# DM01eco.net
KiCad netlist of a schematic drawn in EAGLE
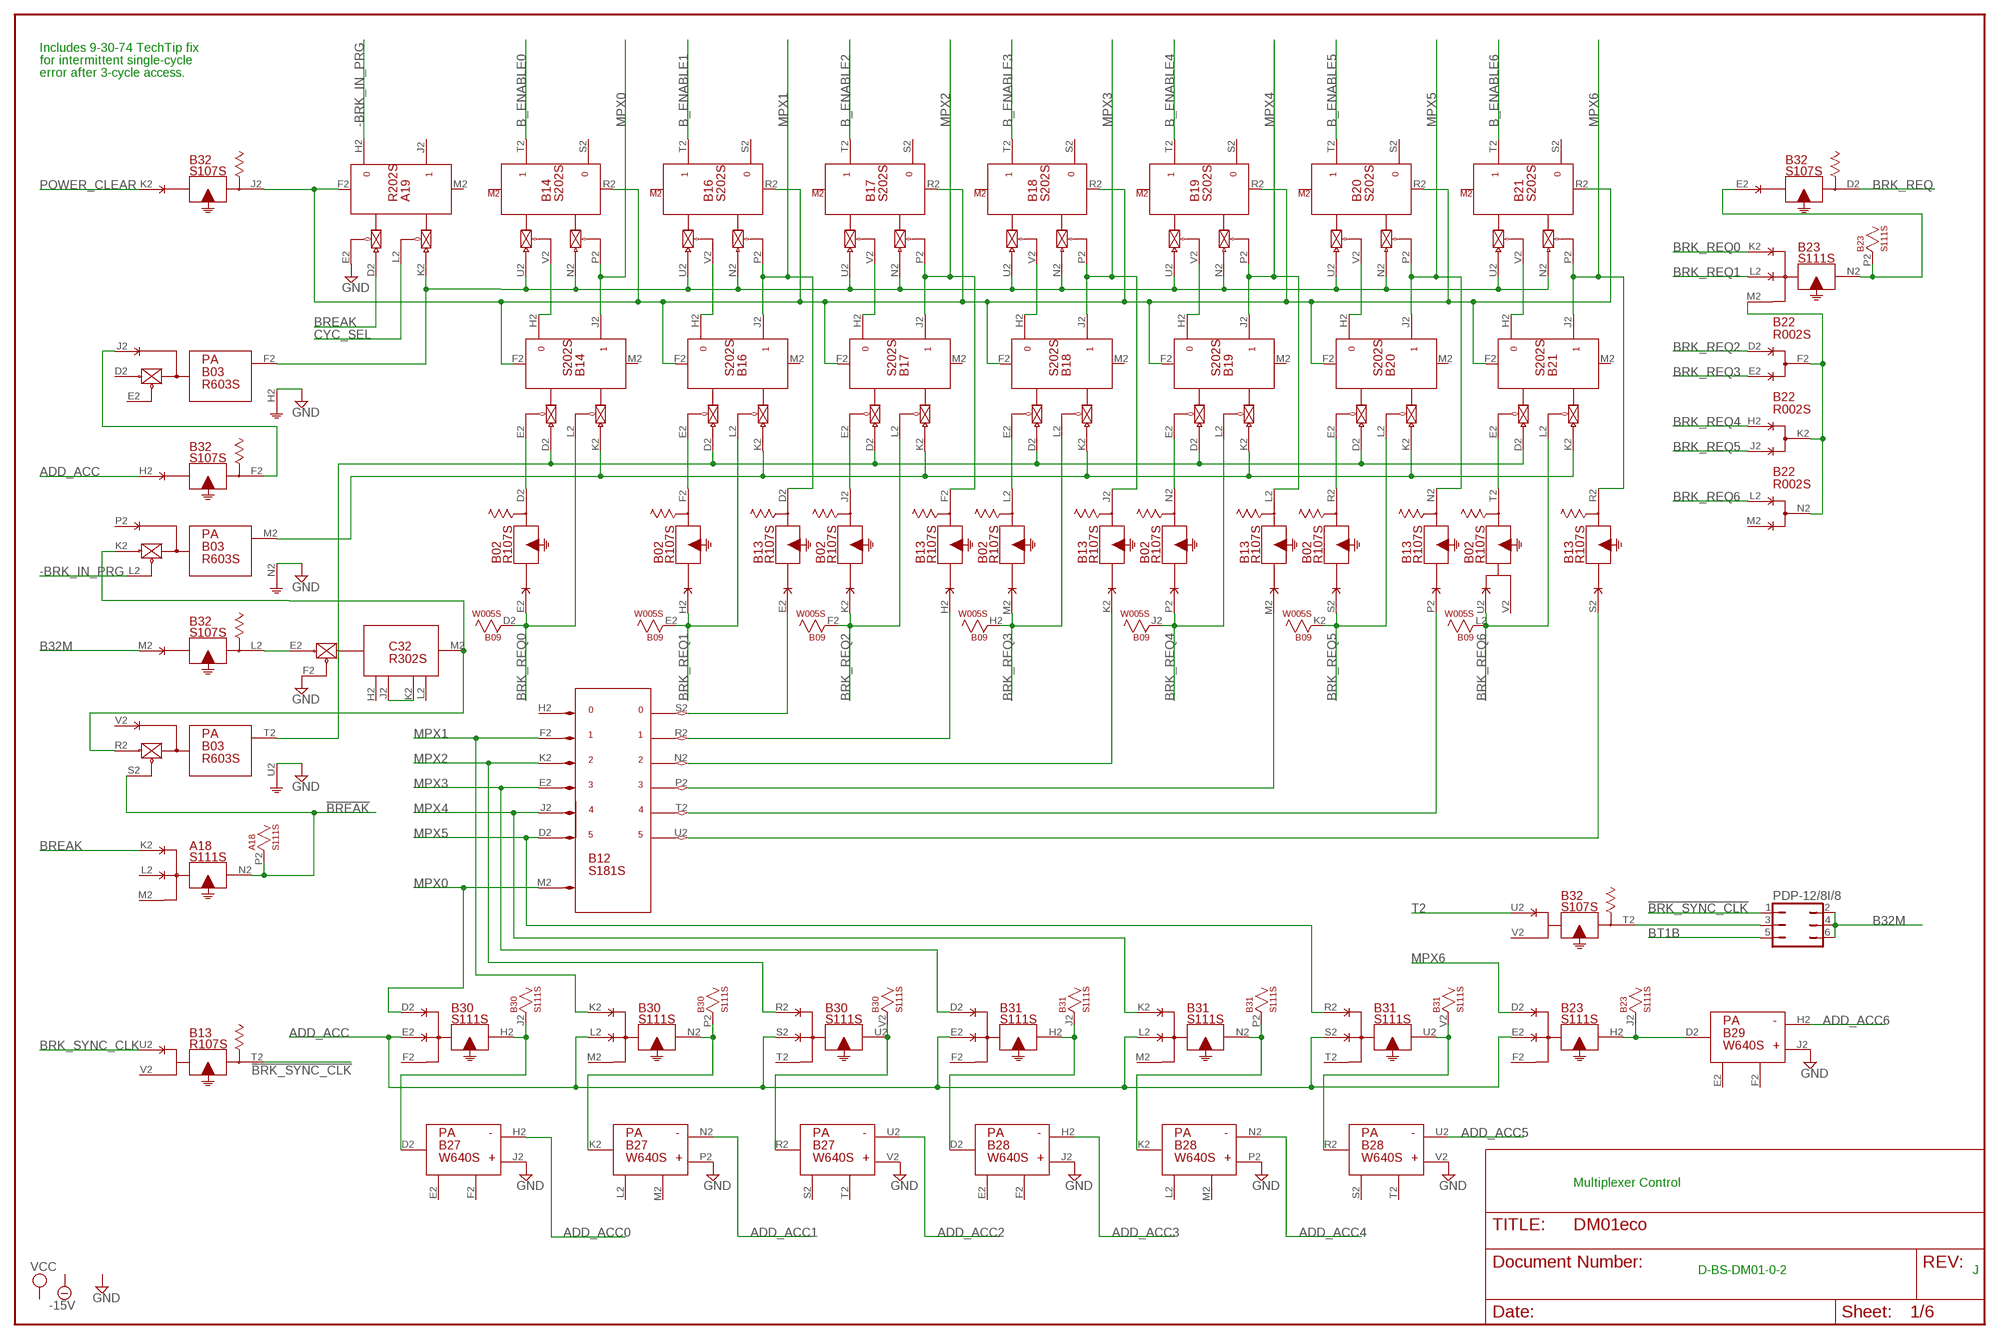
[diagram p0: schematic, sheet 1]
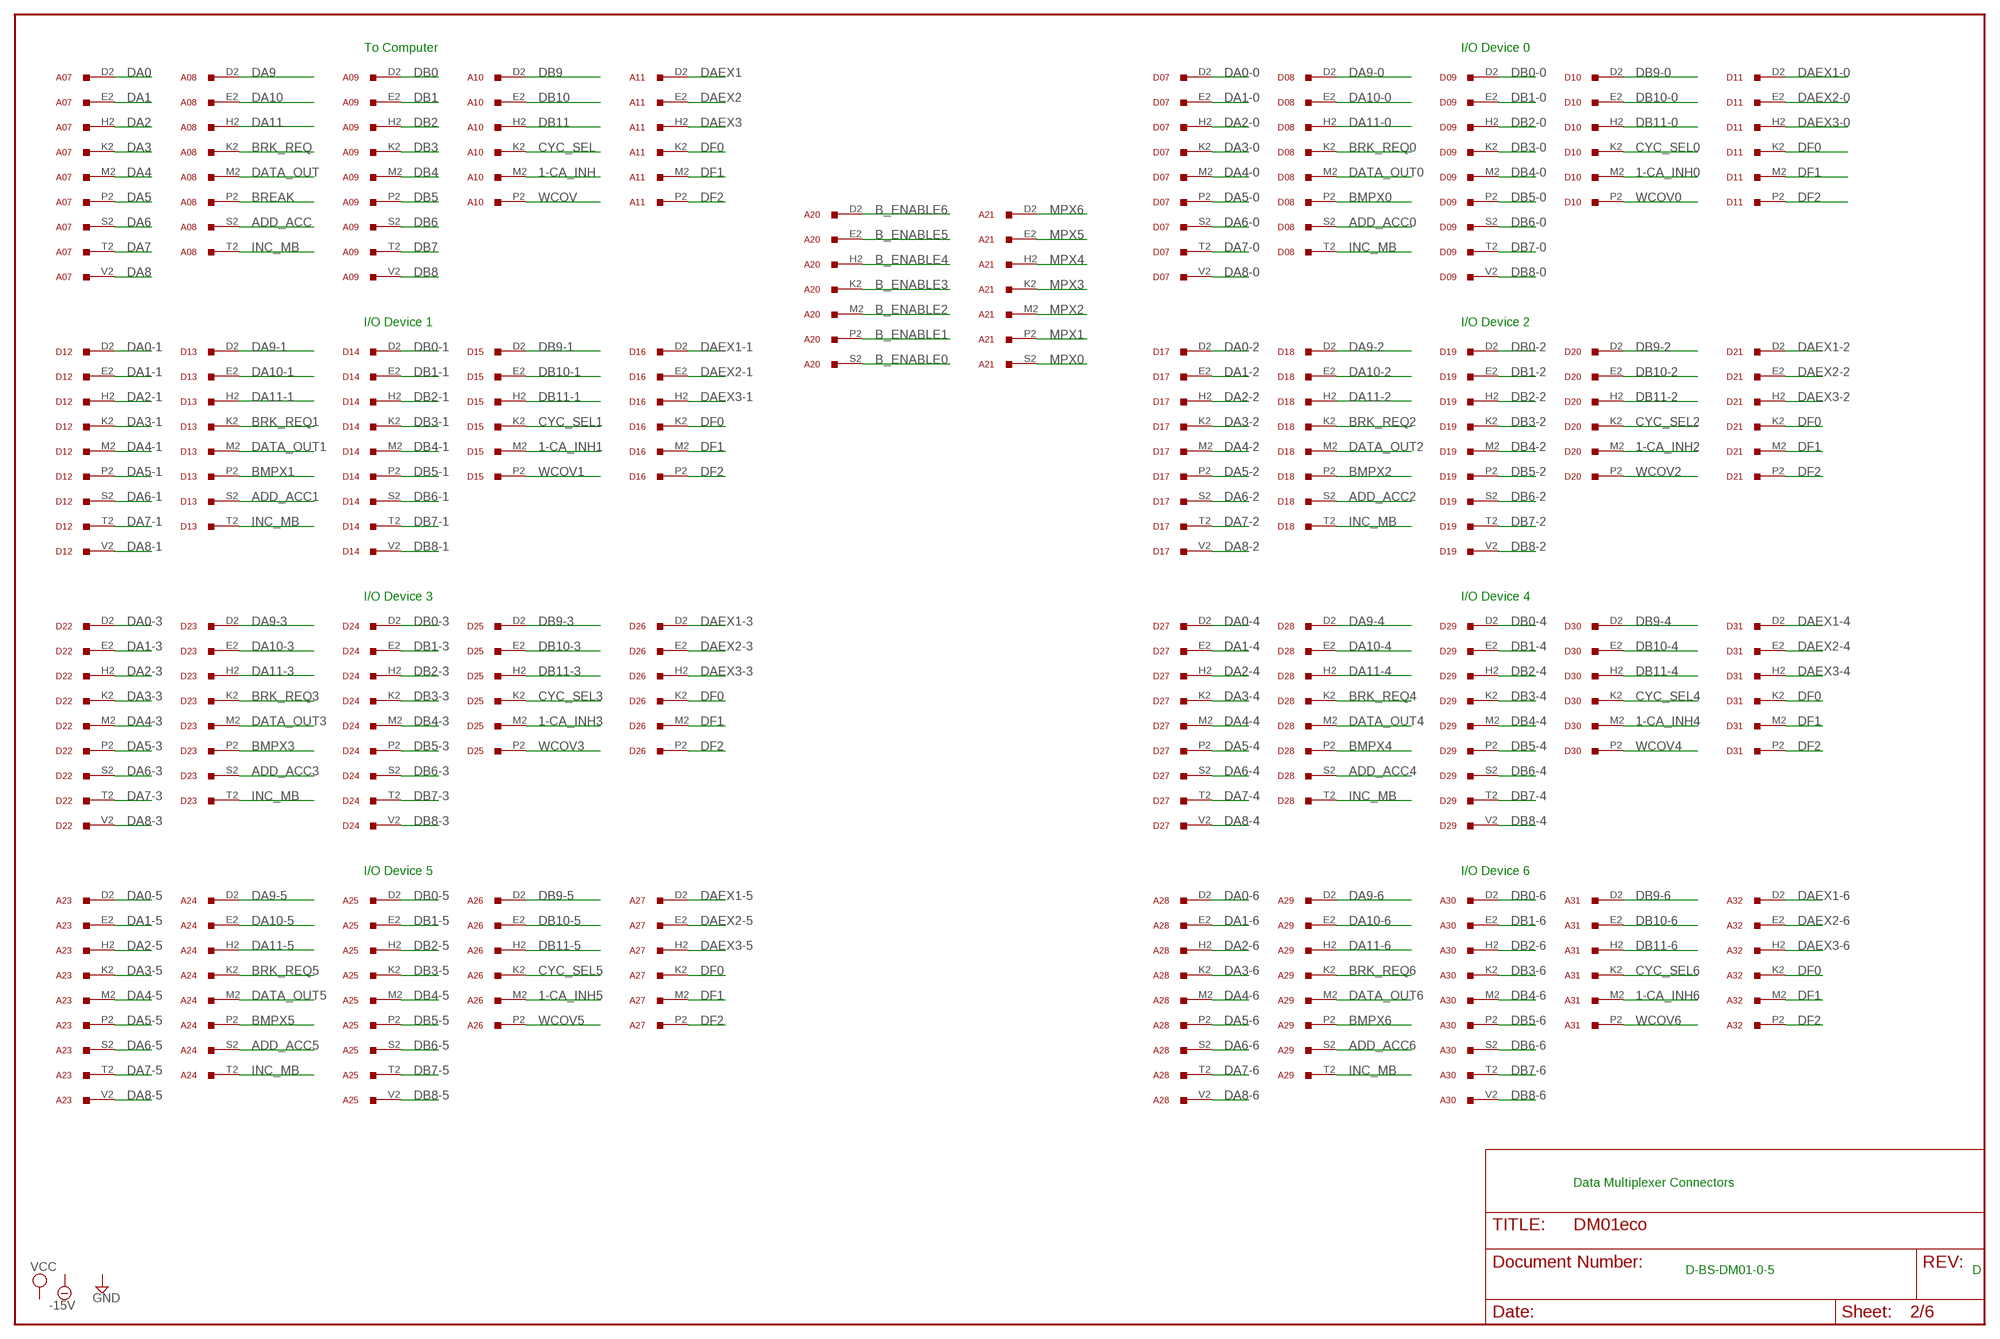
[diagram p1: schematic, sheet 2]
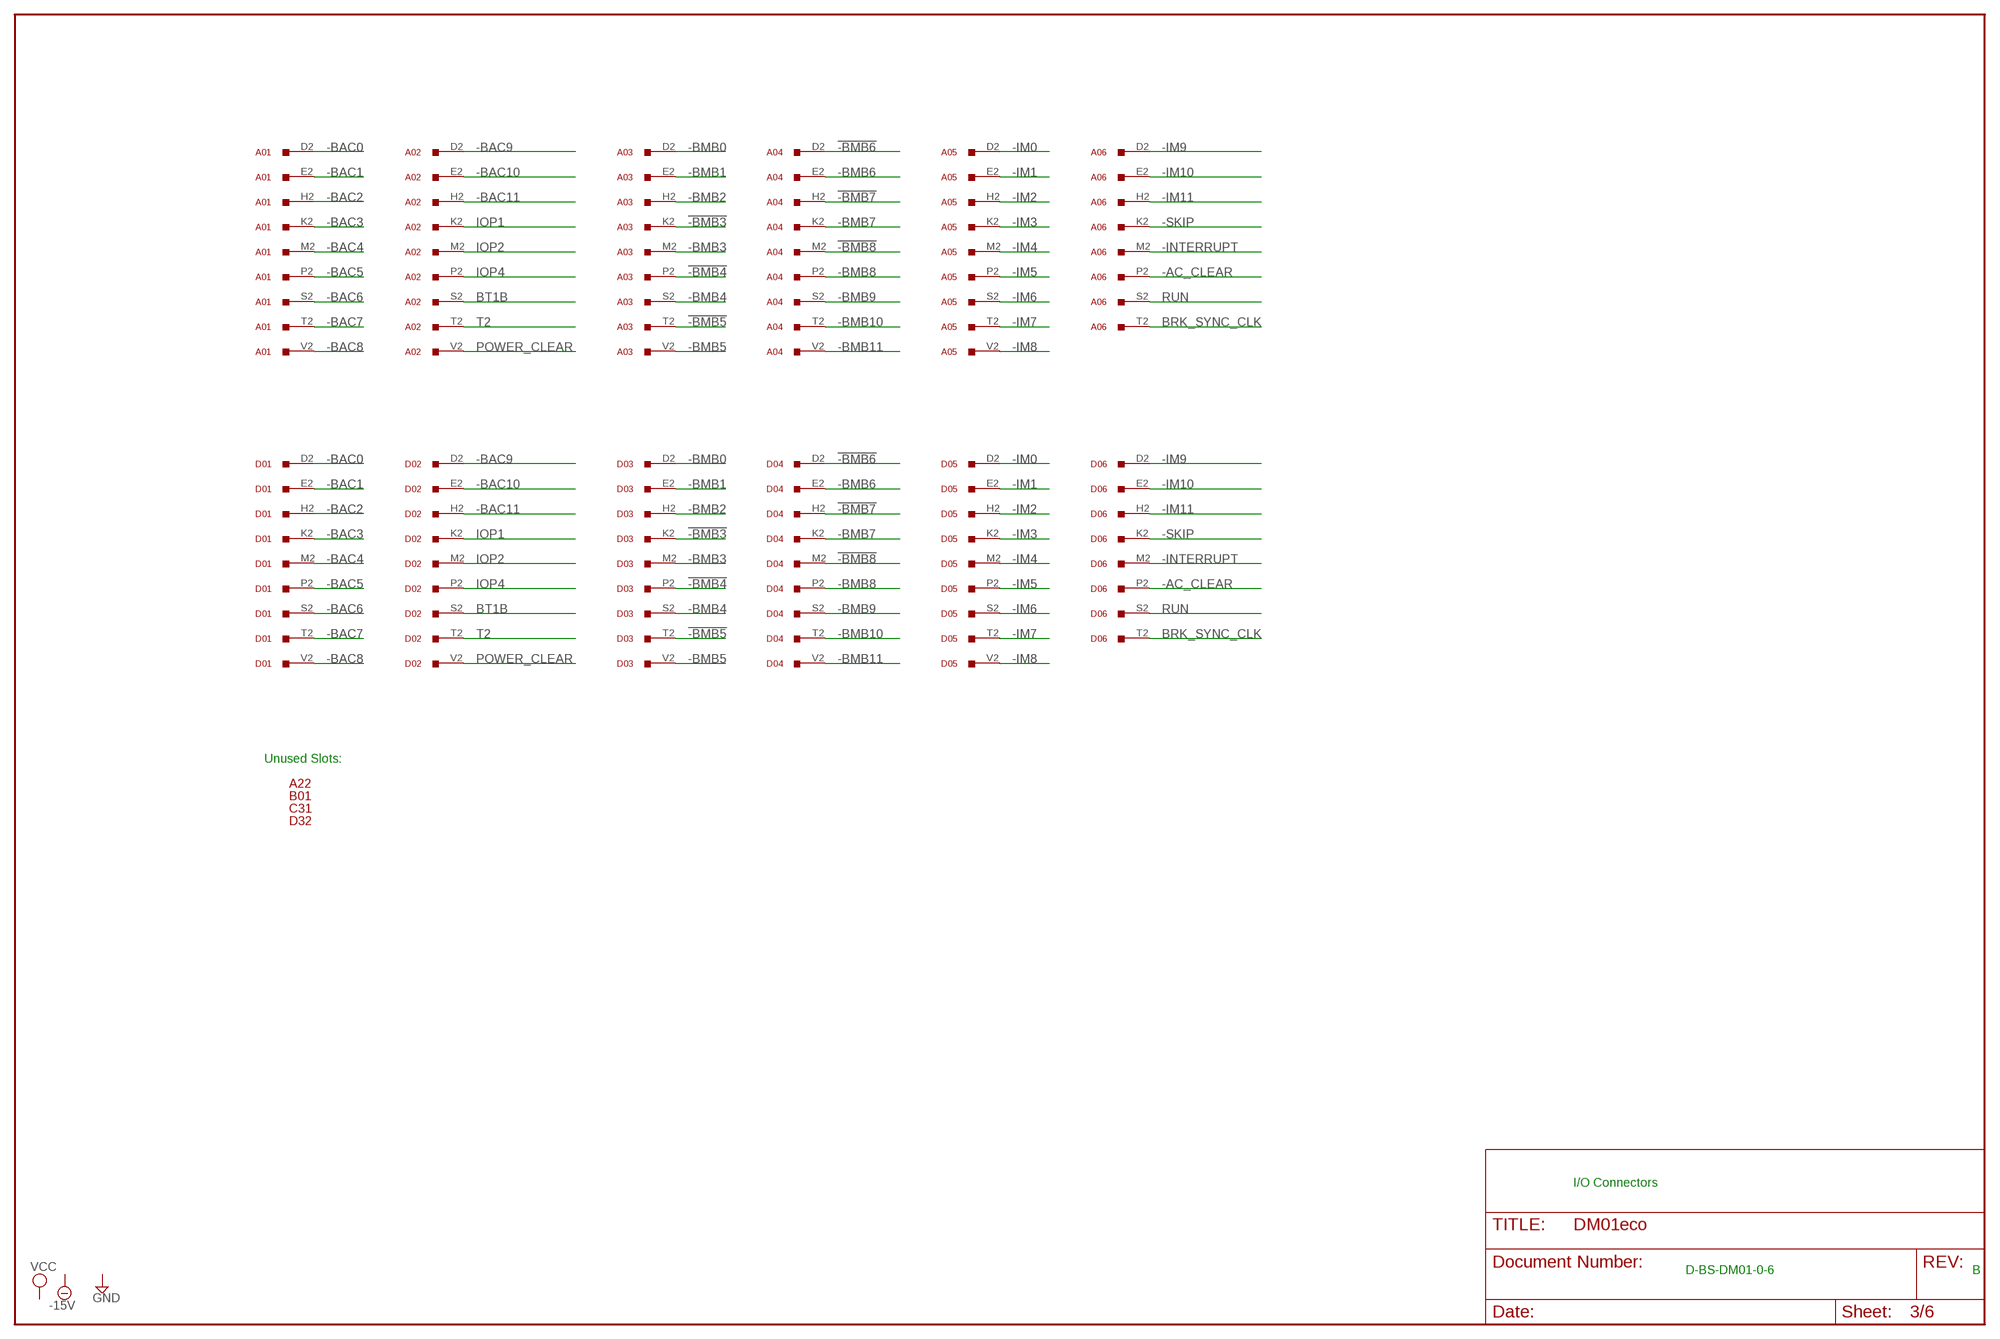
[diagram p2: schematic, sheet 3]
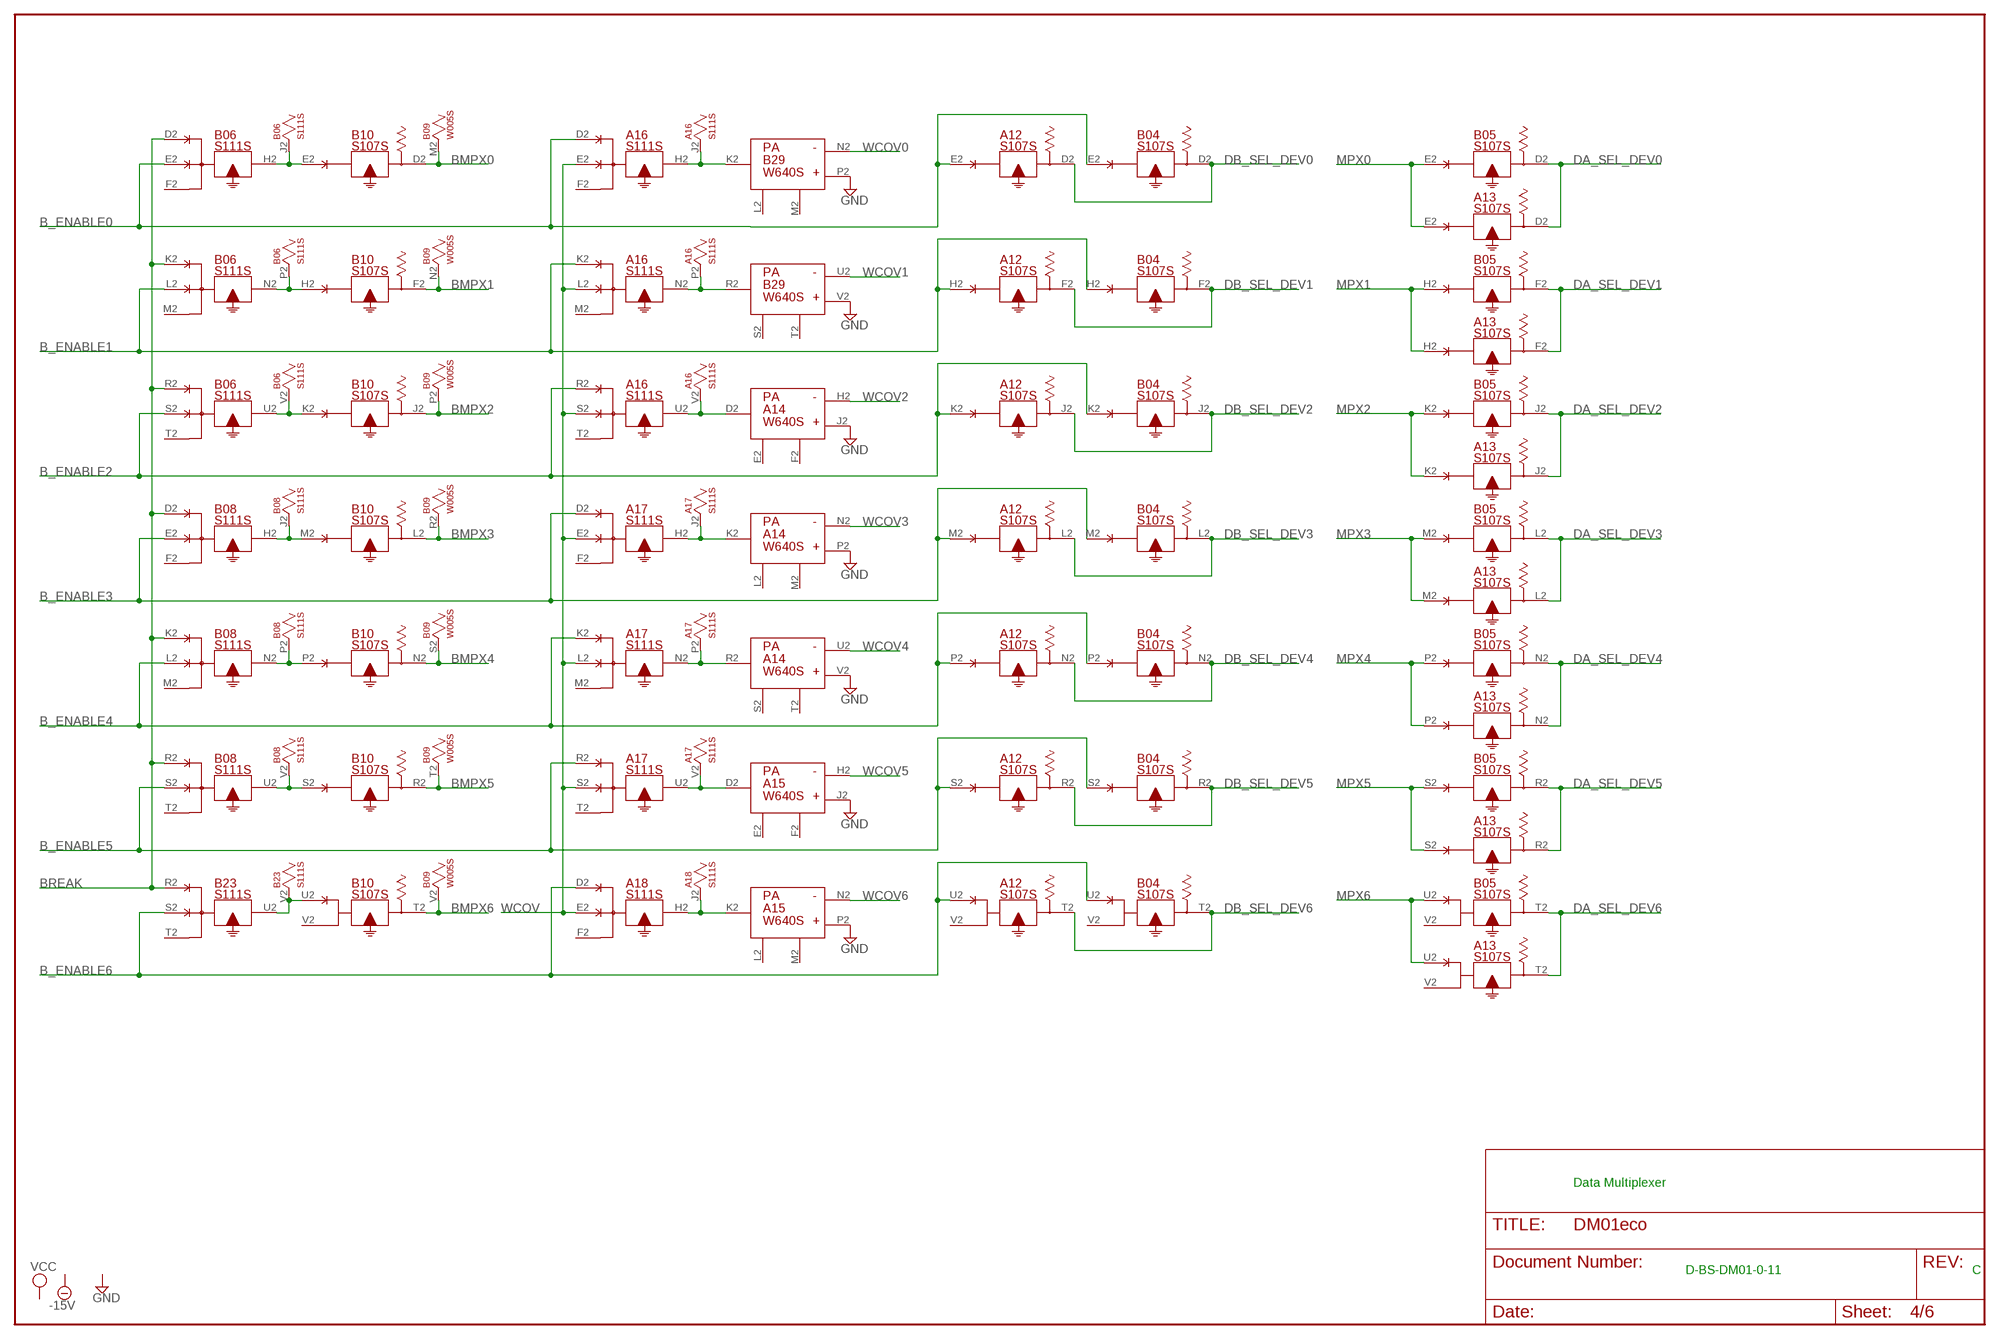
[diagram p3: schematic, sheet 4]
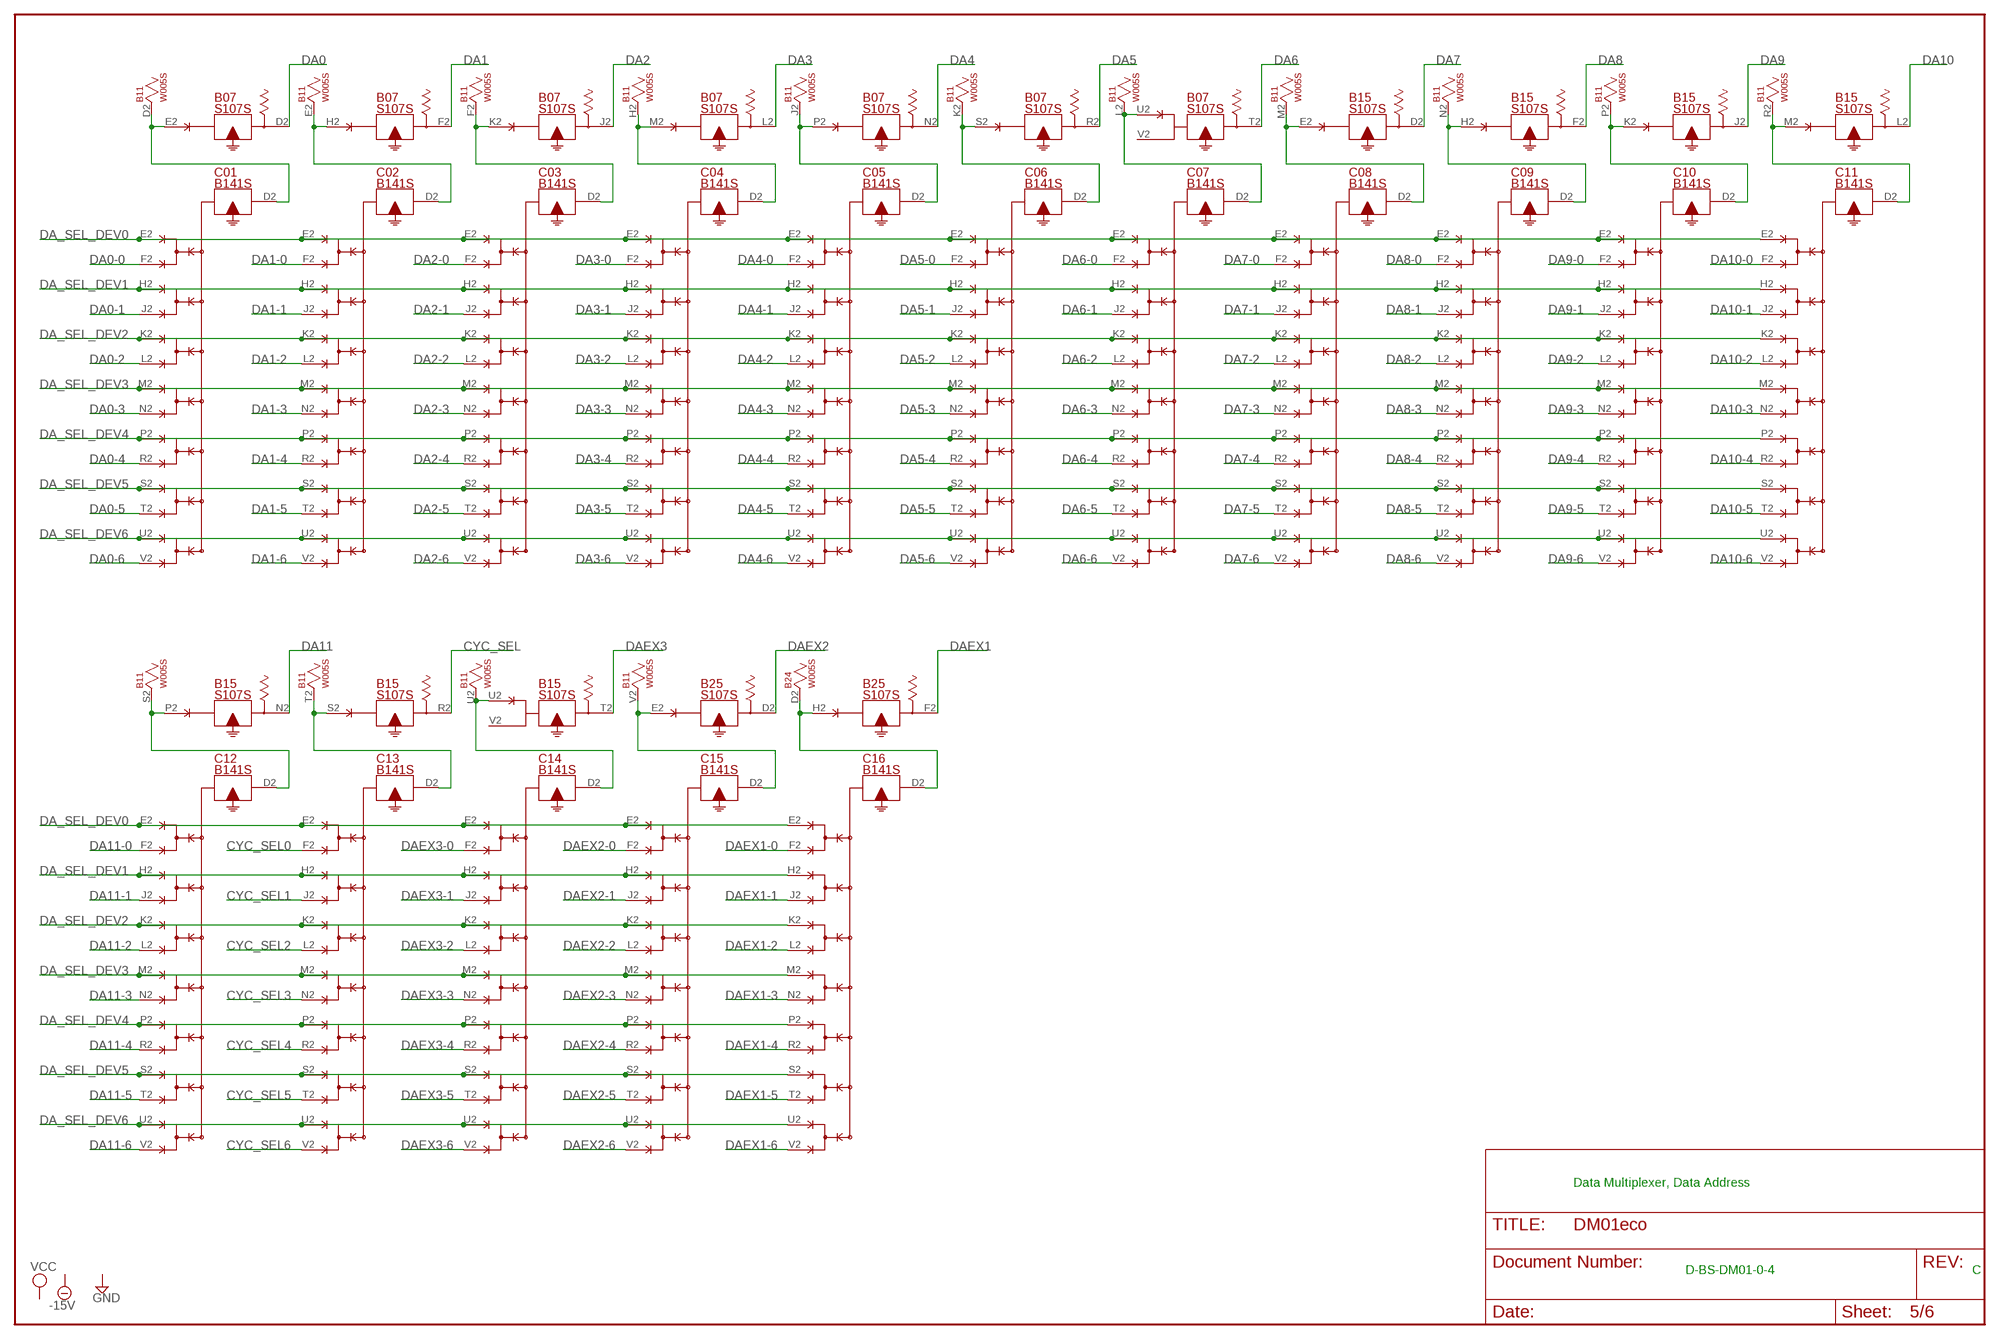
[diagram p4: schematic, sheet 5]
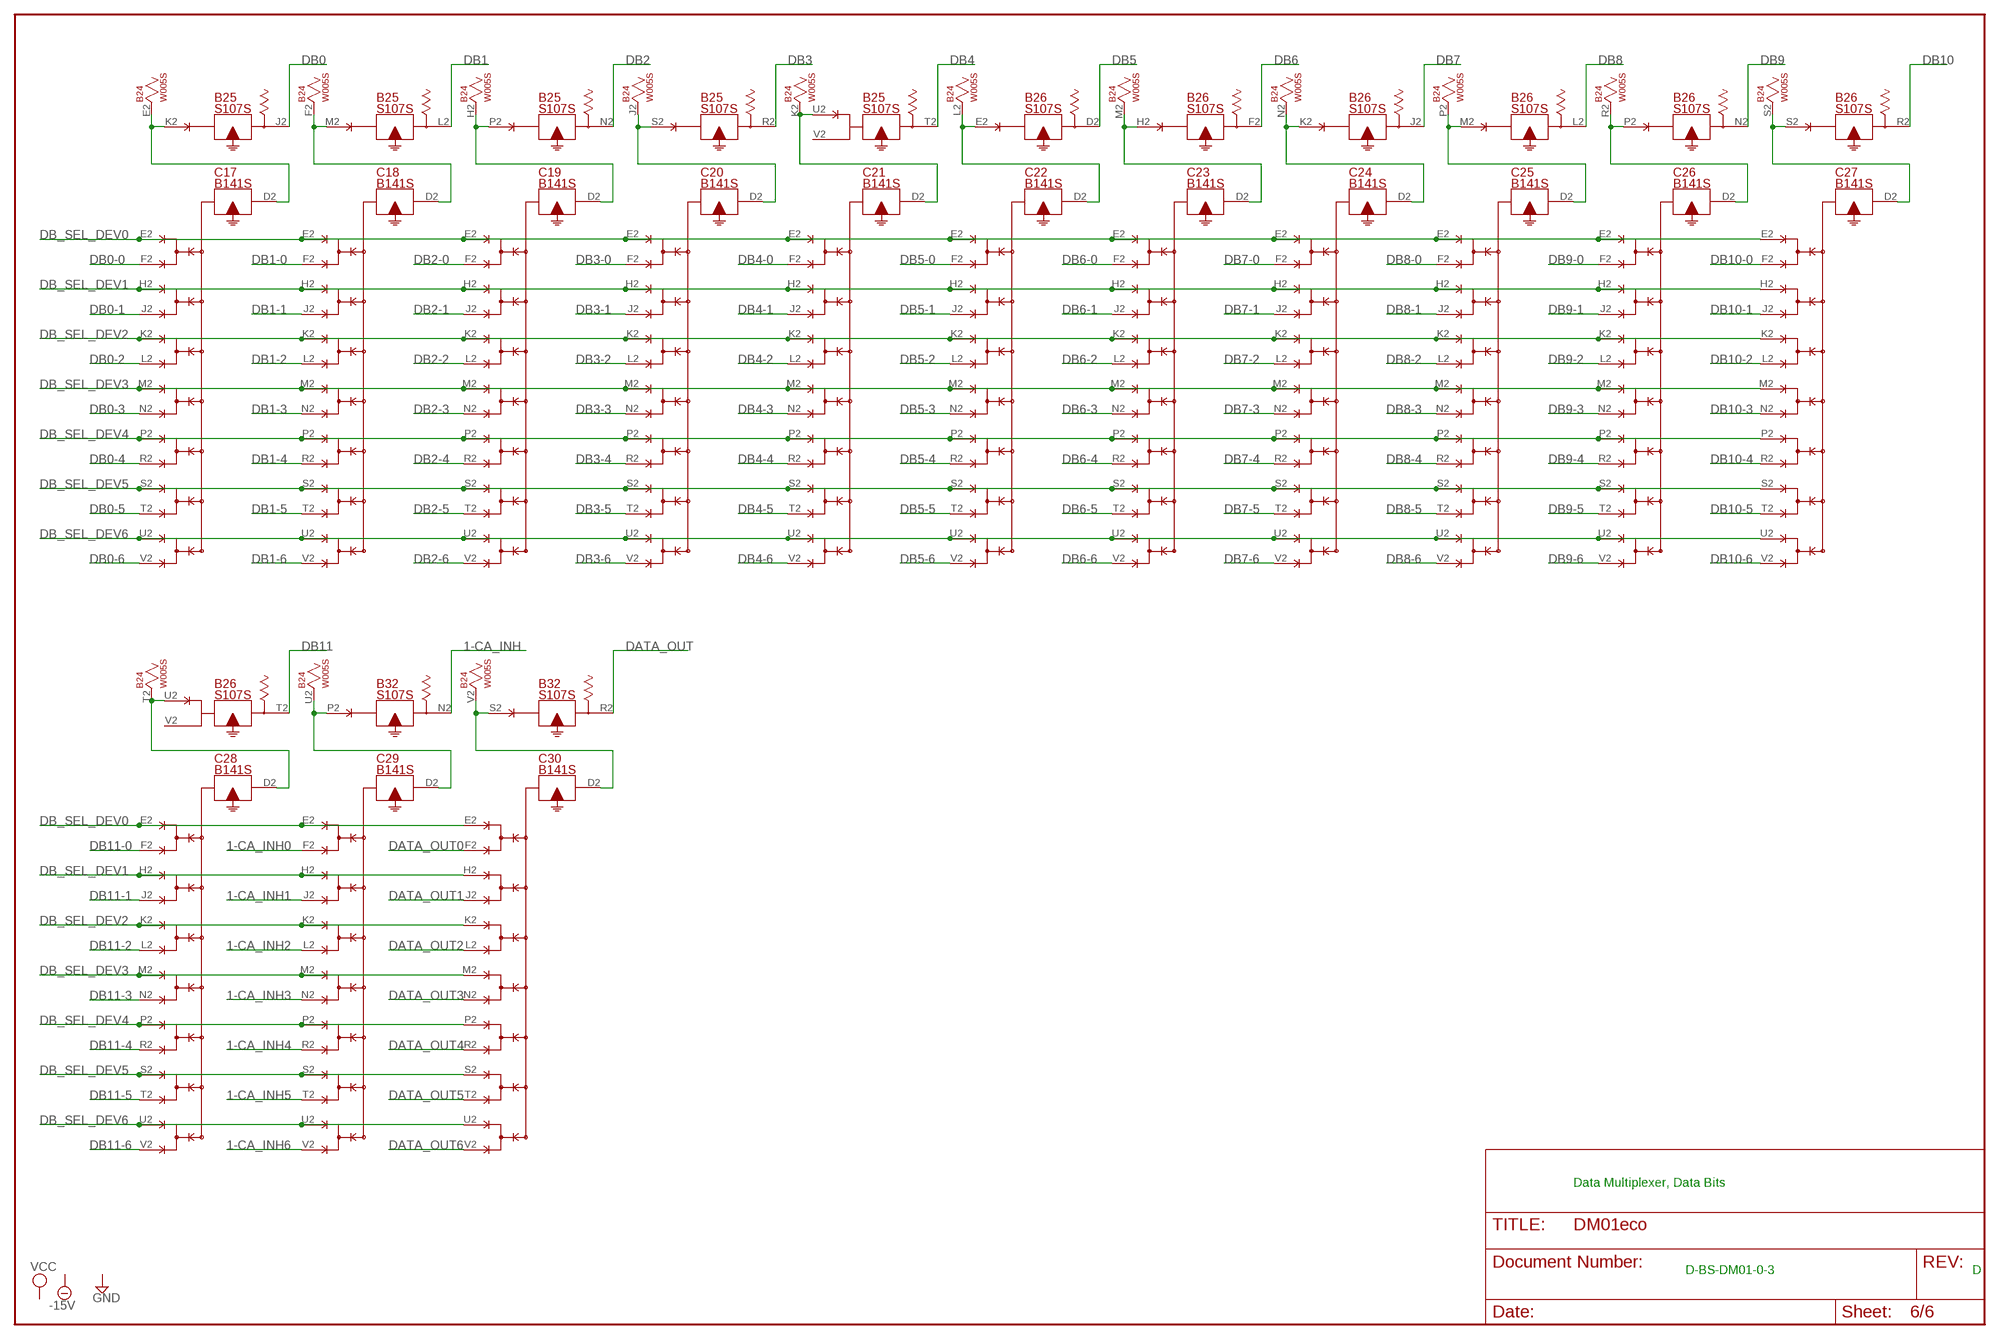
[diagram p5: schematic, sheet 6]

(export (version "E")
  (design (tool "Eeschema 10.0.6"))
  (components
    (comp (ref "A12")
      (value "S107S")
      (footprint "eagle-import:H807S")
      (libsource (lib "eagle-import") (part "R107S"))
    )
    (comp (ref "A13")
      (value "S107S")
      (footprint "eagle-import:H807S")
      (libsource (lib "eagle-import") (part "R107S"))
    )
    (comp (ref "A14")
      (value "W640S")
      (footprint "eagle-import:H807S")
      (libsource (lib "eagle-import") (part "W640S"))
    )
    (comp (ref "A15")
      (value "W640S")
      (footprint "eagle-import:H807S")
      (libsource (lib "eagle-import") (part "W640S"))
    )
    (comp (ref "A16")
      (value "S111S")
      (footprint "eagle-import:H807S")
      (libsource (lib "eagle-import") (part "R111S"))
    )
    (comp (ref "A17")
      (value "S111S")
      (footprint "eagle-import:H807S")
      (libsource (lib "eagle-import") (part "R111S"))
    )
    (comp (ref "A18")
      (value "S111S")
      (footprint "eagle-import:H807S")
      (libsource (lib "eagle-import") (part "R111S"))
    )
    (comp (ref "B04")
      (value "S107S")
      (footprint "eagle-import:H807S")
      (libsource (lib "eagle-import") (part "R107S"))
    )
    (comp (ref "B05")
      (value "S107S")
      (footprint "eagle-import:H807S")
      (libsource (lib "eagle-import") (part "R107S"))
    )
    (comp (ref "B06")
      (value "S111S")
      (footprint "eagle-import:H807S")
      (libsource (lib "eagle-import") (part "R111S"))
    )
    (comp (ref "B08")
      (value "S111S")
      (footprint "eagle-import:H807S")
      (libsource (lib "eagle-import") (part "R111S"))
    )
    (comp (ref "B09")
      (value "W005S")
      (footprint "eagle-import:H807S")
      (libsource (lib "eagle-import") (part "W005S"))
    )
    (comp (ref "B10")
      (value "S107S")
      (footprint "eagle-import:H807S")
      (libsource (lib "eagle-import") (part "R107S"))
    )
    (comp (ref "B23")
      (value "S111S")
      (footprint "eagle-import:H807S")
      (libsource (lib "eagle-import") (part "R111S"))
    )
    (comp (ref "B29")
      (value "W640S")
      (footprint "eagle-import:H807S")
      (libsource (lib "eagle-import") (part "W640S"))
    )
    (comp (ref "B24")
      (value "W005S")
      (footprint "eagle-import:H807S")
      (libsource (lib "eagle-import") (part "W005S"))
    )
    (comp (ref "B25")
      (value "S107S")
      (footprint "eagle-import:H807S")
      (libsource (lib "eagle-import") (part "R107S"))
    )
    (comp (ref "B26")
      (value "S107S")
      (footprint "eagle-import:H807S")
      (libsource (lib "eagle-import") (part "R107S"))
    )
    (comp (ref "B32")
      (value "S107S")
      (footprint "eagle-import:H807S")
      (libsource (lib "eagle-import") (part "R107S"))
    )
    (comp (ref "C17")
      (value "B141S")
      (footprint "eagle-import:H807S")
      (libsource (lib "eagle-import") (part "R141S"))
    )
    (comp (ref "C18")
      (value "B141S")
      (footprint "eagle-import:H807S")
      (libsource (lib "eagle-import") (part "R141S"))
    )
    (comp (ref "C19")
      (value "B141S")
      (footprint "eagle-import:H807S")
      (libsource (lib "eagle-import") (part "R141S"))
    )
    (comp (ref "C20")
      (value "B141S")
      (footprint "eagle-import:H807S")
      (libsource (lib "eagle-import") (part "R141S"))
    )
    (comp (ref "C21")
      (value "B141S")
      (footprint "eagle-import:H807S")
      (libsource (lib "eagle-import") (part "R141S"))
    )
    (comp (ref "C22")
      (value "B141S")
      (footprint "eagle-import:H807S")
      (libsource (lib "eagle-import") (part "R141S"))
    )
    (comp (ref "C23")
      (value "B141S")
      (footprint "eagle-import:H807S")
      (libsource (lib "eagle-import") (part "R141S"))
    )
    (comp (ref "C24")
      (value "B141S")
      (footprint "eagle-import:H807S")
      (libsource (lib "eagle-import") (part "R141S"))
    )
    (comp (ref "C25")
      (value "B141S")
      (footprint "eagle-import:H807S")
      (libsource (lib "eagle-import") (part "R141S"))
    )
    (comp (ref "C26")
      (value "B141S")
      (footprint "eagle-import:H807S")
      (libsource (lib "eagle-import") (part "R141S"))
    )
    (comp (ref "C27")
      (value "B141S")
      (footprint "eagle-import:H807S")
      (libsource (lib "eagle-import") (part "R141S"))
    )
    (comp (ref "C28")
      (value "B141S")
      (footprint "eagle-import:H807S")
      (libsource (lib "eagle-import") (part "R141S"))
    )
    (comp (ref "C29")
      (value "B141S")
      (footprint "eagle-import:H807S")
      (libsource (lib "eagle-import") (part "R141S"))
    )
    (comp (ref "C30")
      (value "B141S")
      (footprint "eagle-import:H807S")
      (libsource (lib "eagle-import") (part "R141S"))
    )
    (comp (ref "B07")
      (value "S107S")
      (footprint "eagle-import:H807S")
      (libsource (lib "eagle-import") (part "R107S"))
    )
    (comp (ref "B11")
      (value "W005S")
      (footprint "eagle-import:H807S")
      (libsource (lib "eagle-import") (part "W005S"))
    )
    (comp (ref "B15")
      (value "S107S")
      (footprint "eagle-import:H807S")
      (libsource (lib "eagle-import") (part "R107S"))
    )
    (comp (ref "C01")
      (value "B141S")
      (footprint "eagle-import:H807S")
      (libsource (lib "eagle-import") (part "R141S"))
    )
    (comp (ref "C02")
      (value "B141S")
      (footprint "eagle-import:H807S")
      (libsource (lib "eagle-import") (part "R141S"))
    )
    (comp (ref "C03")
      (value "B141S")
      (footprint "eagle-import:H807S")
      (libsource (lib "eagle-import") (part "R141S"))
    )
    (comp (ref "C04")
      (value "B141S")
      (footprint "eagle-import:H807S")
      (libsource (lib "eagle-import") (part "R141S"))
    )
    (comp (ref "C05")
      (value "B141S")
      (footprint "eagle-import:H807S")
      (libsource (lib "eagle-import") (part "R141S"))
    )
    (comp (ref "C06")
      (value "B141S")
      (footprint "eagle-import:H807S")
      (libsource (lib "eagle-import") (part "R141S"))
    )
    (comp (ref "C07")
      (value "B141S")
      (footprint "eagle-import:H807S")
      (libsource (lib "eagle-import") (part "R141S"))
    )
    (comp (ref "C08")
      (value "B141S")
      (footprint "eagle-import:H807S")
      (libsource (lib "eagle-import") (part "R141S"))
    )
    (comp (ref "C09")
      (value "B141S")
      (footprint "eagle-import:H807S")
      (libsource (lib "eagle-import") (part "R141S"))
    )
    (comp (ref "C10")
      (value "B141S")
      (footprint "eagle-import:H807S")
      (libsource (lib "eagle-import") (part "R141S"))
    )
    (comp (ref "C11")
      (value "B141S")
      (footprint "eagle-import:H807S")
      (libsource (lib "eagle-import") (part "R141S"))
    )
    (comp (ref "C12")
      (value "B141S")
      (footprint "eagle-import:H807S")
      (libsource (lib "eagle-import") (part "R141S"))
    )
    (comp (ref "C13")
      (value "B141S")
      (footprint "eagle-import:H807S")
      (libsource (lib "eagle-import") (part "R141S"))
    )
    (comp (ref "C14")
      (value "B141S")
      (footprint "eagle-import:H807S")
      (libsource (lib "eagle-import") (part "R141S"))
    )
    (comp (ref "C15")
      (value "B141S")
      (footprint "eagle-import:H807S")
      (libsource (lib "eagle-import") (part "R141S"))
    )
    (comp (ref "C16")
      (value "B141S")
      (footprint "eagle-import:H807S")
      (libsource (lib "eagle-import") (part "R141S"))
    )
    (comp (ref "A07")
      (value "W021S")
      (footprint "eagle-import:H807S")
      (libsource (lib "eagle-import") (part "W021S"))
    )
    (comp (ref "A08")
      (value "W021S")
      (footprint "eagle-import:H807S")
      (libsource (lib "eagle-import") (part "W021S"))
    )
    (comp (ref "A09")
      (value "W021S")
      (footprint "eagle-import:H807S")
      (libsource (lib "eagle-import") (part "W021S"))
    )
    (comp (ref "A10")
      (value "W021S")
      (footprint "eagle-import:H807S")
      (libsource (lib "eagle-import") (part "W021S"))
    )
    (comp (ref "A11")
      (value "W021S")
      (footprint "eagle-import:H807S")
      (libsource (lib "eagle-import") (part "W021S"))
    )
    (comp (ref "A20")
      (value "W021S")
      (footprint "eagle-import:H807S")
      (libsource (lib "eagle-import") (part "W021S"))
    )
    (comp (ref "A21")
      (value "W021S")
      (footprint "eagle-import:H807S")
      (libsource (lib "eagle-import") (part "W021S"))
    )
    (comp (ref "A23")
      (value "W021S")
      (footprint "eagle-import:H807S")
      (libsource (lib "eagle-import") (part "W021S"))
    )
    (comp (ref "A24")
      (value "W021S")
      (footprint "eagle-import:H807S")
      (libsource (lib "eagle-import") (part "W021S"))
    )
    (comp (ref "A25")
      (value "W021S")
      (footprint "eagle-import:H807S")
      (libsource (lib "eagle-import") (part "W021S"))
    )
    (comp (ref "A26")
      (value "W021S")
      (footprint "eagle-import:H807S")
      (libsource (lib "eagle-import") (part "W021S"))
    )
    (comp (ref "A27")
      (value "W021S")
      (footprint "eagle-import:H807S")
      (libsource (lib "eagle-import") (part "W021S"))
    )
    (comp (ref "A28")
      (value "W021S")
      (footprint "eagle-import:H807S")
      (libsource (lib "eagle-import") (part "W021S"))
    )
    (comp (ref "A29")
      (value "W021S")
      (footprint "eagle-import:H807S")
      (libsource (lib "eagle-import") (part "W021S"))
    )
    (comp (ref "A30")
      (value "W021S")
      (footprint "eagle-import:H807S")
      (libsource (lib "eagle-import") (part "W021S"))
    )
    (comp (ref "A31")
      (value "W021S")
      (footprint "eagle-import:H807S")
      (libsource (lib "eagle-import") (part "W021S"))
    )
    (comp (ref "A32")
      (value "W021S")
      (footprint "eagle-import:H807S")
      (libsource (lib "eagle-import") (part "W021S"))
    )
    (comp (ref "D07")
      (value "W021S")
      (footprint "eagle-import:H807S")
      (libsource (lib "eagle-import") (part "W021S"))
    )
    (comp (ref "D08")
      (value "W021S")
      (footprint "eagle-import:H807S")
      (libsource (lib "eagle-import") (part "W021S"))
    )
    (comp (ref "D09")
      (value "W021S")
      (footprint "eagle-import:H807S")
      (libsource (lib "eagle-import") (part "W021S"))
    )
    (comp (ref "D10")
      (value "W021S")
      (footprint "eagle-import:H807S")
      (libsource (lib "eagle-import") (part "W021S"))
    )
    (comp (ref "D11")
      (value "W021S")
      (footprint "eagle-import:H807S")
      (libsource (lib "eagle-import") (part "W021S"))
    )
    (comp (ref "D12")
      (value "W021S")
      (footprint "eagle-import:H807S")
      (libsource (lib "eagle-import") (part "W021S"))
    )
    (comp (ref "D13")
      (value "W021S")
      (footprint "eagle-import:H807S")
      (libsource (lib "eagle-import") (part "W021S"))
    )
    (comp (ref "D14")
      (value "W021S")
      (footprint "eagle-import:H807S")
      (libsource (lib "eagle-import") (part "W021S"))
    )
    (comp (ref "D15")
      (value "W021S")
      (footprint "eagle-import:H807S")
      (libsource (lib "eagle-import") (part "W021S"))
    )
    (comp (ref "D16")
      (value "W021S")
      (footprint "eagle-import:H807S")
      (libsource (lib "eagle-import") (part "W021S"))
    )
    (comp (ref "D17")
      (value "W021S")
      (footprint "eagle-import:H807S")
      (libsource (lib "eagle-import") (part "W021S"))
    )
    (comp (ref "D18")
      (value "W021S")
      (footprint "eagle-import:H807S")
      (libsource (lib "eagle-import") (part "W021S"))
    )
    (comp (ref "D19")
      (value "W021S")
      (footprint "eagle-import:H807S")
      (libsource (lib "eagle-import") (part "W021S"))
    )
    (comp (ref "D20")
      (value "W021S")
      (footprint "eagle-import:H807S")
      (libsource (lib "eagle-import") (part "W021S"))
    )
    (comp (ref "D21")
      (value "W021S")
      (footprint "eagle-import:H807S")
      (libsource (lib "eagle-import") (part "W021S"))
    )
    (comp (ref "D22")
      (value "W021S")
      (footprint "eagle-import:H807S")
      (libsource (lib "eagle-import") (part "W021S"))
    )
    (comp (ref "D23")
      (value "W021S")
      (footprint "eagle-import:H807S")
      (libsource (lib "eagle-import") (part "W021S"))
    )
    (comp (ref "D24")
      (value "W021S")
      (footprint "eagle-import:H807S")
      (libsource (lib "eagle-import") (part "W021S"))
    )
    (comp (ref "D25")
      (value "W021S")
      (footprint "eagle-import:H807S")
      (libsource (lib "eagle-import") (part "W021S"))
    )
    (comp (ref "D26")
      (value "W021S")
      (footprint "eagle-import:H807S")
      (libsource (lib "eagle-import") (part "W021S"))
    )
    (comp (ref "D27")
      (value "W021S")
      (footprint "eagle-import:H807S")
      (libsource (lib "eagle-import") (part "W021S"))
    )
    (comp (ref "D28")
      (value "W021S")
      (footprint "eagle-import:H807S")
      (libsource (lib "eagle-import") (part "W021S"))
    )
    (comp (ref "D29")
      (value "W021S")
      (footprint "eagle-import:H807S")
      (libsource (lib "eagle-import") (part "W021S"))
    )
    (comp (ref "D30")
      (value "W021S")
      (footprint "eagle-import:H807S")
      (libsource (lib "eagle-import") (part "W021S"))
    )
    (comp (ref "D31")
      (value "W021S")
      (footprint "eagle-import:H807S")
      (libsource (lib "eagle-import") (part "W021S"))
    )
    (comp (ref "A01")
      (value "W021S")
      (footprint "eagle-import:H807S")
      (libsource (lib "eagle-import") (part "W021S"))
    )
    (comp (ref "A02")
      (value "W021S")
      (footprint "eagle-import:H807S")
      (libsource (lib "eagle-import") (part "W021S"))
    )
    (comp (ref "A03")
      (value "W021S")
      (footprint "eagle-import:H807S")
      (libsource (lib "eagle-import") (part "W021S"))
    )
    (comp (ref "A04")
      (value "W021S")
      (footprint "eagle-import:H807S")
      (libsource (lib "eagle-import") (part "W021S"))
    )
    (comp (ref "A05")
      (value "W021S")
      (footprint "eagle-import:H807S")
      (libsource (lib "eagle-import") (part "W021S"))
    )
    (comp (ref "A06")
      (value "W021S")
      (footprint "eagle-import:H807S")
      (libsource (lib "eagle-import") (part "W021S"))
    )
    (comp (ref "A22")
      (value "EMPTYS")
      (footprint "eagle-import:H807S")
      (libsource (lib "eagle-import") (part "EMPTYS"))
    )
    (comp (ref "B01")
      (value "EMPTYS")
      (footprint "eagle-import:H807S")
      (libsource (lib "eagle-import") (part "EMPTYS"))
    )
    (comp (ref "C31")
      (value "EMPTYS")
      (footprint "eagle-import:H807S")
      (libsource (lib "eagle-import") (part "EMPTYS"))
    )
    (comp (ref "D01")
      (value "W021S")
      (footprint "eagle-import:H807S")
      (libsource (lib "eagle-import") (part "W021S"))
    )
    (comp (ref "D02")
      (value "W021S")
      (footprint "eagle-import:H807S")
      (libsource (lib "eagle-import") (part "W021S"))
    )
    (comp (ref "D03")
      (value "W021S")
      (footprint "eagle-import:H807S")
      (libsource (lib "eagle-import") (part "W021S"))
    )
    (comp (ref "D04")
      (value "W021S")
      (footprint "eagle-import:H807S")
      (libsource (lib "eagle-import") (part "W021S"))
    )
    (comp (ref "D05")
      (value "W021S")
      (footprint "eagle-import:H807S")
      (libsource (lib "eagle-import") (part "W021S"))
    )
    (comp (ref "D06")
      (value "W021S")
      (footprint "eagle-import:H807S")
      (libsource (lib "eagle-import") (part "W021S"))
    )
    (comp (ref "D32")
      (value "EMPTYS")
      (footprint "eagle-import:H807S")
      (libsource (lib "eagle-import") (part "EMPTYS"))
    )
    (comp (ref "A19")
      (value "R202S")
      (footprint "eagle-import:H807S")
      (libsource (lib "eagle-import") (part "R202S"))
    )
    (comp (ref "B02")
      (value "R107S")
      (footprint "eagle-import:H807S")
      (libsource (lib "eagle-import") (part "R107S"))
    )
    (comp (ref "B03")
      (value "R603S")
      (footprint "eagle-import:H807S")
      (libsource (lib "eagle-import") (part "R603S"))
    )
    (comp (ref "B12")
      (value "S181S")
      (footprint "eagle-import:H807S")
      (libsource (lib "eagle-import") (part "R181S"))
    )
    (comp (ref "B13")
      (value "R107S")
      (footprint "eagle-import:H807S")
      (libsource (lib "eagle-import") (part "R107S"))
    )
    (comp (ref "B14")
      (value "S202S")
      (footprint "eagle-import:H807S")
      (libsource (lib "eagle-import") (part "R202S"))
    )
    (comp (ref "B16")
      (value "S202S")
      (footprint "eagle-import:H807S")
      (libsource (lib "eagle-import") (part "R202S"))
    )
    (comp (ref "B17")
      (value "S202S")
      (footprint "eagle-import:H807S")
      (libsource (lib "eagle-import") (part "R202S"))
    )
    (comp (ref "B18")
      (value "S202S")
      (footprint "eagle-import:H807S")
      (libsource (lib "eagle-import") (part "R202S"))
    )
    (comp (ref "B19")
      (value "S202S")
      (footprint "eagle-import:H807S")
      (libsource (lib "eagle-import") (part "R202S"))
    )
    (comp (ref "B20")
      (value "S202S")
      (footprint "eagle-import:H807S")
      (libsource (lib "eagle-import") (part "R202S"))
    )
    (comp (ref "B21")
      (value "S202S")
      (footprint "eagle-import:H807S")
      (libsource (lib "eagle-import") (part "R202S"))
    )
    (comp (ref "B22")
      (value "R002S")
      (footprint "eagle-import:H807S")
      (libsource (lib "eagle-import") (part "R002S"))
    )
    (comp (ref "B27")
      (value "W640S")
      (footprint "eagle-import:H807S")
      (libsource (lib "eagle-import") (part "W640S"))
    )
    (comp (ref "B28")
      (value "W640S")
      (footprint "eagle-import:H807S")
      (libsource (lib "eagle-import") (part "W640S"))
    )
    (comp (ref "B30")
      (value "S111S")
      (footprint "eagle-import:H807S")
      (libsource (lib "eagle-import") (part "R111S"))
    )
    (comp (ref "B31")
      (value "S111S")
      (footprint "eagle-import:H807S")
      (libsource (lib "eagle-import") (part "R111S"))
    )
    (comp (ref "C32")
      (value "R302S")
      (footprint "eagle-import:H807S")
      (libsource (lib "eagle-import") (part "R302S"))
    )
    (comp (ref "PDP-12/8I/8")
      (value "JP3Q")
      (footprint "eagle-import:JP3Q")
      (libsource (lib "eagle-import") (part "JP3Q"))
    )
  )
  (nets
    (net (code "2") (name "-AC_CLEAR") (class "Default")
      (node (ref "A06") (pin "P2") (pinfunction "P$2_P2") (pintype "bidirectional"))
      (node (ref "D06") (pin "P2") (pinfunction "P$2_P2") (pintype "bidirectional"))
    )
    (net (code "3") (name "-BAC0") (class "Default")
      (node (ref "A01") (pin "D2") (pinfunction "P$2_D2") (pintype "bidirectional"))
      (node (ref "D01") (pin "D2") (pinfunction "P$2_D2") (pintype "bidirectional"))
    )
    (net (code "4") (name "-BAC1") (class "Default")
      (node (ref "A01") (pin "E2") (pinfunction "P$2_E2") (pintype "bidirectional"))
      (node (ref "D01") (pin "E2") (pinfunction "P$2_E2") (pintype "bidirectional"))
    )
    (net (code "5") (name "-BAC2") (class "Default")
      (node (ref "A01") (pin "H2") (pinfunction "P$2_H2") (pintype "bidirectional"))
      (node (ref "D01") (pin "H2") (pinfunction "P$2_H2") (pintype "bidirectional"))
    )
    (net (code "6") (name "-BAC3") (class "Default")
      (node (ref "A01") (pin "K2") (pinfunction "P$2_K2") (pintype "bidirectional"))
      (node (ref "D01") (pin "K2") (pinfunction "P$2_K2") (pintype "bidirectional"))
    )
    (net (code "7") (name "-BAC4") (class "Default")
      (node (ref "A01") (pin "M2") (pinfunction "P$2_M2") (pintype "bidirectional"))
      (node (ref "D01") (pin "M2") (pinfunction "P$2_M2") (pintype "bidirectional"))
    )
    (net (code "8") (name "-BAC5") (class "Default")
      (node (ref "A01") (pin "P2") (pinfunction "P$2_P2") (pintype "bidirectional"))
      (node (ref "D01") (pin "P2") (pinfunction "P$2_P2") (pintype "bidirectional"))
    )
    (net (code "9") (name "-BAC6") (class "Default")
      (node (ref "A01") (pin "S2") (pinfunction "P$2_S2") (pintype "bidirectional"))
      (node (ref "D01") (pin "S2") (pinfunction "P$2_S2") (pintype "bidirectional"))
    )
    (net (code "10") (name "-BAC7") (class "Default")
      (node (ref "A01") (pin "T2") (pinfunction "P$2_T2") (pintype "bidirectional"))
      (node (ref "D01") (pin "T2") (pinfunction "P$2_T2") (pintype "bidirectional"))
    )
    (net (code "11") (name "-BAC8") (class "Default")
      (node (ref "A01") (pin "V2") (pinfunction "P$2_V2") (pintype "bidirectional"))
      (node (ref "D01") (pin "V2") (pinfunction "P$2_V2") (pintype "bidirectional"))
    )
    (net (code "12") (name "-BAC9") (class "Default")
      (node (ref "A02") (pin "D2") (pinfunction "P$2_D2") (pintype "bidirectional"))
      (node (ref "D02") (pin "D2") (pinfunction "P$2_D2") (pintype "bidirectional"))
    )
    (net (code "13") (name "-BAC10") (class "Default")
      (node (ref "A02") (pin "E2") (pinfunction "P$2_E2") (pintype "bidirectional"))
      (node (ref "D02") (pin "E2") (pinfunction "P$2_E2") (pintype "bidirectional"))
    )
    (net (code "14") (name "-BAC11") (class "Default")
      (node (ref "A02") (pin "H2") (pinfunction "P$2_H2") (pintype "bidirectional"))
      (node (ref "D02") (pin "H2") (pinfunction "P$2_H2") (pintype "bidirectional"))
    )
    (net (code "15") (name "-BMB0") (class "Default")
      (node (ref "A03") (pin "D2") (pinfunction "P$2_D2") (pintype "bidirectional"))
      (node (ref "D03") (pin "D2") (pinfunction "P$2_D2") (pintype "bidirectional"))
    )
    (net (code "16") (name "-BMB1") (class "Default")
      (node (ref "A03") (pin "E2") (pinfunction "P$2_E2") (pintype "bidirectional"))
      (node (ref "D03") (pin "E2") (pinfunction "P$2_E2") (pintype "bidirectional"))
    )
    (net (code "17") (name "-BMB2") (class "Default")
      (node (ref "A03") (pin "H2") (pinfunction "P$2_H2") (pintype "bidirectional"))
      (node (ref "D03") (pin "H2") (pinfunction "P$2_H2") (pintype "bidirectional"))
    )
    (net (code "18") (name "-BMB3") (class "Default")
      (node (ref "A03") (pin "M2") (pinfunction "P$2_M2") (pintype "bidirectional"))
      (node (ref "D03") (pin "M2") (pinfunction "P$2_M2") (pintype "bidirectional"))
    )
    (net (code "19") (name "-BMB4") (class "Default")
      (node (ref "A03") (pin "S2") (pinfunction "P$2_S2") (pintype "bidirectional"))
      (node (ref "D03") (pin "S2") (pinfunction "P$2_S2") (pintype "bidirectional"))
    )
    (net (code "20") (name "-BMB5") (class "Default")
      (node (ref "A03") (pin "V2") (pinfunction "P$2_V2") (pintype "bidirectional"))
      (node (ref "D03") (pin "V2") (pinfunction "P$2_V2") (pintype "bidirectional"))
    )
    (net (code "21") (name "-BMB6") (class "Default")
      (node (ref "A04") (pin "E2") (pinfunction "P$2_E2") (pintype "bidirectional"))
      (node (ref "D04") (pin "E2") (pinfunction "P$2_E2") (pintype "bidirectional"))
    )
    (net (code "22") (name "-BMB7") (class "Default")
      (node (ref "A04") (pin "K2") (pinfunction "P$2_K2") (pintype "bidirectional"))
      (node (ref "D04") (pin "K2") (pinfunction "P$2_K2") (pintype "bidirectional"))
    )
    (net (code "23") (name "-BMB8") (class "Default")
      (node (ref "A04") (pin "P2") (pinfunction "P$2_P2") (pintype "bidirectional"))
      (node (ref "D04") (pin "P2") (pinfunction "P$2_P2") (pintype "bidirectional"))
    )
    (net (code "24") (name "-BMB9") (class "Default")
      (node (ref "A04") (pin "S2") (pinfunction "P$2_S2") (pintype "bidirectional"))
      (node (ref "D04") (pin "S2") (pinfunction "P$2_S2") (pintype "bidirectional"))
    )
    (net (code "25") (name "-BMB10") (class "Default")
      (node (ref "A04") (pin "T2") (pinfunction "P$2_T2") (pintype "bidirectional"))
      (node (ref "D04") (pin "T2") (pinfunction "P$2_T2") (pintype "bidirectional"))
    )
    (net (code "26") (name "-BMB11") (class "Default")
      (node (ref "A04") (pin "V2") (pinfunction "P$2_V2") (pintype "bidirectional"))
      (node (ref "D04") (pin "V2") (pinfunction "P$2_V2") (pintype "bidirectional"))
    )
    (net (code "27") (name "-BRK_IN_PRG") (class "Default")
      (node (ref "A19") (pin "H2") (pinfunction "0_H2") (pintype "open_collector"))
      (node (ref "B03") (pin "L2") (pinfunction "EN0_L2") (pintype "passive"))
    )
    (net (code "28") (name "-IM0") (class "Default")
      (node (ref "A05") (pin "D2") (pinfunction "P$2_D2") (pintype "bidirectional"))
      (node (ref "D05") (pin "D2") (pinfunction "P$2_D2") (pintype "bidirectional"))
    )
    (net (code "29") (name "-IM1") (class "Default")
      (node (ref "A05") (pin "E2") (pinfunction "P$2_E2") (pintype "bidirectional"))
      (node (ref "D05") (pin "E2") (pinfunction "P$2_E2") (pintype "bidirectional"))
    )
    (net (code "30") (name "-IM2") (class "Default")
      (node (ref "A05") (pin "H2") (pinfunction "P$2_H2") (pintype "bidirectional"))
      (node (ref "D05") (pin "H2") (pinfunction "P$2_H2") (pintype "bidirectional"))
    )
    (net (code "31") (name "-IM3") (class "Default")
      (node (ref "A05") (pin "K2") (pinfunction "P$2_K2") (pintype "bidirectional"))
      (node (ref "D05") (pin "K2") (pinfunction "P$2_K2") (pintype "bidirectional"))
    )
    (net (code "32") (name "-IM4") (class "Default")
      (node (ref "A05") (pin "M2") (pinfunction "P$2_M2") (pintype "bidirectional"))
      (node (ref "D05") (pin "M2") (pinfunction "P$2_M2") (pintype "bidirectional"))
    )
    (net (code "33") (name "-IM5") (class "Default")
      (node (ref "A05") (pin "P2") (pinfunction "P$2_P2") (pintype "bidirectional"))
      (node (ref "D05") (pin "P2") (pinfunction "P$2_P2") (pintype "bidirectional"))
    )
    (net (code "34") (name "-IM6") (class "Default")
      (node (ref "A05") (pin "S2") (pinfunction "P$2_S2") (pintype "bidirectional"))
      (node (ref "D05") (pin "S2") (pinfunction "P$2_S2") (pintype "bidirectional"))
    )
    (net (code "35") (name "-IM7") (class "Default")
      (node (ref "A05") (pin "T2") (pinfunction "P$2_T2") (pintype "bidirectional"))
      (node (ref "D05") (pin "T2") (pinfunction "P$2_T2") (pintype "bidirectional"))
    )
    (net (code "36") (name "-IM8") (class "Default")
      (node (ref "A05") (pin "V2") (pinfunction "P$2_V2") (pintype "bidirectional"))
      (node (ref "D05") (pin "V2") (pinfunction "P$2_V2") (pintype "bidirectional"))
    )
    (net (code "37") (name "-IM9") (class "Default")
      (node (ref "A06") (pin "D2") (pinfunction "P$2_D2") (pintype "bidirectional"))
      (node (ref "D06") (pin "D2") (pinfunction "P$2_D2") (pintype "bidirectional"))
    )
    (net (code "38") (name "-IM10") (class "Default")
      (node (ref "A06") (pin "E2") (pinfunction "P$2_E2") (pintype "bidirectional"))
      (node (ref "D06") (pin "E2") (pinfunction "P$2_E2") (pintype "bidirectional"))
    )
    (net (code "39") (name "-IM11") (class "Default")
      (node (ref "A06") (pin "H2") (pinfunction "P$2_H2") (pintype "bidirectional"))
      (node (ref "D06") (pin "H2") (pinfunction "P$2_H2") (pintype "bidirectional"))
    )
    (net (code "40") (name "-INTERRUPT") (class "Default")
      (node (ref "A06") (pin "M2") (pinfunction "P$2_M2") (pintype "bidirectional"))
      (node (ref "D06") (pin "M2") (pinfunction "P$2_M2") (pintype "bidirectional"))
    )
    (net (code "41") (name "-SKIP") (class "Default")
      (node (ref "A06") (pin "K2") (pinfunction "P$2_K2") (pintype "bidirectional"))
      (node (ref "D06") (pin "K2") (pinfunction "P$2_K2") (pintype "bidirectional"))
    )
    (net (code "42") (name "1-CA_INH") (class "Default")
      (node (ref "A10") (pin "M2") (pinfunction "P$2_M2") (pintype "bidirectional"))
      (node (ref "B32") (pin "N2") (pinfunction "O$1_N2") (pintype "open_collector"))
    )
    (net (code "43") (name "1-CA_INH0") (class "Default")
      (node (ref "C29") (pin "F2") (pinfunction "F_F2") (pintype "input"))
      (node (ref "D10") (pin "M2") (pinfunction "P$2_M2") (pintype "bidirectional"))
    )
    (net (code "44") (name "1-CA_INH1") (class "Default")
      (node (ref "C29") (pin "J2") (pinfunction "J_J2") (pintype "input"))
      (node (ref "D15") (pin "M2") (pinfunction "P$2_M2") (pintype "bidirectional"))
    )
    (net (code "45") (name "1-CA_INH2") (class "Default")
      (node (ref "C29") (pin "L2") (pinfunction "L_L2") (pintype "input"))
      (node (ref "D20") (pin "M2") (pinfunction "P$2_M2") (pintype "bidirectional"))
    )
    (net (code "46") (name "1-CA_INH3") (class "Default")
      (node (ref "C29") (pin "N2") (pinfunction "N_N2") (pintype "input"))
      (node (ref "D25") (pin "M2") (pinfunction "P$2_M2") (pintype "bidirectional"))
    )
    (net (code "47") (name "1-CA_INH4") (class "Default")
      (node (ref "C29") (pin "R2") (pinfunction "R_R2") (pintype "input"))
      (node (ref "D30") (pin "M2") (pinfunction "P$2_M2") (pintype "bidirectional"))
    )
    (net (code "48") (name "1-CA_INH5") (class "Default")
      (node (ref "A26") (pin "M2") (pinfunction "P$2_M2") (pintype "bidirectional"))
      (node (ref "C29") (pin "T2") (pinfunction "T_T2") (pintype "input"))
    )
    (net (code "49") (name "1-CA_INH6") (class "Default")
      (node (ref "A31") (pin "M2") (pinfunction "P$2_M2") (pintype "bidirectional"))
      (node (ref "C29") (pin "V2") (pinfunction "V_V2") (pintype "input"))
    )
    (net (code "50") (name "ADD_ACC") (class "Default")
      (node (ref "A08") (pin "S2") (pinfunction "P$2_S2") (pintype "bidirectional"))
      (node (ref "B23") (pin "E2") (pinfunction "I$2_E2") (pintype "input"))
      (node (ref "B30") (pin "E2") (pinfunction "I$2_E2") (pintype "input"))
      (node (ref "B30") (pin "L2") (pinfunction "I$2_L2") (pintype "input"))
      (node (ref "B30") (pin "S2") (pinfunction "I$2_S2") (pintype "input"))
      (node (ref "B31") (pin "E2") (pinfunction "I$2_E2") (pintype "input"))
      (node (ref "B31") (pin "L2") (pinfunction "I$2_L2") (pintype "input"))
      (node (ref "B31") (pin "S2") (pinfunction "I$2_S2") (pintype "input"))
      (node (ref "B32") (pin "H2") (pinfunction "I$1_H2") (pintype "input"))
    )
    (net (code "51") (name "ADD_ACC0") (class "Default")
      (node (ref "B27") (pin "H2") (pinfunction "H_H2") (pintype "output"))
      (node (ref "D08") (pin "S2") (pinfunction "P$2_S2") (pintype "bidirectional"))
    )
    (net (code "52") (name "ADD_ACC1") (class "Default")
      (node (ref "B27") (pin "N2") (pinfunction "H_N2") (pintype "output"))
      (node (ref "D13") (pin "S2") (pinfunction "P$2_S2") (pintype "bidirectional"))
    )
    (net (code "53") (name "ADD_ACC2") (class "Default")
      (node (ref "B27") (pin "U2") (pinfunction "H_U2") (pintype "output"))
      (node (ref "D18") (pin "S2") (pinfunction "P$2_S2") (pintype "bidirectional"))
    )
    (net (code "54") (name "ADD_ACC3") (class "Default")
      (node (ref "B28") (pin "H2") (pinfunction "H_H2") (pintype "output"))
      (node (ref "D23") (pin "S2") (pinfunction "P$2_S2") (pintype "bidirectional"))
    )
    (net (code "55") (name "ADD_ACC4") (class "Default")
      (node (ref "B28") (pin "N2") (pinfunction "H_N2") (pintype "output"))
      (node (ref "D28") (pin "S2") (pinfunction "P$2_S2") (pintype "bidirectional"))
    )
    (net (code "56") (name "ADD_ACC5") (class "Default")
      (node (ref "A24") (pin "S2") (pinfunction "P$2_S2") (pintype "bidirectional"))
      (node (ref "B28") (pin "U2") (pinfunction "H_U2") (pintype "output"))
    )
    (net (code "57") (name "ADD_ACC6") (class "Default")
      (node (ref "A29") (pin "S2") (pinfunction "P$2_S2") (pintype "bidirectional"))
      (node (ref "B29") (pin "H2") (pinfunction "H_H2") (pintype "output"))
    )
    (net (code "58") (name "B32M") (class "Default")
      (node (ref "B32") (pin "M2") (pinfunction "I$1_M2") (pintype "input"))
      (node (ref "PDP-12/8I/8") (pin "2") (pinfunction "2_2") (pintype "passive"))
      (node (ref "PDP-12/8I/8") (pin "4") (pinfunction "4_4") (pintype "passive"))
      (node (ref "PDP-12/8I/8") (pin "6") (pinfunction "6_6") (pintype "passive"))
    )
    (net (code "59") (name "BMPX0") (class "Default")
      (node (ref "B09") (pin "M2") (pinfunction "P$1_M2") (pintype "passive"))
      (node (ref "B10") (pin "D2") (pinfunction "O$1_D2") (pintype "open_collector"))
      (node (ref "D08") (pin "P2") (pinfunction "P$2_P2") (pintype "bidirectional"))
    )
    (net (code "60") (name "BMPX1") (class "Default")
      (node (ref "B09") (pin "N2") (pinfunction "P$1_N2") (pintype "passive"))
      (node (ref "B10") (pin "F2") (pinfunction "O$1_F2") (pintype "open_collector"))
      (node (ref "D13") (pin "P2") (pinfunction "P$2_P2") (pintype "bidirectional"))
    )
    (net (code "61") (name "BMPX2") (class "Default")
      (node (ref "B09") (pin "P2") (pinfunction "P$1_P2") (pintype "passive"))
      (node (ref "B10") (pin "J2") (pinfunction "O$1_J2") (pintype "open_collector"))
      (node (ref "D18") (pin "P2") (pinfunction "P$2_P2") (pintype "bidirectional"))
    )
    (net (code "62") (name "BMPX3") (class "Default")
      (node (ref "B09") (pin "R2") (pinfunction "P$1_R2") (pintype "passive"))
      (node (ref "B10") (pin "L2") (pinfunction "O$1_L2") (pintype "open_collector"))
      (node (ref "D23") (pin "P2") (pinfunction "P$2_P2") (pintype "bidirectional"))
    )
    (net (code "63") (name "BMPX4") (class "Default")
      (node (ref "B09") (pin "S2") (pinfunction "P$1_S2") (pintype "passive"))
      (node (ref "B10") (pin "N2") (pinfunction "O$1_N2") (pintype "open_collector"))
      (node (ref "D28") (pin "P2") (pinfunction "P$2_P2") (pintype "bidirectional"))
    )
    (net (code "64") (name "BMPX5") (class "Default")
      (node (ref "A24") (pin "P2") (pinfunction "P$2_P2") (pintype "bidirectional"))
      (node (ref "B09") (pin "T2") (pinfunction "P$1_T2") (pintype "passive"))
      (node (ref "B10") (pin "R2") (pinfunction "O$1_R2") (pintype "open_collector"))
    )
    (net (code "65") (name "BMPX6") (class "Default")
      (node (ref "A29") (pin "P2") (pinfunction "P$2_P2") (pintype "bidirectional"))
      (node (ref "B09") (pin "V2") (pinfunction "P$1_V2") (pintype "passive"))
      (node (ref "B10") (pin "T2") (pinfunction "O$1_T2") (pintype "open_collector"))
    )
    (net (code "66") (name "BREAK") (class "Default")
      (node (ref "A08") (pin "P2") (pinfunction "P$2_P2") (pintype "bidirectional"))
      (node (ref "A18") (pin "K2") (pinfunction "I$1_K2") (pintype "input"))
      (node (ref "A19") (pin "D2") (pinfunction "PU0_D2") (pintype "input"))
      (node (ref "B06") (pin "D2") (pinfunction "I$1_D2") (pintype "input"))
      (node (ref "B06") (pin "K2") (pinfunction "I$1_K2") (pintype "input"))
      (node (ref "B06") (pin "R2") (pinfunction "I$1_R2") (pintype "input"))
      (node (ref "B08") (pin "D2") (pinfunction "I$1_D2") (pintype "input"))
      (node (ref "B08") (pin "K2") (pinfunction "I$1_K2") (pintype "input"))
      (node (ref "B08") (pin "R2") (pinfunction "I$1_R2") (pintype "input"))
      (node (ref "B23") (pin "R2") (pinfunction "I$1_R2") (pintype "input"))
    )
    (net (code "67") (name "BRK_REQ") (class "Default")
      (node (ref "A08") (pin "K2") (pinfunction "P$2_K2") (pintype "bidirectional"))
      (node (ref "B32") (pin "D2") (pinfunction "O$1_D2") (pintype "open_collector"))
    )
    (net (code "68") (name "BRK_REQ0") (class "Default")
      (node (ref "B02") (pin "E2") (pinfunction "I$1_E2") (pintype "input"))
      (node (ref "B09") (pin "D2") (pinfunction "P$1_D2") (pintype "passive"))
      (node (ref "B14") (pin "L2") (pinfunction "EN1_L2") (pintype "input"))
      (node (ref "B23") (pin "K2") (pinfunction "I$1_K2") (pintype "input"))
      (node (ref "D08") (pin "K2") (pinfunction "P$2_K2") (pintype "bidirectional"))
    )
    (net (code "69") (name "BRK_REQ1") (class "Default")
      (node (ref "B02") (pin "H2") (pinfunction "I$1_H2") (pintype "input"))
      (node (ref "B09") (pin "E2") (pinfunction "P$1_E2") (pintype "passive"))
      (node (ref "B16") (pin "L2") (pinfunction "EN1_L2") (pintype "input"))
      (node (ref "B23") (pin "L2") (pinfunction "I$2_L2") (pintype "input"))
      (node (ref "D13") (pin "K2") (pinfunction "P$2_K2") (pintype "bidirectional"))
    )
    (net (code "70") (name "BRK_REQ2") (class "Default")
      (node (ref "B02") (pin "K2") (pinfunction "I$1_K2") (pintype "input"))
      (node (ref "B09") (pin "F2") (pinfunction "P$1_F2") (pintype "passive"))
      (node (ref "B17") (pin "L2") (pinfunction "EN1_L2") (pintype "input"))
      (node (ref "B22") (pin "D2") (pinfunction "D_D2") (pintype "input"))
      (node (ref "D18") (pin "K2") (pinfunction "P$2_K2") (pintype "bidirectional"))
    )
    (net (code "71") (name "BRK_REQ3") (class "Default")
      (node (ref "B02") (pin "M2") (pinfunction "I$1_M2") (pintype "input"))
      (node (ref "B09") (pin "H2") (pinfunction "P$1_H2") (pintype "passive"))
      (node (ref "B18") (pin "L2") (pinfunction "EN1_L2") (pintype "input"))
      (node (ref "B22") (pin "E2") (pinfunction "E_E2") (pintype "input"))
      (node (ref "D23") (pin "K2") (pinfunction "P$2_K2") (pintype "bidirectional"))
    )
    (net (code "72") (name "BRK_REQ4") (class "Default")
      (node (ref "B02") (pin "P2") (pinfunction "I$1_P2") (pintype "input"))
      (node (ref "B09") (pin "J2") (pinfunction "P$1_J2") (pintype "passive"))
      (node (ref "B19") (pin "L2") (pinfunction "EN1_L2") (pintype "input"))
      (node (ref "B22") (pin "H2") (pinfunction "D_H2") (pintype "input"))
      (node (ref "D28") (pin "K2") (pinfunction "P$2_K2") (pintype "bidirectional"))
    )
    (net (code "73") (name "BRK_REQ5") (class "Default")
      (node (ref "A24") (pin "K2") (pinfunction "P$2_K2") (pintype "bidirectional"))
      (node (ref "B02") (pin "S2") (pinfunction "I$1_S2") (pintype "input"))
      (node (ref "B09") (pin "K2") (pinfunction "P$1_K2") (pintype "passive"))
      (node (ref "B20") (pin "L2") (pinfunction "EN1_L2") (pintype "input"))
      (node (ref "B22") (pin "J2") (pinfunction "E_J2") (pintype "input"))
    )
    (net (code "74") (name "BRK_REQ6") (class "Default")
      (node (ref "A29") (pin "K2") (pinfunction "P$2_K2") (pintype "bidirectional"))
      (node (ref "B02") (pin "U2") (pinfunction "I$1_U2") (pintype "input"))
      (node (ref "B09") (pin "L2") (pinfunction "P$1_L2") (pintype "passive"))
      (node (ref "B21") (pin "L2") (pinfunction "EN1_L2") (pintype "input"))
      (node (ref "B22") (pin "L2") (pinfunction "D_L2") (pintype "input"))
    )
    (net (code "75") (name "BRK_SYNC_CLK") (class "Default")
      (node (ref "A06") (pin "T2") (pinfunction "P$2_T2") (pintype "bidirectional"))
      (node (ref "B13") (pin "U2") (pinfunction "I$1_U2") (pintype "input"))
      (node (ref "D06") (pin "T2") (pinfunction "P$2_T2") (pintype "bidirectional"))
    )
    (net (code "76") (name "BT1B") (class "Default")
      (node (ref "A02") (pin "S2") (pinfunction "P$2_S2") (pintype "bidirectional"))
      (node (ref "D02") (pin "S2") (pinfunction "P$2_S2") (pintype "bidirectional"))
      (node (ref "PDP-12/8I/8") (pin "5") (pinfunction "5_5") (pintype "passive"))
    )
    (net (code "77") (name "B_ENABLE0") (class "Default")
      (node (ref "A12") (pin "E2") (pinfunction "I$1_E2") (pintype "input"))
      (node (ref "A16") (pin "D2") (pinfunction "I$1_D2") (pintype "input"))
      (node (ref "A20") (pin "S2") (pinfunction "P$2_S2") (pintype "bidirectional"))
      (node (ref "B04") (pin "E2") (pinfunction "I$1_E2") (pintype "input"))
      (node (ref "B06") (pin "E2") (pinfunction "I$2_E2") (pintype "input"))
      (node (ref "B14") (pin "T2") (pinfunction "1_T2") (pintype "open_collector"))
    )
    (net (code "78") (name "B_ENABLE1") (class "Default")
      (node (ref "A12") (pin "H2") (pinfunction "I$1_H2") (pintype "input"))
      (node (ref "A16") (pin "K2") (pinfunction "I$1_K2") (pintype "input"))
      (node (ref "A20") (pin "P2") (pinfunction "P$2_P2") (pintype "bidirectional"))
      (node (ref "B04") (pin "H2") (pinfunction "I$1_H2") (pintype "input"))
      (node (ref "B06") (pin "L2") (pinfunction "I$2_L2") (pintype "input"))
      (node (ref "B16") (pin "T2") (pinfunction "1_T2") (pintype "open_collector"))
    )
    (net (code "79") (name "B_ENABLE2") (class "Default")
      (node (ref "A12") (pin "K2") (pinfunction "I$1_K2") (pintype "input"))
      (node (ref "A16") (pin "R2") (pinfunction "I$1_R2") (pintype "input"))
      (node (ref "A20") (pin "M2") (pinfunction "P$2_M2") (pintype "bidirectional"))
      (node (ref "B04") (pin "K2") (pinfunction "I$1_K2") (pintype "input"))
      (node (ref "B06") (pin "S2") (pinfunction "I$2_S2") (pintype "input"))
      (node (ref "B17") (pin "T2") (pinfunction "1_T2") (pintype "open_collector"))
    )
    (net (code "80") (name "B_ENABLE3") (class "Default")
      (node (ref "A12") (pin "M2") (pinfunction "I$1_M2") (pintype "input"))
      (node (ref "A17") (pin "D2") (pinfunction "I$1_D2") (pintype "input"))
      (node (ref "A20") (pin "K2") (pinfunction "P$2_K2") (pintype "bidirectional"))
      (node (ref "B04") (pin "M2") (pinfunction "I$1_M2") (pintype "input"))
      (node (ref "B08") (pin "E2") (pinfunction "I$2_E2") (pintype "input"))
      (node (ref "B18") (pin "T2") (pinfunction "1_T2") (pintype "open_collector"))
    )
    (net (code "81") (name "B_ENABLE4") (class "Default")
      (node (ref "A12") (pin "P2") (pinfunction "I$1_P2") (pintype "input"))
      (node (ref "A17") (pin "K2") (pinfunction "I$1_K2") (pintype "input"))
      (node (ref "A20") (pin "H2") (pinfunction "P$2_H2") (pintype "bidirectional"))
      (node (ref "B04") (pin "P2") (pinfunction "I$1_P2") (pintype "input"))
      (node (ref "B08") (pin "L2") (pinfunction "I$2_L2") (pintype "input"))
      (node (ref "B19") (pin "T2") (pinfunction "1_T2") (pintype "open_collector"))
    )
    (net (code "82") (name "B_ENABLE5") (class "Default")
      (node (ref "A12") (pin "S2") (pinfunction "I$1_S2") (pintype "input"))
      (node (ref "A17") (pin "R2") (pinfunction "I$1_R2") (pintype "input"))
      (node (ref "A20") (pin "E2") (pinfunction "P$2_E2") (pintype "bidirectional"))
      (node (ref "B04") (pin "S2") (pinfunction "I$1_S2") (pintype "input"))
      (node (ref "B08") (pin "S2") (pinfunction "I$2_S2") (pintype "input"))
      (node (ref "B20") (pin "T2") (pinfunction "1_T2") (pintype "open_collector"))
    )
    (net (code "83") (name "B_ENABLE6") (class "Default")
      (node (ref "A12") (pin "U2") (pinfunction "I$1_U2") (pintype "input"))
      (node (ref "A18") (pin "D2") (pinfunction "I$1_D2") (pintype "input"))
      (node (ref "A20") (pin "D2") (pinfunction "P$2_D2") (pintype "bidirectional"))
      (node (ref "B04") (pin "U2") (pinfunction "I$1_U2") (pintype "input"))
      (node (ref "B21") (pin "T2") (pinfunction "1_T2") (pintype "open_collector"))
      (node (ref "B23") (pin "S2") (pinfunction "I$2_S2") (pintype "input"))
    )
    (net (code "84") (name "CYC_SEL") (class "Default")
      (node (ref "A10") (pin "K2") (pinfunction "P$2_K2") (pintype "bidirectional"))
      (node (ref "A19") (pin "L2") (pinfunction "EN1_L2") (pintype "input"))
      (node (ref "B15") (pin "R2") (pinfunction "O$1_R2") (pintype "open_collector"))
    )
    (net (code "85") (name "CYC_SEL0") (class "Default")
      (node (ref "C13") (pin "F2") (pinfunction "F_F2") (pintype "input"))
      (node (ref "D10") (pin "K2") (pinfunction "P$2_K2") (pintype "bidirectional"))
    )
    (net (code "86") (name "CYC_SEL1") (class "Default")
      (node (ref "C13") (pin "J2") (pinfunction "J_J2") (pintype "input"))
      (node (ref "D15") (pin "K2") (pinfunction "P$2_K2") (pintype "bidirectional"))
    )
    (net (code "87") (name "CYC_SEL2") (class "Default")
      (node (ref "C13") (pin "L2") (pinfunction "L_L2") (pintype "input"))
      (node (ref "D20") (pin "K2") (pinfunction "P$2_K2") (pintype "bidirectional"))
    )
    (net (code "88") (name "CYC_SEL3") (class "Default")
      (node (ref "C13") (pin "N2") (pinfunction "N_N2") (pintype "input"))
      (node (ref "D25") (pin "K2") (pinfunction "P$2_K2") (pintype "bidirectional"))
    )
    (net (code "89") (name "CYC_SEL4") (class "Default")
      (node (ref "C13") (pin "R2") (pinfunction "R_R2") (pintype "input"))
      (node (ref "D30") (pin "K2") (pinfunction "P$2_K2") (pintype "bidirectional"))
    )
    (net (code "90") (name "CYC_SEL5") (class "Default")
      (node (ref "A26") (pin "K2") (pinfunction "P$2_K2") (pintype "bidirectional"))
      (node (ref "C13") (pin "T2") (pinfunction "T_T2") (pintype "input"))
    )
    (net (code "91") (name "CYC_SEL6") (class "Default")
      (node (ref "A31") (pin "K2") (pinfunction "P$2_K2") (pintype "bidirectional"))
      (node (ref "C13") (pin "V2") (pinfunction "V_V2") (pintype "input"))
    )
    (net (code "92") (name "DA0") (class "Default")
      (node (ref "A07") (pin "D2") (pinfunction "P$2_D2") (pintype "bidirectional"))
      (node (ref "B07") (pin "D2") (pinfunction "O$1_D2") (pintype "open_collector"))
    )
    (net (code "93") (name "DA0-0") (class "Default")
      (node (ref "C01") (pin "F2") (pinfunction "F_F2") (pintype "input"))
      (node (ref "D07") (pin "D2") (pinfunction "P$2_D2") (pintype "bidirectional"))
    )
    (net (code "94") (name "DA0-1") (class "Default")
      (node (ref "C01") (pin "J2") (pinfunction "J_J2") (pintype "input"))
      (node (ref "D12") (pin "D2") (pinfunction "P$2_D2") (pintype "bidirectional"))
    )
    (net (code "95") (name "DA0-2") (class "Default")
      (node (ref "C01") (pin "L2") (pinfunction "L_L2") (pintype "input"))
      (node (ref "D17") (pin "D2") (pinfunction "P$2_D2") (pintype "bidirectional"))
    )
    (net (code "96") (name "DA0-3") (class "Default")
      (node (ref "C01") (pin "N2") (pinfunction "N_N2") (pintype "input"))
      (node (ref "D22") (pin "D2") (pinfunction "P$2_D2") (pintype "bidirectional"))
    )
    (net (code "97") (name "DA0-4") (class "Default")
      (node (ref "C01") (pin "R2") (pinfunction "R_R2") (pintype "input"))
      (node (ref "D27") (pin "D2") (pinfunction "P$2_D2") (pintype "bidirectional"))
    )
    (net (code "98") (name "DA0-5") (class "Default")
      (node (ref "A23") (pin "D2") (pinfunction "P$2_D2") (pintype "bidirectional"))
      (node (ref "C01") (pin "T2") (pinfunction "T_T2") (pintype "input"))
    )
    (net (code "99") (name "DA0-6") (class "Default")
      (node (ref "A28") (pin "D2") (pinfunction "P$2_D2") (pintype "bidirectional"))
      (node (ref "C01") (pin "V2") (pinfunction "V_V2") (pintype "input"))
    )
    (net (code "100") (name "DA1") (class "Default")
      (node (ref "A07") (pin "E2") (pinfunction "P$2_E2") (pintype "bidirectional"))
      (node (ref "B07") (pin "F2") (pinfunction "O$1_F2") (pintype "open_collector"))
    )
    (net (code "101") (name "DA1-0") (class "Default")
      (node (ref "C02") (pin "F2") (pinfunction "F_F2") (pintype "input"))
      (node (ref "D07") (pin "E2") (pinfunction "P$2_E2") (pintype "bidirectional"))
    )
    (net (code "102") (name "DA1-1") (class "Default")
      (node (ref "C02") (pin "J2") (pinfunction "J_J2") (pintype "input"))
      (node (ref "D12") (pin "E2") (pinfunction "P$2_E2") (pintype "bidirectional"))
    )
    (net (code "103") (name "DA1-2") (class "Default")
      (node (ref "C02") (pin "L2") (pinfunction "L_L2") (pintype "input"))
      (node (ref "D17") (pin "E2") (pinfunction "P$2_E2") (pintype "bidirectional"))
    )
    (net (code "104") (name "DA1-3") (class "Default")
      (node (ref "C02") (pin "N2") (pinfunction "N_N2") (pintype "input"))
      (node (ref "D22") (pin "E2") (pinfunction "P$2_E2") (pintype "bidirectional"))
    )
    (net (code "105") (name "DA1-4") (class "Default")
      (node (ref "C02") (pin "R2") (pinfunction "R_R2") (pintype "input"))
      (node (ref "D27") (pin "E2") (pinfunction "P$2_E2") (pintype "bidirectional"))
    )
    (net (code "106") (name "DA1-5") (class "Default")
      (node (ref "A23") (pin "E2") (pinfunction "P$2_E2") (pintype "bidirectional"))
      (node (ref "C02") (pin "T2") (pinfunction "T_T2") (pintype "input"))
    )
    (net (code "107") (name "DA1-6") (class "Default")
      (node (ref "A28") (pin "E2") (pinfunction "P$2_E2") (pintype "bidirectional"))
      (node (ref "C02") (pin "V2") (pinfunction "V_V2") (pintype "input"))
    )
    (net (code "108") (name "DA2") (class "Default")
      (node (ref "A07") (pin "H2") (pinfunction "P$2_H2") (pintype "bidirectional"))
      (node (ref "B07") (pin "J2") (pinfunction "O$1_J2") (pintype "open_collector"))
    )
    (net (code "109") (name "DA2-0") (class "Default")
      (node (ref "C03") (pin "F2") (pinfunction "F_F2") (pintype "input"))
      (node (ref "D07") (pin "H2") (pinfunction "P$2_H2") (pintype "bidirectional"))
    )
    (net (code "110") (name "DA2-1") (class "Default")
      (node (ref "C03") (pin "J2") (pinfunction "J_J2") (pintype "input"))
      (node (ref "D12") (pin "H2") (pinfunction "P$2_H2") (pintype "bidirectional"))
    )
    (net (code "111") (name "DA2-2") (class "Default")
      (node (ref "C03") (pin "L2") (pinfunction "L_L2") (pintype "input"))
      (node (ref "D17") (pin "H2") (pinfunction "P$2_H2") (pintype "bidirectional"))
    )
    (net (code "112") (name "DA2-3") (class "Default")
      (node (ref "C03") (pin "N2") (pinfunction "N_N2") (pintype "input"))
      (node (ref "D22") (pin "H2") (pinfunction "P$2_H2") (pintype "bidirectional"))
    )
    (net (code "113") (name "DA2-4") (class "Default")
      (node (ref "C03") (pin "R2") (pinfunction "R_R2") (pintype "input"))
      (node (ref "D27") (pin "H2") (pinfunction "P$2_H2") (pintype "bidirectional"))
    )
    (net (code "114") (name "DA2-5") (class "Default")
      (node (ref "A23") (pin "H2") (pinfunction "P$2_H2") (pintype "bidirectional"))
      (node (ref "C03") (pin "T2") (pinfunction "T_T2") (pintype "input"))
    )
    (net (code "115") (name "DA2-6") (class "Default")
      (node (ref "A28") (pin "H2") (pinfunction "P$2_H2") (pintype "bidirectional"))
      (node (ref "C03") (pin "V2") (pinfunction "V_V2") (pintype "input"))
    )
    (net (code "116") (name "DA3") (class "Default")
      (node (ref "A07") (pin "K2") (pinfunction "P$2_K2") (pintype "bidirectional"))
      (node (ref "B07") (pin "L2") (pinfunction "O$1_L2") (pintype "open_collector"))
    )
    (net (code "117") (name "DA3-0") (class "Default")
      (node (ref "C04") (pin "F2") (pinfunction "F_F2") (pintype "input"))
      (node (ref "D07") (pin "K2") (pinfunction "P$2_K2") (pintype "bidirectional"))
    )
    (net (code "118") (name "DA3-1") (class "Default")
      (node (ref "C04") (pin "J2") (pinfunction "J_J2") (pintype "input"))
      (node (ref "D12") (pin "K2") (pinfunction "P$2_K2") (pintype "bidirectional"))
    )
    (net (code "119") (name "DA3-2") (class "Default")
      (node (ref "C04") (pin "L2") (pinfunction "L_L2") (pintype "input"))
      (node (ref "D17") (pin "K2") (pinfunction "P$2_K2") (pintype "bidirectional"))
    )
    (net (code "120") (name "DA3-3") (class "Default")
      (node (ref "C04") (pin "N2") (pinfunction "N_N2") (pintype "input"))
      (node (ref "D22") (pin "K2") (pinfunction "P$2_K2") (pintype "bidirectional"))
    )
    (net (code "121") (name "DA3-4") (class "Default")
      (node (ref "C04") (pin "R2") (pinfunction "R_R2") (pintype "input"))
      (node (ref "D27") (pin "K2") (pinfunction "P$2_K2") (pintype "bidirectional"))
    )
    (net (code "122") (name "DA3-5") (class "Default")
      (node (ref "A23") (pin "K2") (pinfunction "P$2_K2") (pintype "bidirectional"))
      (node (ref "C04") (pin "T2") (pinfunction "T_T2") (pintype "input"))
    )
    (net (code "123") (name "DA3-6") (class "Default")
      (node (ref "A28") (pin "K2") (pinfunction "P$2_K2") (pintype "bidirectional"))
      (node (ref "C04") (pin "V2") (pinfunction "V_V2") (pintype "input"))
    )
    (net (code "124") (name "DA4") (class "Default")
      (node (ref "A07") (pin "M2") (pinfunction "P$2_M2") (pintype "bidirectional"))
      (node (ref "B07") (pin "N2") (pinfunction "O$1_N2") (pintype "open_collector"))
    )
    (net (code "125") (name "DA4-0") (class "Default")
      (node (ref "C05") (pin "F2") (pinfunction "F_F2") (pintype "input"))
      (node (ref "D07") (pin "M2") (pinfunction "P$2_M2") (pintype "bidirectional"))
    )
    (net (code "126") (name "DA4-1") (class "Default")
      (node (ref "C05") (pin "J2") (pinfunction "J_J2") (pintype "input"))
      (node (ref "D12") (pin "M2") (pinfunction "P$2_M2") (pintype "bidirectional"))
    )
    (net (code "127") (name "DA4-2") (class "Default")
      (node (ref "C05") (pin "L2") (pinfunction "L_L2") (pintype "input"))
      (node (ref "D17") (pin "M2") (pinfunction "P$2_M2") (pintype "bidirectional"))
    )
    (net (code "128") (name "DA4-3") (class "Default")
      (node (ref "C05") (pin "N2") (pinfunction "N_N2") (pintype "input"))
      (node (ref "D22") (pin "M2") (pinfunction "P$2_M2") (pintype "bidirectional"))
    )
    (net (code "129") (name "DA4-4") (class "Default")
      (node (ref "C05") (pin "R2") (pinfunction "R_R2") (pintype "input"))
      (node (ref "D27") (pin "M2") (pinfunction "P$2_M2") (pintype "bidirectional"))
    )
    (net (code "130") (name "DA4-5") (class "Default")
      (node (ref "A23") (pin "M2") (pinfunction "P$2_M2") (pintype "bidirectional"))
      (node (ref "C05") (pin "T2") (pinfunction "T_T2") (pintype "input"))
    )
    (net (code "131") (name "DA4-6") (class "Default")
      (node (ref "A28") (pin "M2") (pinfunction "P$2_M2") (pintype "bidirectional"))
      (node (ref "C05") (pin "V2") (pinfunction "V_V2") (pintype "input"))
    )
    (net (code "132") (name "DA5") (class "Default")
      (node (ref "A07") (pin "P2") (pinfunction "P$2_P2") (pintype "bidirectional"))
      (node (ref "B07") (pin "R2") (pinfunction "O$1_R2") (pintype "open_collector"))
    )
    (net (code "133") (name "DA5-0") (class "Default")
      (node (ref "C06") (pin "F2") (pinfunction "F_F2") (pintype "input"))
      (node (ref "D07") (pin "P2") (pinfunction "P$2_P2") (pintype "bidirectional"))
    )
    (net (code "134") (name "DA5-1") (class "Default")
      (node (ref "C06") (pin "J2") (pinfunction "J_J2") (pintype "input"))
      (node (ref "D12") (pin "P2") (pinfunction "P$2_P2") (pintype "bidirectional"))
    )
    (net (code "135") (name "DA5-2") (class "Default")
      (node (ref "C06") (pin "L2") (pinfunction "L_L2") (pintype "input"))
      (node (ref "D17") (pin "P2") (pinfunction "P$2_P2") (pintype "bidirectional"))
    )
    (net (code "136") (name "DA5-3") (class "Default")
      (node (ref "C06") (pin "N2") (pinfunction "N_N2") (pintype "input"))
      (node (ref "D22") (pin "P2") (pinfunction "P$2_P2") (pintype "bidirectional"))
    )
    (net (code "137") (name "DA5-4") (class "Default")
      (node (ref "C06") (pin "R2") (pinfunction "R_R2") (pintype "input"))
      (node (ref "D27") (pin "P2") (pinfunction "P$2_P2") (pintype "bidirectional"))
    )
    (net (code "138") (name "DA5-5") (class "Default")
      (node (ref "A23") (pin "P2") (pinfunction "P$2_P2") (pintype "bidirectional"))
      (node (ref "C06") (pin "T2") (pinfunction "T_T2") (pintype "input"))
    )
    (net (code "139") (name "DA5-6") (class "Default")
      (node (ref "A28") (pin "P2") (pinfunction "P$2_P2") (pintype "bidirectional"))
      (node (ref "C06") (pin "V2") (pinfunction "V_V2") (pintype "input"))
    )
    (net (code "140") (name "DA6") (class "Default")
      (node (ref "A07") (pin "S2") (pinfunction "P$2_S2") (pintype "bidirectional"))
      (node (ref "B07") (pin "T2") (pinfunction "O$1_T2") (pintype "open_collector"))
    )
    (net (code "141") (name "DA6-0") (class "Default")
      (node (ref "C07") (pin "F2") (pinfunction "F_F2") (pintype "input"))
      (node (ref "D07") (pin "S2") (pinfunction "P$2_S2") (pintype "bidirectional"))
    )
    (net (code "142") (name "DA6-1") (class "Default")
      (node (ref "C07") (pin "J2") (pinfunction "J_J2") (pintype "input"))
      (node (ref "D12") (pin "S2") (pinfunction "P$2_S2") (pintype "bidirectional"))
    )
    (net (code "143") (name "DA6-2") (class "Default")
      (node (ref "C07") (pin "L2") (pinfunction "L_L2") (pintype "input"))
      (node (ref "D17") (pin "S2") (pinfunction "P$2_S2") (pintype "bidirectional"))
    )
    (net (code "144") (name "DA6-3") (class "Default")
      (node (ref "C07") (pin "N2") (pinfunction "N_N2") (pintype "input"))
      (node (ref "D22") (pin "S2") (pinfunction "P$2_S2") (pintype "bidirectional"))
    )
    (net (code "145") (name "DA6-4") (class "Default")
      (node (ref "C07") (pin "R2") (pinfunction "R_R2") (pintype "input"))
      (node (ref "D27") (pin "S2") (pinfunction "P$2_S2") (pintype "bidirectional"))
    )
    (net (code "146") (name "DA6-5") (class "Default")
      (node (ref "A23") (pin "S2") (pinfunction "P$2_S2") (pintype "bidirectional"))
      (node (ref "C07") (pin "T2") (pinfunction "T_T2") (pintype "input"))
    )
    (net (code "147") (name "DA6-6") (class "Default")
      (node (ref "A28") (pin "S2") (pinfunction "P$2_S2") (pintype "bidirectional"))
      (node (ref "C07") (pin "V2") (pinfunction "V_V2") (pintype "input"))
    )
    (net (code "148") (name "DA7") (class "Default")
      (node (ref "A07") (pin "T2") (pinfunction "P$2_T2") (pintype "bidirectional"))
      (node (ref "B15") (pin "D2") (pinfunction "O$1_D2") (pintype "open_collector"))
    )
    (net (code "149") (name "DA7-0") (class "Default")
      (node (ref "C08") (pin "F2") (pinfunction "F_F2") (pintype "input"))
      (node (ref "D07") (pin "T2") (pinfunction "P$2_T2") (pintype "bidirectional"))
    )
    (net (code "150") (name "DA7-1") (class "Default")
      (node (ref "C08") (pin "J2") (pinfunction "J_J2") (pintype "input"))
      (node (ref "D12") (pin "T2") (pinfunction "P$2_T2") (pintype "bidirectional"))
    )
    (net (code "151") (name "DA7-2") (class "Default")
      (node (ref "C08") (pin "L2") (pinfunction "L_L2") (pintype "input"))
      (node (ref "D17") (pin "T2") (pinfunction "P$2_T2") (pintype "bidirectional"))
    )
    (net (code "152") (name "DA7-3") (class "Default")
      (node (ref "C08") (pin "N2") (pinfunction "N_N2") (pintype "input"))
      (node (ref "D22") (pin "T2") (pinfunction "P$2_T2") (pintype "bidirectional"))
    )
    (net (code "153") (name "DA7-4") (class "Default")
      (node (ref "C08") (pin "R2") (pinfunction "R_R2") (pintype "input"))
      (node (ref "D27") (pin "T2") (pinfunction "P$2_T2") (pintype "bidirectional"))
    )
    (net (code "154") (name "DA7-5") (class "Default")
      (node (ref "A23") (pin "T2") (pinfunction "P$2_T2") (pintype "bidirectional"))
      (node (ref "C08") (pin "T2") (pinfunction "T_T2") (pintype "input"))
    )
    (net (code "155") (name "DA7-6") (class "Default")
      (node (ref "A28") (pin "T2") (pinfunction "P$2_T2") (pintype "bidirectional"))
      (node (ref "C08") (pin "V2") (pinfunction "V_V2") (pintype "input"))
    )
    (net (code "156") (name "DA8") (class "Default")
      (node (ref "A07") (pin "V2") (pinfunction "P$2_V2") (pintype "bidirectional"))
      (node (ref "B15") (pin "F2") (pinfunction "O$1_F2") (pintype "open_collector"))
    )
    (net (code "157") (name "DA8-0") (class "Default")
      (node (ref "C09") (pin "F2") (pinfunction "F_F2") (pintype "input"))
      (node (ref "D07") (pin "V2") (pinfunction "P$2_V2") (pintype "bidirectional"))
    )
    (net (code "158") (name "DA8-1") (class "Default")
      (node (ref "C09") (pin "J2") (pinfunction "J_J2") (pintype "input"))
      (node (ref "D12") (pin "V2") (pinfunction "P$2_V2") (pintype "bidirectional"))
    )
    (net (code "159") (name "DA8-2") (class "Default")
      (node (ref "C09") (pin "L2") (pinfunction "L_L2") (pintype "input"))
      (node (ref "D17") (pin "V2") (pinfunction "P$2_V2") (pintype "bidirectional"))
    )
    (net (code "160") (name "DA8-3") (class "Default")
      (node (ref "C09") (pin "N2") (pinfunction "N_N2") (pintype "input"))
      (node (ref "D22") (pin "V2") (pinfunction "P$2_V2") (pintype "bidirectional"))
    )
    (net (code "161") (name "DA8-4") (class "Default")
      (node (ref "C09") (pin "R2") (pinfunction "R_R2") (pintype "input"))
      (node (ref "D27") (pin "V2") (pinfunction "P$2_V2") (pintype "bidirectional"))
    )
    (net (code "162") (name "DA8-5") (class "Default")
      (node (ref "A23") (pin "V2") (pinfunction "P$2_V2") (pintype "bidirectional"))
      (node (ref "C09") (pin "T2") (pinfunction "T_T2") (pintype "input"))
    )
    (net (code "163") (name "DA8-6") (class "Default")
      (node (ref "A28") (pin "V2") (pinfunction "P$2_V2") (pintype "bidirectional"))
      (node (ref "C09") (pin "V2") (pinfunction "V_V2") (pintype "input"))
    )
    (net (code "164") (name "DA9") (class "Default")
      (node (ref "A08") (pin "D2") (pinfunction "P$2_D2") (pintype "bidirectional"))
      (node (ref "B15") (pin "J2") (pinfunction "O$1_J2") (pintype "open_collector"))
    )
    (net (code "165") (name "DA9-0") (class "Default")
      (node (ref "C10") (pin "F2") (pinfunction "F_F2") (pintype "input"))
      (node (ref "D08") (pin "D2") (pinfunction "P$2_D2") (pintype "bidirectional"))
    )
    (net (code "166") (name "DA9-1") (class "Default")
      (node (ref "C10") (pin "J2") (pinfunction "J_J2") (pintype "input"))
      (node (ref "D13") (pin "D2") (pinfunction "P$2_D2") (pintype "bidirectional"))
    )
    (net (code "167") (name "DA9-2") (class "Default")
      (node (ref "C10") (pin "L2") (pinfunction "L_L2") (pintype "input"))
      (node (ref "D18") (pin "D2") (pinfunction "P$2_D2") (pintype "bidirectional"))
    )
    (net (code "168") (name "DA9-3") (class "Default")
      (node (ref "C10") (pin "N2") (pinfunction "N_N2") (pintype "input"))
      (node (ref "D23") (pin "D2") (pinfunction "P$2_D2") (pintype "bidirectional"))
    )
    (net (code "169") (name "DA9-4") (class "Default")
      (node (ref "C10") (pin "R2") (pinfunction "R_R2") (pintype "input"))
      (node (ref "D28") (pin "D2") (pinfunction "P$2_D2") (pintype "bidirectional"))
    )
    (net (code "170") (name "DA9-5") (class "Default")
      (node (ref "A24") (pin "D2") (pinfunction "P$2_D2") (pintype "bidirectional"))
      (node (ref "C10") (pin "T2") (pinfunction "T_T2") (pintype "input"))
    )
    (net (code "171") (name "DA9-6") (class "Default")
      (node (ref "A29") (pin "D2") (pinfunction "P$2_D2") (pintype "bidirectional"))
      (node (ref "C10") (pin "V2") (pinfunction "V_V2") (pintype "input"))
    )
    (net (code "172") (name "DA10") (class "Default")
      (node (ref "A08") (pin "E2") (pinfunction "P$2_E2") (pintype "bidirectional"))
      (node (ref "B15") (pin "L2") (pinfunction "O$1_L2") (pintype "open_collector"))
    )
    (net (code "173") (name "DA10-0") (class "Default")
      (node (ref "C11") (pin "F2") (pinfunction "F_F2") (pintype "input"))
      (node (ref "D08") (pin "E2") (pinfunction "P$2_E2") (pintype "bidirectional"))
    )
    (net (code "174") (name "DA10-1") (class "Default")
      (node (ref "C11") (pin "J2") (pinfunction "J_J2") (pintype "input"))
      (node (ref "D13") (pin "E2") (pinfunction "P$2_E2") (pintype "bidirectional"))
    )
    (net (code "175") (name "DA10-2") (class "Default")
      (node (ref "C11") (pin "L2") (pinfunction "L_L2") (pintype "input"))
      (node (ref "D18") (pin "E2") (pinfunction "P$2_E2") (pintype "bidirectional"))
    )
    (net (code "176") (name "DA10-3") (class "Default")
      (node (ref "C11") (pin "N2") (pinfunction "N_N2") (pintype "input"))
      (node (ref "D23") (pin "E2") (pinfunction "P$2_E2") (pintype "bidirectional"))
    )
    (net (code "177") (name "DA10-4") (class "Default")
      (node (ref "C11") (pin "R2") (pinfunction "R_R2") (pintype "input"))
      (node (ref "D28") (pin "E2") (pinfunction "P$2_E2") (pintype "bidirectional"))
    )
    (net (code "178") (name "DA10-5") (class "Default")
      (node (ref "A24") (pin "E2") (pinfunction "P$2_E2") (pintype "bidirectional"))
      (node (ref "C11") (pin "T2") (pinfunction "T_T2") (pintype "input"))
    )
    (net (code "179") (name "DA10-6") (class "Default")
      (node (ref "A29") (pin "E2") (pinfunction "P$2_E2") (pintype "bidirectional"))
      (node (ref "C11") (pin "V2") (pinfunction "V_V2") (pintype "input"))
    )
    (net (code "180") (name "DA11") (class "Default")
      (node (ref "A08") (pin "H2") (pinfunction "P$2_H2") (pintype "bidirectional"))
      (node (ref "B15") (pin "N2") (pinfunction "O$1_N2") (pintype "open_collector"))
    )
    (net (code "181") (name "DA11-0") (class "Default")
      (node (ref "C12") (pin "F2") (pinfunction "F_F2") (pintype "input"))
      (node (ref "D08") (pin "H2") (pinfunction "P$2_H2") (pintype "bidirectional"))
    )
    (net (code "182") (name "DA11-1") (class "Default")
      (node (ref "C12") (pin "J2") (pinfunction "J_J2") (pintype "input"))
      (node (ref "D13") (pin "H2") (pinfunction "P$2_H2") (pintype "bidirectional"))
    )
    (net (code "183") (name "DA11-2") (class "Default")
      (node (ref "C12") (pin "L2") (pinfunction "L_L2") (pintype "input"))
      (node (ref "D18") (pin "H2") (pinfunction "P$2_H2") (pintype "bidirectional"))
    )
    (net (code "184") (name "DA11-3") (class "Default")
      (node (ref "C12") (pin "N2") (pinfunction "N_N2") (pintype "input"))
      (node (ref "D23") (pin "H2") (pinfunction "P$2_H2") (pintype "bidirectional"))
    )
    (net (code "185") (name "DA11-4") (class "Default")
      (node (ref "C12") (pin "R2") (pinfunction "R_R2") (pintype "input"))
      (node (ref "D28") (pin "H2") (pinfunction "P$2_H2") (pintype "bidirectional"))
    )
    (net (code "186") (name "DA11-5") (class "Default")
      (node (ref "A24") (pin "H2") (pinfunction "P$2_H2") (pintype "bidirectional"))
      (node (ref "C12") (pin "T2") (pinfunction "T_T2") (pintype "input"))
    )
    (net (code "187") (name "DA11-6") (class "Default")
      (node (ref "A29") (pin "H2") (pinfunction "P$2_H2") (pintype "bidirectional"))
      (node (ref "C12") (pin "V2") (pinfunction "V_V2") (pintype "input"))
    )
    (net (code "188") (name "DAEX1") (class "Default")
      (node (ref "A11") (pin "D2") (pinfunction "P$2_D2") (pintype "bidirectional"))
      (node (ref "B25") (pin "F2") (pinfunction "O$1_F2") (pintype "open_collector"))
    )
    (net (code "189") (name "DAEX1-0") (class "Default")
      (node (ref "C16") (pin "F2") (pinfunction "F_F2") (pintype "input"))
      (node (ref "D11") (pin "D2") (pinfunction "P$2_D2") (pintype "bidirectional"))
    )
    (net (code "190") (name "DAEX1-1") (class "Default")
      (node (ref "C16") (pin "J2") (pinfunction "J_J2") (pintype "input"))
      (node (ref "D16") (pin "D2") (pinfunction "P$2_D2") (pintype "bidirectional"))
    )
    (net (code "191") (name "DAEX1-2") (class "Default")
      (node (ref "C16") (pin "L2") (pinfunction "L_L2") (pintype "input"))
      (node (ref "D21") (pin "D2") (pinfunction "P$2_D2") (pintype "bidirectional"))
    )
    (net (code "192") (name "DAEX1-3") (class "Default")
      (node (ref "C16") (pin "N2") (pinfunction "N_N2") (pintype "input"))
      (node (ref "D26") (pin "D2") (pinfunction "P$2_D2") (pintype "bidirectional"))
    )
    (net (code "193") (name "DAEX1-4") (class "Default")
      (node (ref "C16") (pin "R2") (pinfunction "R_R2") (pintype "input"))
      (node (ref "D31") (pin "D2") (pinfunction "P$2_D2") (pintype "bidirectional"))
    )
    (net (code "194") (name "DAEX1-5") (class "Default")
      (node (ref "A27") (pin "D2") (pinfunction "P$2_D2") (pintype "bidirectional"))
      (node (ref "C16") (pin "T2") (pinfunction "T_T2") (pintype "input"))
    )
    (net (code "195") (name "DAEX1-6") (class "Default")
      (node (ref "A32") (pin "D2") (pinfunction "P$2_D2") (pintype "bidirectional"))
      (node (ref "C16") (pin "V2") (pinfunction "V_V2") (pintype "input"))
    )
    (net (code "196") (name "DAEX2") (class "Default")
      (node (ref "A11") (pin "E2") (pinfunction "P$2_E2") (pintype "bidirectional"))
      (node (ref "B25") (pin "D2") (pinfunction "O$1_D2") (pintype "open_collector"))
    )
    (net (code "197") (name "DAEX2-0") (class "Default")
      (node (ref "C15") (pin "F2") (pinfunction "F_F2") (pintype "input"))
      (node (ref "D11") (pin "E2") (pinfunction "P$2_E2") (pintype "bidirectional"))
    )
    (net (code "198") (name "DAEX2-1") (class "Default")
      (node (ref "C15") (pin "J2") (pinfunction "J_J2") (pintype "input"))
      (node (ref "D16") (pin "E2") (pinfunction "P$2_E2") (pintype "bidirectional"))
    )
    (net (code "199") (name "DAEX2-2") (class "Default")
      (node (ref "C15") (pin "L2") (pinfunction "L_L2") (pintype "input"))
      (node (ref "D21") (pin "E2") (pinfunction "P$2_E2") (pintype "bidirectional"))
    )
    (net (code "200") (name "DAEX2-3") (class "Default")
      (node (ref "C15") (pin "N2") (pinfunction "N_N2") (pintype "input"))
      (node (ref "D26") (pin "E2") (pinfunction "P$2_E2") (pintype "bidirectional"))
    )
    (net (code "201") (name "DAEX2-4") (class "Default")
      (node (ref "C15") (pin "R2") (pinfunction "R_R2") (pintype "input"))
      (node (ref "D31") (pin "E2") (pinfunction "P$2_E2") (pintype "bidirectional"))
    )
    (net (code "202") (name "DAEX2-5") (class "Default")
      (node (ref "A27") (pin "E2") (pinfunction "P$2_E2") (pintype "bidirectional"))
      (node (ref "C15") (pin "T2") (pinfunction "T_T2") (pintype "input"))
    )
    (net (code "203") (name "DAEX2-6") (class "Default")
      (node (ref "A32") (pin "E2") (pinfunction "P$2_E2") (pintype "bidirectional"))
      (node (ref "C15") (pin "V2") (pinfunction "V_V2") (pintype "input"))
    )
    (net (code "204") (name "DAEX3") (class "Default")
      (node (ref "A11") (pin "H2") (pinfunction "P$2_H2") (pintype "bidirectional"))
      (node (ref "B15") (pin "T2") (pinfunction "O$1_T2") (pintype "open_collector"))
    )
    (net (code "205") (name "DAEX3-0") (class "Default")
      (node (ref "C14") (pin "F2") (pinfunction "F_F2") (pintype "input"))
      (node (ref "D11") (pin "H2") (pinfunction "P$2_H2") (pintype "bidirectional"))
    )
    (net (code "206") (name "DAEX3-1") (class "Default")
      (node (ref "C14") (pin "J2") (pinfunction "J_J2") (pintype "input"))
      (node (ref "D16") (pin "H2") (pinfunction "P$2_H2") (pintype "bidirectional"))
    )
    (net (code "207") (name "DAEX3-2") (class "Default")
      (node (ref "C14") (pin "L2") (pinfunction "L_L2") (pintype "input"))
      (node (ref "D21") (pin "H2") (pinfunction "P$2_H2") (pintype "bidirectional"))
    )
    (net (code "208") (name "DAEX3-3") (class "Default")
      (node (ref "C14") (pin "N2") (pinfunction "N_N2") (pintype "input"))
      (node (ref "D26") (pin "H2") (pinfunction "P$2_H2") (pintype "bidirectional"))
    )
    (net (code "209") (name "DAEX3-4") (class "Default")
      (node (ref "C14") (pin "R2") (pinfunction "R_R2") (pintype "input"))
      (node (ref "D31") (pin "H2") (pinfunction "P$2_H2") (pintype "bidirectional"))
    )
    (net (code "210") (name "DAEX3-5") (class "Default")
      (node (ref "A27") (pin "H2") (pinfunction "P$2_H2") (pintype "bidirectional"))
      (node (ref "C14") (pin "T2") (pinfunction "T_T2") (pintype "input"))
    )
    (net (code "211") (name "DAEX3-6") (class "Default")
      (node (ref "A32") (pin "H2") (pinfunction "P$2_H2") (pintype "bidirectional"))
      (node (ref "C14") (pin "V2") (pinfunction "V_V2") (pintype "input"))
    )
    (net (code "212") (name "DATA_OUT") (class "Default")
      (node (ref "A08") (pin "M2") (pinfunction "P$2_M2") (pintype "bidirectional"))
      (node (ref "B32") (pin "R2") (pinfunction "O$1_R2") (pintype "open_collector"))
    )
    (net (code "213") (name "DATA_OUT0") (class "Default")
      (node (ref "C30") (pin "F2") (pinfunction "F_F2") (pintype "input"))
      (node (ref "D08") (pin "M2") (pinfunction "P$2_M2") (pintype "bidirectional"))
    )
    (net (code "214") (name "DATA_OUT1") (class "Default")
      (node (ref "C30") (pin "J2") (pinfunction "J_J2") (pintype "input"))
      (node (ref "D13") (pin "M2") (pinfunction "P$2_M2") (pintype "bidirectional"))
    )
    (net (code "215") (name "DATA_OUT2") (class "Default")
      (node (ref "C30") (pin "L2") (pinfunction "L_L2") (pintype "input"))
      (node (ref "D18") (pin "M2") (pinfunction "P$2_M2") (pintype "bidirectional"))
    )
    (net (code "216") (name "DATA_OUT3") (class "Default")
      (node (ref "C30") (pin "N2") (pinfunction "N_N2") (pintype "input"))
      (node (ref "D23") (pin "M2") (pinfunction "P$2_M2") (pintype "bidirectional"))
    )
    (net (code "217") (name "DATA_OUT4") (class "Default")
      (node (ref "C30") (pin "R2") (pinfunction "R_R2") (pintype "input"))
      (node (ref "D28") (pin "M2") (pinfunction "P$2_M2") (pintype "bidirectional"))
    )
    (net (code "218") (name "DATA_OUT5") (class "Default")
      (node (ref "A24") (pin "M2") (pinfunction "P$2_M2") (pintype "bidirectional"))
      (node (ref "C30") (pin "T2") (pinfunction "T_T2") (pintype "input"))
    )
    (net (code "219") (name "DATA_OUT6") (class "Default")
      (node (ref "A29") (pin "M2") (pinfunction "P$2_M2") (pintype "bidirectional"))
      (node (ref "C30") (pin "V2") (pinfunction "V_V2") (pintype "input"))
    )
    (net (code "220") (name "DA_SEL_DEV0") (class "Default")
      (node (ref "A13") (pin "D2") (pinfunction "O$1_D2") (pintype "open_collector"))
      (node (ref "B05") (pin "D2") (pinfunction "O$1_D2") (pintype "open_collector"))
      (node (ref "C01") (pin "E2") (pinfunction "E_E2") (pintype "input"))
      (node (ref "C02") (pin "E2") (pinfunction "E_E2") (pintype "input"))
      (node (ref "C03") (pin "E2") (pinfunction "E_E2") (pintype "input"))
      (node (ref "C04") (pin "E2") (pinfunction "E_E2") (pintype "input"))
      (node (ref "C05") (pin "E2") (pinfunction "E_E2") (pintype "input"))
      (node (ref "C06") (pin "E2") (pinfunction "E_E2") (pintype "input"))
      (node (ref "C07") (pin "E2") (pinfunction "E_E2") (pintype "input"))
      (node (ref "C08") (pin "E2") (pinfunction "E_E2") (pintype "input"))
      (node (ref "C09") (pin "E2") (pinfunction "E_E2") (pintype "input"))
      (node (ref "C10") (pin "E2") (pinfunction "E_E2") (pintype "input"))
      (node (ref "C11") (pin "E2") (pinfunction "E_E2") (pintype "input"))
      (node (ref "C12") (pin "E2") (pinfunction "E_E2") (pintype "input"))
      (node (ref "C13") (pin "E2") (pinfunction "E_E2") (pintype "input"))
      (node (ref "C14") (pin "E2") (pinfunction "E_E2") (pintype "input"))
      (node (ref "C15") (pin "E2") (pinfunction "E_E2") (pintype "input"))
      (node (ref "C16") (pin "E2") (pinfunction "E_E2") (pintype "input"))
    )
    (net (code "221") (name "DA_SEL_DEV1") (class "Default")
      (node (ref "A13") (pin "F2") (pinfunction "O$1_F2") (pintype "open_collector"))
      (node (ref "B05") (pin "F2") (pinfunction "O$1_F2") (pintype "open_collector"))
      (node (ref "C01") (pin "H2") (pinfunction "H_H2") (pintype "input"))
      (node (ref "C02") (pin "H2") (pinfunction "H_H2") (pintype "input"))
      (node (ref "C03") (pin "H2") (pinfunction "H_H2") (pintype "input"))
      (node (ref "C04") (pin "H2") (pinfunction "H_H2") (pintype "input"))
      (node (ref "C05") (pin "H2") (pinfunction "H_H2") (pintype "input"))
      (node (ref "C06") (pin "H2") (pinfunction "H_H2") (pintype "input"))
      (node (ref "C07") (pin "H2") (pinfunction "H_H2") (pintype "input"))
      (node (ref "C08") (pin "H2") (pinfunction "H_H2") (pintype "input"))
      (node (ref "C09") (pin "H2") (pinfunction "H_H2") (pintype "input"))
      (node (ref "C10") (pin "H2") (pinfunction "H_H2") (pintype "input"))
      (node (ref "C11") (pin "H2") (pinfunction "H_H2") (pintype "input"))
      (node (ref "C12") (pin "H2") (pinfunction "H_H2") (pintype "input"))
      (node (ref "C13") (pin "H2") (pinfunction "H_H2") (pintype "input"))
      (node (ref "C14") (pin "H2") (pinfunction "H_H2") (pintype "input"))
      (node (ref "C15") (pin "H2") (pinfunction "H_H2") (pintype "input"))
      (node (ref "C16") (pin "H2") (pinfunction "H_H2") (pintype "input"))
    )
    (net (code "222") (name "DA_SEL_DEV2") (class "Default")
      (node (ref "A13") (pin "J2") (pinfunction "O$1_J2") (pintype "open_collector"))
      (node (ref "B05") (pin "J2") (pinfunction "O$1_J2") (pintype "open_collector"))
      (node (ref "C01") (pin "K2") (pinfunction "K_K2") (pintype "input"))
      (node (ref "C02") (pin "K2") (pinfunction "K_K2") (pintype "input"))
      (node (ref "C03") (pin "K2") (pinfunction "K_K2") (pintype "input"))
      (node (ref "C04") (pin "K2") (pinfunction "K_K2") (pintype "input"))
      (node (ref "C05") (pin "K2") (pinfunction "K_K2") (pintype "input"))
      (node (ref "C06") (pin "K2") (pinfunction "K_K2") (pintype "input"))
      (node (ref "C07") (pin "K2") (pinfunction "K_K2") (pintype "input"))
      (node (ref "C08") (pin "K2") (pinfunction "K_K2") (pintype "input"))
      (node (ref "C09") (pin "K2") (pinfunction "K_K2") (pintype "input"))
      (node (ref "C10") (pin "K2") (pinfunction "K_K2") (pintype "input"))
      (node (ref "C11") (pin "K2") (pinfunction "K_K2") (pintype "input"))
      (node (ref "C12") (pin "K2") (pinfunction "K_K2") (pintype "input"))
      (node (ref "C13") (pin "K2") (pinfunction "K_K2") (pintype "input"))
      (node (ref "C14") (pin "K2") (pinfunction "K_K2") (pintype "input"))
      (node (ref "C15") (pin "K2") (pinfunction "K_K2") (pintype "input"))
      (node (ref "C16") (pin "K2") (pinfunction "K_K2") (pintype "input"))
    )
    (net (code "223") (name "DA_SEL_DEV3") (class "Default")
      (node (ref "A13") (pin "L2") (pinfunction "O$1_L2") (pintype "open_collector"))
      (node (ref "B05") (pin "L2") (pinfunction "O$1_L2") (pintype "open_collector"))
      (node (ref "C01") (pin "M2") (pinfunction "M_M2") (pintype "input"))
      (node (ref "C02") (pin "M2") (pinfunction "M_M2") (pintype "input"))
      (node (ref "C03") (pin "M2") (pinfunction "M_M2") (pintype "input"))
      (node (ref "C04") (pin "M2") (pinfunction "M_M2") (pintype "input"))
      (node (ref "C05") (pin "M2") (pinfunction "M_M2") (pintype "input"))
      (node (ref "C06") (pin "M2") (pinfunction "M_M2") (pintype "input"))
      (node (ref "C07") (pin "M2") (pinfunction "M_M2") (pintype "input"))
      (node (ref "C08") (pin "M2") (pinfunction "M_M2") (pintype "input"))
      (node (ref "C09") (pin "M2") (pinfunction "M_M2") (pintype "input"))
      (node (ref "C10") (pin "M2") (pinfunction "M_M2") (pintype "input"))
      (node (ref "C11") (pin "M2") (pinfunction "M_M2") (pintype "input"))
      (node (ref "C12") (pin "M2") (pinfunction "M_M2") (pintype "input"))
      (node (ref "C13") (pin "M2") (pinfunction "M_M2") (pintype "input"))
      (node (ref "C14") (pin "M2") (pinfunction "M_M2") (pintype "input"))
      (node (ref "C15") (pin "M2") (pinfunction "M_M2") (pintype "input"))
      (node (ref "C16") (pin "M2") (pinfunction "M_M2") (pintype "input"))
    )
    (net (code "224") (name "DA_SEL_DEV4") (class "Default")
      (node (ref "A13") (pin "N2") (pinfunction "O$1_N2") (pintype "open_collector"))
      (node (ref "B05") (pin "N2") (pinfunction "O$1_N2") (pintype "open_collector"))
      (node (ref "C01") (pin "P2") (pinfunction "P_P2") (pintype "input"))
      (node (ref "C02") (pin "P2") (pinfunction "P_P2") (pintype "input"))
      (node (ref "C03") (pin "P2") (pinfunction "P_P2") (pintype "input"))
      (node (ref "C04") (pin "P2") (pinfunction "P_P2") (pintype "input"))
      (node (ref "C05") (pin "P2") (pinfunction "P_P2") (pintype "input"))
      (node (ref "C06") (pin "P2") (pinfunction "P_P2") (pintype "input"))
      (node (ref "C07") (pin "P2") (pinfunction "P_P2") (pintype "input"))
      (node (ref "C08") (pin "P2") (pinfunction "P_P2") (pintype "input"))
      (node (ref "C09") (pin "P2") (pinfunction "P_P2") (pintype "input"))
      (node (ref "C10") (pin "P2") (pinfunction "P_P2") (pintype "input"))
      (node (ref "C11") (pin "P2") (pinfunction "P_P2") (pintype "input"))
      (node (ref "C12") (pin "P2") (pinfunction "P_P2") (pintype "input"))
      (node (ref "C13") (pin "P2") (pinfunction "P_P2") (pintype "input"))
      (node (ref "C14") (pin "P2") (pinfunction "P_P2") (pintype "input"))
      (node (ref "C15") (pin "P2") (pinfunction "P_P2") (pintype "input"))
      (node (ref "C16") (pin "P2") (pinfunction "P_P2") (pintype "input"))
    )
    (net (code "225") (name "DA_SEL_DEV5") (class "Default")
      (node (ref "A13") (pin "R2") (pinfunction "O$1_R2") (pintype "open_collector"))
      (node (ref "B05") (pin "R2") (pinfunction "O$1_R2") (pintype "open_collector"))
      (node (ref "C01") (pin "S2") (pinfunction "S_S2") (pintype "input"))
      (node (ref "C02") (pin "S2") (pinfunction "S_S2") (pintype "input"))
      (node (ref "C03") (pin "S2") (pinfunction "S_S2") (pintype "input"))
      (node (ref "C04") (pin "S2") (pinfunction "S_S2") (pintype "input"))
      (node (ref "C05") (pin "S2") (pinfunction "S_S2") (pintype "input"))
      (node (ref "C06") (pin "S2") (pinfunction "S_S2") (pintype "input"))
      (node (ref "C07") (pin "S2") (pinfunction "S_S2") (pintype "input"))
      (node (ref "C08") (pin "S2") (pinfunction "S_S2") (pintype "input"))
      (node (ref "C09") (pin "S2") (pinfunction "S_S2") (pintype "input"))
      (node (ref "C10") (pin "S2") (pinfunction "S_S2") (pintype "input"))
      (node (ref "C11") (pin "S2") (pinfunction "S_S2") (pintype "input"))
      (node (ref "C12") (pin "S2") (pinfunction "S_S2") (pintype "input"))
      (node (ref "C13") (pin "S2") (pinfunction "S_S2") (pintype "input"))
      (node (ref "C14") (pin "S2") (pinfunction "S_S2") (pintype "input"))
      (node (ref "C15") (pin "S2") (pinfunction "S_S2") (pintype "input"))
      (node (ref "C16") (pin "S2") (pinfunction "S_S2") (pintype "input"))
    )
    (net (code "226") (name "DA_SEL_DEV6") (class "Default")
      (node (ref "A13") (pin "T2") (pinfunction "O$1_T2") (pintype "open_collector"))
      (node (ref "B05") (pin "T2") (pinfunction "O$1_T2") (pintype "open_collector"))
      (node (ref "C01") (pin "U2") (pinfunction "U_U2") (pintype "input"))
      (node (ref "C02") (pin "U2") (pinfunction "U_U2") (pintype "input"))
      (node (ref "C03") (pin "U2") (pinfunction "U_U2") (pintype "input"))
      (node (ref "C04") (pin "U2") (pinfunction "U_U2") (pintype "input"))
      (node (ref "C05") (pin "U2") (pinfunction "U_U2") (pintype "input"))
      (node (ref "C06") (pin "U2") (pinfunction "U_U2") (pintype "input"))
      (node (ref "C07") (pin "U2") (pinfunction "U_U2") (pintype "input"))
      (node (ref "C08") (pin "U2") (pinfunction "U_U2") (pintype "input"))
      (node (ref "C09") (pin "U2") (pinfunction "U_U2") (pintype "input"))
      (node (ref "C10") (pin "U2") (pinfunction "U_U2") (pintype "input"))
      (node (ref "C11") (pin "U2") (pinfunction "U_U2") (pintype "input"))
      (node (ref "C12") (pin "U2") (pinfunction "U_U2") (pintype "input"))
      (node (ref "C13") (pin "U2") (pinfunction "U_U2") (pintype "input"))
      (node (ref "C14") (pin "U2") (pinfunction "U_U2") (pintype "input"))
      (node (ref "C15") (pin "U2") (pinfunction "U_U2") (pintype "input"))
      (node (ref "C16") (pin "U2") (pinfunction "U_U2") (pintype "input"))
    )
    (net (code "227") (name "DB0") (class "Default")
      (node (ref "A09") (pin "D2") (pinfunction "P$2_D2") (pintype "bidirectional"))
      (node (ref "B25") (pin "J2") (pinfunction "O$1_J2") (pintype "open_collector"))
    )
    (net (code "228") (name "DB0-0") (class "Default")
      (node (ref "C17") (pin "F2") (pinfunction "F_F2") (pintype "input"))
      (node (ref "D09") (pin "D2") (pinfunction "P$2_D2") (pintype "bidirectional"))
    )
    (net (code "229") (name "DB0-1") (class "Default")
      (node (ref "C17") (pin "J2") (pinfunction "J_J2") (pintype "input"))
      (node (ref "D14") (pin "D2") (pinfunction "P$2_D2") (pintype "bidirectional"))
    )
    (net (code "230") (name "DB0-2") (class "Default")
      (node (ref "C17") (pin "L2") (pinfunction "L_L2") (pintype "input"))
      (node (ref "D19") (pin "D2") (pinfunction "P$2_D2") (pintype "bidirectional"))
    )
    (net (code "231") (name "DB0-3") (class "Default")
      (node (ref "C17") (pin "N2") (pinfunction "N_N2") (pintype "input"))
      (node (ref "D24") (pin "D2") (pinfunction "P$2_D2") (pintype "bidirectional"))
    )
    (net (code "232") (name "DB0-4") (class "Default")
      (node (ref "C17") (pin "R2") (pinfunction "R_R2") (pintype "input"))
      (node (ref "D29") (pin "D2") (pinfunction "P$2_D2") (pintype "bidirectional"))
    )
    (net (code "233") (name "DB0-5") (class "Default")
      (node (ref "A25") (pin "D2") (pinfunction "P$2_D2") (pintype "bidirectional"))
      (node (ref "C17") (pin "T2") (pinfunction "T_T2") (pintype "input"))
    )
    (net (code "234") (name "DB0-6") (class "Default")
      (node (ref "A30") (pin "D2") (pinfunction "P$2_D2") (pintype "bidirectional"))
      (node (ref "C17") (pin "V2") (pinfunction "V_V2") (pintype "input"))
    )
    (net (code "235") (name "DB1") (class "Default")
      (node (ref "A09") (pin "E2") (pinfunction "P$2_E2") (pintype "bidirectional"))
      (node (ref "B25") (pin "L2") (pinfunction "O$1_L2") (pintype "open_collector"))
    )
    (net (code "236") (name "DB1-0") (class "Default")
      (node (ref "C18") (pin "F2") (pinfunction "F_F2") (pintype "input"))
      (node (ref "D09") (pin "E2") (pinfunction "P$2_E2") (pintype "bidirectional"))
    )
    (net (code "237") (name "DB1-1") (class "Default")
      (node (ref "C18") (pin "J2") (pinfunction "J_J2") (pintype "input"))
      (node (ref "D14") (pin "E2") (pinfunction "P$2_E2") (pintype "bidirectional"))
    )
    (net (code "238") (name "DB1-2") (class "Default")
      (node (ref "C18") (pin "L2") (pinfunction "L_L2") (pintype "input"))
      (node (ref "D19") (pin "E2") (pinfunction "P$2_E2") (pintype "bidirectional"))
    )
    (net (code "239") (name "DB1-3") (class "Default")
      (node (ref "C18") (pin "N2") (pinfunction "N_N2") (pintype "input"))
      (node (ref "D24") (pin "E2") (pinfunction "P$2_E2") (pintype "bidirectional"))
    )
    (net (code "240") (name "DB1-4") (class "Default")
      (node (ref "C18") (pin "R2") (pinfunction "R_R2") (pintype "input"))
      (node (ref "D29") (pin "E2") (pinfunction "P$2_E2") (pintype "bidirectional"))
    )
    (net (code "241") (name "DB1-5") (class "Default")
      (node (ref "A25") (pin "E2") (pinfunction "P$2_E2") (pintype "bidirectional"))
      (node (ref "C18") (pin "T2") (pinfunction "T_T2") (pintype "input"))
    )
    (net (code "242") (name "DB1-6") (class "Default")
      (node (ref "A30") (pin "E2") (pinfunction "P$2_E2") (pintype "bidirectional"))
      (node (ref "C18") (pin "V2") (pinfunction "V_V2") (pintype "input"))
    )
    (net (code "243") (name "DB2") (class "Default")
      (node (ref "A09") (pin "H2") (pinfunction "P$2_H2") (pintype "bidirectional"))
      (node (ref "B25") (pin "N2") (pinfunction "O$1_N2") (pintype "open_collector"))
    )
    (net (code "244") (name "DB2-0") (class "Default")
      (node (ref "C19") (pin "F2") (pinfunction "F_F2") (pintype "input"))
      (node (ref "D09") (pin "H2") (pinfunction "P$2_H2") (pintype "bidirectional"))
    )
    (net (code "245") (name "DB2-1") (class "Default")
      (node (ref "C19") (pin "J2") (pinfunction "J_J2") (pintype "input"))
      (node (ref "D14") (pin "H2") (pinfunction "P$2_H2") (pintype "bidirectional"))
    )
    (net (code "246") (name "DB2-2") (class "Default")
      (node (ref "C19") (pin "L2") (pinfunction "L_L2") (pintype "input"))
      (node (ref "D19") (pin "H2") (pinfunction "P$2_H2") (pintype "bidirectional"))
    )
    (net (code "247") (name "DB2-3") (class "Default")
      (node (ref "C19") (pin "N2") (pinfunction "N_N2") (pintype "input"))
      (node (ref "D24") (pin "H2") (pinfunction "P$2_H2") (pintype "bidirectional"))
    )
    (net (code "248") (name "DB2-4") (class "Default")
      (node (ref "C19") (pin "R2") (pinfunction "R_R2") (pintype "input"))
      (node (ref "D29") (pin "H2") (pinfunction "P$2_H2") (pintype "bidirectional"))
    )
    (net (code "249") (name "DB2-5") (class "Default")
      (node (ref "A25") (pin "H2") (pinfunction "P$2_H2") (pintype "bidirectional"))
      (node (ref "C19") (pin "T2") (pinfunction "T_T2") (pintype "input"))
    )
    (net (code "250") (name "DB2-6") (class "Default")
      (node (ref "A30") (pin "H2") (pinfunction "P$2_H2") (pintype "bidirectional"))
      (node (ref "C19") (pin "V2") (pinfunction "V_V2") (pintype "input"))
    )
    (net (code "251") (name "DB3") (class "Default")
      (node (ref "A09") (pin "K2") (pinfunction "P$2_K2") (pintype "bidirectional"))
      (node (ref "B25") (pin "R2") (pinfunction "O$1_R2") (pintype "open_collector"))
    )
    (net (code "252") (name "DB3-0") (class "Default")
      (node (ref "C20") (pin "F2") (pinfunction "F_F2") (pintype "input"))
      (node (ref "D09") (pin "K2") (pinfunction "P$2_K2") (pintype "bidirectional"))
    )
    (net (code "253") (name "DB3-1") (class "Default")
      (node (ref "C20") (pin "J2") (pinfunction "J_J2") (pintype "input"))
      (node (ref "D14") (pin "K2") (pinfunction "P$2_K2") (pintype "bidirectional"))
    )
    (net (code "254") (name "DB3-2") (class "Default")
      (node (ref "C20") (pin "L2") (pinfunction "L_L2") (pintype "input"))
      (node (ref "D19") (pin "K2") (pinfunction "P$2_K2") (pintype "bidirectional"))
    )
    (net (code "255") (name "DB3-3") (class "Default")
      (node (ref "C20") (pin "N2") (pinfunction "N_N2") (pintype "input"))
      (node (ref "D24") (pin "K2") (pinfunction "P$2_K2") (pintype "bidirectional"))
    )
    (net (code "256") (name "DB3-4") (class "Default")
      (node (ref "C20") (pin "R2") (pinfunction "R_R2") (pintype "input"))
      (node (ref "D29") (pin "K2") (pinfunction "P$2_K2") (pintype "bidirectional"))
    )
    (net (code "257") (name "DB3-5") (class "Default")
      (node (ref "A25") (pin "K2") (pinfunction "P$2_K2") (pintype "bidirectional"))
      (node (ref "C20") (pin "T2") (pinfunction "T_T2") (pintype "input"))
    )
    (net (code "258") (name "DB3-6") (class "Default")
      (node (ref "A30") (pin "K2") (pinfunction "P$2_K2") (pintype "bidirectional"))
      (node (ref "C20") (pin "V2") (pinfunction "V_V2") (pintype "input"))
    )
    (net (code "259") (name "DB4") (class "Default")
      (node (ref "A09") (pin "M2") (pinfunction "P$2_M2") (pintype "bidirectional"))
      (node (ref "B25") (pin "T2") (pinfunction "O$1_T2") (pintype "open_collector"))
    )
    (net (code "260") (name "DB4-0") (class "Default")
      (node (ref "C21") (pin "F2") (pinfunction "F_F2") (pintype "input"))
      (node (ref "D09") (pin "M2") (pinfunction "P$2_M2") (pintype "bidirectional"))
    )
    (net (code "261") (name "DB4-1") (class "Default")
      (node (ref "C21") (pin "J2") (pinfunction "J_J2") (pintype "input"))
      (node (ref "D14") (pin "M2") (pinfunction "P$2_M2") (pintype "bidirectional"))
    )
    (net (code "262") (name "DB4-2") (class "Default")
      (node (ref "C21") (pin "L2") (pinfunction "L_L2") (pintype "input"))
      (node (ref "D19") (pin "M2") (pinfunction "P$2_M2") (pintype "bidirectional"))
    )
    (net (code "263") (name "DB4-3") (class "Default")
      (node (ref "C21") (pin "N2") (pinfunction "N_N2") (pintype "input"))
      (node (ref "D24") (pin "M2") (pinfunction "P$2_M2") (pintype "bidirectional"))
    )
    (net (code "264") (name "DB4-4") (class "Default")
      (node (ref "C21") (pin "R2") (pinfunction "R_R2") (pintype "input"))
      (node (ref "D29") (pin "M2") (pinfunction "P$2_M2") (pintype "bidirectional"))
    )
    (net (code "265") (name "DB4-5") (class "Default")
      (node (ref "A25") (pin "M2") (pinfunction "P$2_M2") (pintype "bidirectional"))
      (node (ref "C21") (pin "T2") (pinfunction "T_T2") (pintype "input"))
    )
    (net (code "266") (name "DB4-6") (class "Default")
      (node (ref "A30") (pin "M2") (pinfunction "P$2_M2") (pintype "bidirectional"))
      (node (ref "C21") (pin "V2") (pinfunction "V_V2") (pintype "input"))
    )
    (net (code "267") (name "DB5") (class "Default")
      (node (ref "A09") (pin "P2") (pinfunction "P$2_P2") (pintype "bidirectional"))
      (node (ref "B26") (pin "D2") (pinfunction "O$1_D2") (pintype "open_collector"))
    )
    (net (code "268") (name "DB5-0") (class "Default")
      (node (ref "C22") (pin "F2") (pinfunction "F_F2") (pintype "input"))
      (node (ref "D09") (pin "P2") (pinfunction "P$2_P2") (pintype "bidirectional"))
    )
    (net (code "269") (name "DB5-1") (class "Default")
      (node (ref "C22") (pin "J2") (pinfunction "J_J2") (pintype "input"))
      (node (ref "D14") (pin "P2") (pinfunction "P$2_P2") (pintype "bidirectional"))
    )
    (net (code "270") (name "DB5-2") (class "Default")
      (node (ref "C22") (pin "L2") (pinfunction "L_L2") (pintype "input"))
      (node (ref "D19") (pin "P2") (pinfunction "P$2_P2") (pintype "bidirectional"))
    )
    (net (code "271") (name "DB5-3") (class "Default")
      (node (ref "C22") (pin "N2") (pinfunction "N_N2") (pintype "input"))
      (node (ref "D24") (pin "P2") (pinfunction "P$2_P2") (pintype "bidirectional"))
    )
    (net (code "272") (name "DB5-4") (class "Default")
      (node (ref "C22") (pin "R2") (pinfunction "R_R2") (pintype "input"))
      (node (ref "D29") (pin "P2") (pinfunction "P$2_P2") (pintype "bidirectional"))
    )
    (net (code "273") (name "DB5-5") (class "Default")
      (node (ref "A25") (pin "P2") (pinfunction "P$2_P2") (pintype "bidirectional"))
      (node (ref "C22") (pin "T2") (pinfunction "T_T2") (pintype "input"))
    )
    (net (code "274") (name "DB5-6") (class "Default")
      (node (ref "A30") (pin "P2") (pinfunction "P$2_P2") (pintype "bidirectional"))
      (node (ref "C22") (pin "V2") (pinfunction "V_V2") (pintype "input"))
    )
    (net (code "275") (name "DB6") (class "Default")
      (node (ref "A09") (pin "S2") (pinfunction "P$2_S2") (pintype "bidirectional"))
      (node (ref "B26") (pin "F2") (pinfunction "O$1_F2") (pintype "open_collector"))
    )
    (net (code "276") (name "DB6-0") (class "Default")
      (node (ref "C23") (pin "F2") (pinfunction "F_F2") (pintype "input"))
      (node (ref "D09") (pin "S2") (pinfunction "P$2_S2") (pintype "bidirectional"))
    )
    (net (code "277") (name "DB6-1") (class "Default")
      (node (ref "C23") (pin "J2") (pinfunction "J_J2") (pintype "input"))
      (node (ref "D14") (pin "S2") (pinfunction "P$2_S2") (pintype "bidirectional"))
    )
    (net (code "278") (name "DB6-2") (class "Default")
      (node (ref "C23") (pin "L2") (pinfunction "L_L2") (pintype "input"))
      (node (ref "D19") (pin "S2") (pinfunction "P$2_S2") (pintype "bidirectional"))
    )
    (net (code "279") (name "DB6-3") (class "Default")
      (node (ref "C23") (pin "N2") (pinfunction "N_N2") (pintype "input"))
      (node (ref "D24") (pin "S2") (pinfunction "P$2_S2") (pintype "bidirectional"))
    )
    (net (code "280") (name "DB6-4") (class "Default")
      (node (ref "C23") (pin "R2") (pinfunction "R_R2") (pintype "input"))
      (node (ref "D29") (pin "S2") (pinfunction "P$2_S2") (pintype "bidirectional"))
    )
    (net (code "281") (name "DB6-5") (class "Default")
      (node (ref "A25") (pin "S2") (pinfunction "P$2_S2") (pintype "bidirectional"))
      (node (ref "C23") (pin "T2") (pinfunction "T_T2") (pintype "input"))
    )
    (net (code "282") (name "DB6-6") (class "Default")
      (node (ref "A30") (pin "S2") (pinfunction "P$2_S2") (pintype "bidirectional"))
      (node (ref "C23") (pin "V2") (pinfunction "V_V2") (pintype "input"))
    )
    (net (code "283") (name "DB7") (class "Default")
      (node (ref "A09") (pin "T2") (pinfunction "P$2_T2") (pintype "bidirectional"))
      (node (ref "B26") (pin "J2") (pinfunction "O$1_J2") (pintype "open_collector"))
    )
    (net (code "284") (name "DB7-0") (class "Default")
      (node (ref "C24") (pin "F2") (pinfunction "F_F2") (pintype "input"))
      (node (ref "D09") (pin "T2") (pinfunction "P$2_T2") (pintype "bidirectional"))
    )
    (net (code "285") (name "DB7-1") (class "Default")
      (node (ref "C24") (pin "J2") (pinfunction "J_J2") (pintype "input"))
      (node (ref "D14") (pin "T2") (pinfunction "P$2_T2") (pintype "bidirectional"))
    )
    (net (code "286") (name "DB7-2") (class "Default")
      (node (ref "C24") (pin "L2") (pinfunction "L_L2") (pintype "input"))
      (node (ref "D19") (pin "T2") (pinfunction "P$2_T2") (pintype "bidirectional"))
    )
    (net (code "287") (name "DB7-3") (class "Default")
      (node (ref "C24") (pin "N2") (pinfunction "N_N2") (pintype "input"))
      (node (ref "D24") (pin "T2") (pinfunction "P$2_T2") (pintype "bidirectional"))
    )
    (net (code "288") (name "DB7-4") (class "Default")
      (node (ref "C24") (pin "R2") (pinfunction "R_R2") (pintype "input"))
      (node (ref "D29") (pin "T2") (pinfunction "P$2_T2") (pintype "bidirectional"))
    )
    (net (code "289") (name "DB7-5") (class "Default")
      (node (ref "A25") (pin "T2") (pinfunction "P$2_T2") (pintype "bidirectional"))
      (node (ref "C24") (pin "T2") (pinfunction "T_T2") (pintype "input"))
    )
    (net (code "290") (name "DB7-6") (class "Default")
      (node (ref "A30") (pin "T2") (pinfunction "P$2_T2") (pintype "bidirectional"))
      (node (ref "C24") (pin "V2") (pinfunction "V_V2") (pintype "input"))
    )
    (net (code "291") (name "DB8") (class "Default")
      (node (ref "A09") (pin "V2") (pinfunction "P$2_V2") (pintype "bidirectional"))
      (node (ref "B26") (pin "L2") (pinfunction "O$1_L2") (pintype "open_collector"))
    )
    (net (code "292") (name "DB8-0") (class "Default")
      (node (ref "C25") (pin "F2") (pinfunction "F_F2") (pintype "input"))
      (node (ref "D09") (pin "V2") (pinfunction "P$2_V2") (pintype "bidirectional"))
    )
    (net (code "293") (name "DB8-1") (class "Default")
      (node (ref "C25") (pin "J2") (pinfunction "J_J2") (pintype "input"))
      (node (ref "D14") (pin "V2") (pinfunction "P$2_V2") (pintype "bidirectional"))
    )
    (net (code "294") (name "DB8-2") (class "Default")
      (node (ref "C25") (pin "L2") (pinfunction "L_L2") (pintype "input"))
      (node (ref "D19") (pin "V2") (pinfunction "P$2_V2") (pintype "bidirectional"))
    )
    (net (code "295") (name "DB8-3") (class "Default")
      (node (ref "C25") (pin "N2") (pinfunction "N_N2") (pintype "input"))
      (node (ref "D24") (pin "V2") (pinfunction "P$2_V2") (pintype "bidirectional"))
    )
    (net (code "296") (name "DB8-4") (class "Default")
      (node (ref "C25") (pin "R2") (pinfunction "R_R2") (pintype "input"))
      (node (ref "D29") (pin "V2") (pinfunction "P$2_V2") (pintype "bidirectional"))
    )
    (net (code "297") (name "DB8-5") (class "Default")
      (node (ref "A25") (pin "V2") (pinfunction "P$2_V2") (pintype "bidirectional"))
      (node (ref "C25") (pin "T2") (pinfunction "T_T2") (pintype "input"))
    )
    (net (code "298") (name "DB8-6") (class "Default")
      (node (ref "A30") (pin "V2") (pinfunction "P$2_V2") (pintype "bidirectional"))
      (node (ref "C25") (pin "V2") (pinfunction "V_V2") (pintype "input"))
    )
    (net (code "299") (name "DB9") (class "Default")
      (node (ref "A10") (pin "D2") (pinfunction "P$2_D2") (pintype "bidirectional"))
      (node (ref "B26") (pin "N2") (pinfunction "O$1_N2") (pintype "open_collector"))
    )
    (net (code "300") (name "DB9-0") (class "Default")
      (node (ref "C26") (pin "F2") (pinfunction "F_F2") (pintype "input"))
      (node (ref "D10") (pin "D2") (pinfunction "P$2_D2") (pintype "bidirectional"))
    )
    (net (code "301") (name "DB9-1") (class "Default")
      (node (ref "C26") (pin "J2") (pinfunction "J_J2") (pintype "input"))
      (node (ref "D15") (pin "D2") (pinfunction "P$2_D2") (pintype "bidirectional"))
    )
    (net (code "302") (name "DB9-2") (class "Default")
      (node (ref "C26") (pin "L2") (pinfunction "L_L2") (pintype "input"))
      (node (ref "D20") (pin "D2") (pinfunction "P$2_D2") (pintype "bidirectional"))
    )
    (net (code "303") (name "DB9-3") (class "Default")
      (node (ref "C26") (pin "N2") (pinfunction "N_N2") (pintype "input"))
      (node (ref "D25") (pin "D2") (pinfunction "P$2_D2") (pintype "bidirectional"))
    )
    (net (code "304") (name "DB9-4") (class "Default")
      (node (ref "C26") (pin "R2") (pinfunction "R_R2") (pintype "input"))
      (node (ref "D30") (pin "D2") (pinfunction "P$2_D2") (pintype "bidirectional"))
    )
    (net (code "305") (name "DB9-5") (class "Default")
      (node (ref "A26") (pin "D2") (pinfunction "P$2_D2") (pintype "bidirectional"))
      (node (ref "C26") (pin "T2") (pinfunction "T_T2") (pintype "input"))
    )
    (net (code "306") (name "DB9-6") (class "Default")
      (node (ref "A31") (pin "D2") (pinfunction "P$2_D2") (pintype "bidirectional"))
      (node (ref "C26") (pin "V2") (pinfunction "V_V2") (pintype "input"))
    )
    (net (code "307") (name "DB10") (class "Default")
      (node (ref "A10") (pin "E2") (pinfunction "P$2_E2") (pintype "bidirectional"))
      (node (ref "B26") (pin "R2") (pinfunction "O$1_R2") (pintype "open_collector"))
    )
    (net (code "308") (name "DB10-0") (class "Default")
      (node (ref "C27") (pin "F2") (pinfunction "F_F2") (pintype "input"))
      (node (ref "D10") (pin "E2") (pinfunction "P$2_E2") (pintype "bidirectional"))
    )
    (net (code "309") (name "DB10-1") (class "Default")
      (node (ref "C27") (pin "J2") (pinfunction "J_J2") (pintype "input"))
      (node (ref "D15") (pin "E2") (pinfunction "P$2_E2") (pintype "bidirectional"))
    )
    (net (code "310") (name "DB10-2") (class "Default")
      (node (ref "C27") (pin "L2") (pinfunction "L_L2") (pintype "input"))
      (node (ref "D20") (pin "E2") (pinfunction "P$2_E2") (pintype "bidirectional"))
    )
    (net (code "311") (name "DB10-3") (class "Default")
      (node (ref "C27") (pin "N2") (pinfunction "N_N2") (pintype "input"))
      (node (ref "D25") (pin "E2") (pinfunction "P$2_E2") (pintype "bidirectional"))
    )
    (net (code "312") (name "DB10-4") (class "Default")
      (node (ref "C27") (pin "R2") (pinfunction "R_R2") (pintype "input"))
      (node (ref "D30") (pin "E2") (pinfunction "P$2_E2") (pintype "bidirectional"))
    )
    (net (code "313") (name "DB10-5") (class "Default")
      (node (ref "A26") (pin "E2") (pinfunction "P$2_E2") (pintype "bidirectional"))
      (node (ref "C27") (pin "T2") (pinfunction "T_T2") (pintype "input"))
    )
    (net (code "314") (name "DB10-6") (class "Default")
      (node (ref "A31") (pin "E2") (pinfunction "P$2_E2") (pintype "bidirectional"))
      (node (ref "C27") (pin "V2") (pinfunction "V_V2") (pintype "input"))
    )
    (net (code "315") (name "DB11") (class "Default")
      (node (ref "A10") (pin "H2") (pinfunction "P$2_H2") (pintype "bidirectional"))
      (node (ref "B26") (pin "T2") (pinfunction "O$1_T2") (pintype "open_collector"))
    )
    (net (code "316") (name "DB11-0") (class "Default")
      (node (ref "C28") (pin "F2") (pinfunction "F_F2") (pintype "input"))
      (node (ref "D10") (pin "H2") (pinfunction "P$2_H2") (pintype "bidirectional"))
    )
    (net (code "317") (name "DB11-1") (class "Default")
      (node (ref "C28") (pin "J2") (pinfunction "J_J2") (pintype "input"))
      (node (ref "D15") (pin "H2") (pinfunction "P$2_H2") (pintype "bidirectional"))
    )
    (net (code "318") (name "DB11-2") (class "Default")
      (node (ref "C28") (pin "L2") (pinfunction "L_L2") (pintype "input"))
      (node (ref "D20") (pin "H2") (pinfunction "P$2_H2") (pintype "bidirectional"))
    )
    (net (code "319") (name "DB11-3") (class "Default")
      (node (ref "C28") (pin "N2") (pinfunction "N_N2") (pintype "input"))
      (node (ref "D25") (pin "H2") (pinfunction "P$2_H2") (pintype "bidirectional"))
    )
    (net (code "320") (name "DB11-4") (class "Default")
      (node (ref "C28") (pin "R2") (pinfunction "R_R2") (pintype "input"))
      (node (ref "D30") (pin "H2") (pinfunction "P$2_H2") (pintype "bidirectional"))
    )
    (net (code "321") (name "DB11-5") (class "Default")
      (node (ref "A26") (pin "H2") (pinfunction "P$2_H2") (pintype "bidirectional"))
      (node (ref "C28") (pin "T2") (pinfunction "T_T2") (pintype "input"))
    )
    (net (code "322") (name "DB11-6") (class "Default")
      (node (ref "A31") (pin "H2") (pinfunction "P$2_H2") (pintype "bidirectional"))
      (node (ref "C28") (pin "V2") (pinfunction "V_V2") (pintype "input"))
    )
    (net (code "323") (name "DB_SEL_DEV0") (class "Default")
      (node (ref "A12") (pin "D2") (pinfunction "O$1_D2") (pintype "open_collector"))
      (node (ref "B04") (pin "D2") (pinfunction "O$1_D2") (pintype "open_collector"))
      (node (ref "C17") (pin "E2") (pinfunction "E_E2") (pintype "input"))
      (node (ref "C18") (pin "E2") (pinfunction "E_E2") (pintype "input"))
      (node (ref "C19") (pin "E2") (pinfunction "E_E2") (pintype "input"))
      (node (ref "C20") (pin "E2") (pinfunction "E_E2") (pintype "input"))
      (node (ref "C21") (pin "E2") (pinfunction "E_E2") (pintype "input"))
      (node (ref "C22") (pin "E2") (pinfunction "E_E2") (pintype "input"))
      (node (ref "C23") (pin "E2") (pinfunction "E_E2") (pintype "input"))
      (node (ref "C24") (pin "E2") (pinfunction "E_E2") (pintype "input"))
      (node (ref "C25") (pin "E2") (pinfunction "E_E2") (pintype "input"))
      (node (ref "C26") (pin "E2") (pinfunction "E_E2") (pintype "input"))
      (node (ref "C27") (pin "E2") (pinfunction "E_E2") (pintype "input"))
      (node (ref "C28") (pin "E2") (pinfunction "E_E2") (pintype "input"))
      (node (ref "C29") (pin "E2") (pinfunction "E_E2") (pintype "input"))
      (node (ref "C30") (pin "E2") (pinfunction "E_E2") (pintype "input"))
    )
    (net (code "324") (name "DB_SEL_DEV1") (class "Default")
      (node (ref "A12") (pin "F2") (pinfunction "O$1_F2") (pintype "open_collector"))
      (node (ref "B04") (pin "F2") (pinfunction "O$1_F2") (pintype "open_collector"))
      (node (ref "C17") (pin "H2") (pinfunction "H_H2") (pintype "input"))
      (node (ref "C18") (pin "H2") (pinfunction "H_H2") (pintype "input"))
      (node (ref "C19") (pin "H2") (pinfunction "H_H2") (pintype "input"))
      (node (ref "C20") (pin "H2") (pinfunction "H_H2") (pintype "input"))
      (node (ref "C21") (pin "H2") (pinfunction "H_H2") (pintype "input"))
      (node (ref "C22") (pin "H2") (pinfunction "H_H2") (pintype "input"))
      (node (ref "C23") (pin "H2") (pinfunction "H_H2") (pintype "input"))
      (node (ref "C24") (pin "H2") (pinfunction "H_H2") (pintype "input"))
      (node (ref "C25") (pin "H2") (pinfunction "H_H2") (pintype "input"))
      (node (ref "C26") (pin "H2") (pinfunction "H_H2") (pintype "input"))
      (node (ref "C27") (pin "H2") (pinfunction "H_H2") (pintype "input"))
      (node (ref "C28") (pin "H2") (pinfunction "H_H2") (pintype "input"))
      (node (ref "C29") (pin "H2") (pinfunction "H_H2") (pintype "input"))
      (node (ref "C30") (pin "H2") (pinfunction "H_H2") (pintype "input"))
    )
    (net (code "325") (name "DB_SEL_DEV2") (class "Default")
      (node (ref "A12") (pin "J2") (pinfunction "O$1_J2") (pintype "open_collector"))
      (node (ref "B04") (pin "J2") (pinfunction "O$1_J2") (pintype "open_collector"))
      (node (ref "C17") (pin "K2") (pinfunction "K_K2") (pintype "input"))
      (node (ref "C18") (pin "K2") (pinfunction "K_K2") (pintype "input"))
      (node (ref "C19") (pin "K2") (pinfunction "K_K2") (pintype "input"))
      (node (ref "C20") (pin "K2") (pinfunction "K_K2") (pintype "input"))
      (node (ref "C21") (pin "K2") (pinfunction "K_K2") (pintype "input"))
      (node (ref "C22") (pin "K2") (pinfunction "K_K2") (pintype "input"))
      (node (ref "C23") (pin "K2") (pinfunction "K_K2") (pintype "input"))
      (node (ref "C24") (pin "K2") (pinfunction "K_K2") (pintype "input"))
      (node (ref "C25") (pin "K2") (pinfunction "K_K2") (pintype "input"))
      (node (ref "C26") (pin "K2") (pinfunction "K_K2") (pintype "input"))
      (node (ref "C27") (pin "K2") (pinfunction "K_K2") (pintype "input"))
      (node (ref "C28") (pin "K2") (pinfunction "K_K2") (pintype "input"))
      (node (ref "C29") (pin "K2") (pinfunction "K_K2") (pintype "input"))
      (node (ref "C30") (pin "K2") (pinfunction "K_K2") (pintype "input"))
    )
    (net (code "326") (name "DB_SEL_DEV3") (class "Default")
      (node (ref "A12") (pin "L2") (pinfunction "O$1_L2") (pintype "open_collector"))
      (node (ref "B04") (pin "L2") (pinfunction "O$1_L2") (pintype "open_collector"))
      (node (ref "C17") (pin "M2") (pinfunction "M_M2") (pintype "input"))
      (node (ref "C18") (pin "M2") (pinfunction "M_M2") (pintype "input"))
      (node (ref "C19") (pin "M2") (pinfunction "M_M2") (pintype "input"))
      (node (ref "C20") (pin "M2") (pinfunction "M_M2") (pintype "input"))
      (node (ref "C21") (pin "M2") (pinfunction "M_M2") (pintype "input"))
      (node (ref "C22") (pin "M2") (pinfunction "M_M2") (pintype "input"))
      (node (ref "C23") (pin "M2") (pinfunction "M_M2") (pintype "input"))
      (node (ref "C24") (pin "M2") (pinfunction "M_M2") (pintype "input"))
      (node (ref "C25") (pin "M2") (pinfunction "M_M2") (pintype "input"))
      (node (ref "C26") (pin "M2") (pinfunction "M_M2") (pintype "input"))
      (node (ref "C27") (pin "M2") (pinfunction "M_M2") (pintype "input"))
      (node (ref "C28") (pin "M2") (pinfunction "M_M2") (pintype "input"))
      (node (ref "C29") (pin "M2") (pinfunction "M_M2") (pintype "input"))
      (node (ref "C30") (pin "M2") (pinfunction "M_M2") (pintype "input"))
    )
    (net (code "327") (name "DB_SEL_DEV4") (class "Default")
      (node (ref "A12") (pin "N2") (pinfunction "O$1_N2") (pintype "open_collector"))
      (node (ref "B04") (pin "N2") (pinfunction "O$1_N2") (pintype "open_collector"))
      (node (ref "C17") (pin "P2") (pinfunction "P_P2") (pintype "input"))
      (node (ref "C18") (pin "P2") (pinfunction "P_P2") (pintype "input"))
      (node (ref "C19") (pin "P2") (pinfunction "P_P2") (pintype "input"))
      (node (ref "C20") (pin "P2") (pinfunction "P_P2") (pintype "input"))
      (node (ref "C21") (pin "P2") (pinfunction "P_P2") (pintype "input"))
      (node (ref "C22") (pin "P2") (pinfunction "P_P2") (pintype "input"))
      (node (ref "C23") (pin "P2") (pinfunction "P_P2") (pintype "input"))
      (node (ref "C24") (pin "P2") (pinfunction "P_P2") (pintype "input"))
      (node (ref "C25") (pin "P2") (pinfunction "P_P2") (pintype "input"))
      (node (ref "C26") (pin "P2") (pinfunction "P_P2") (pintype "input"))
      (node (ref "C27") (pin "P2") (pinfunction "P_P2") (pintype "input"))
      (node (ref "C28") (pin "P2") (pinfunction "P_P2") (pintype "input"))
      (node (ref "C29") (pin "P2") (pinfunction "P_P2") (pintype "input"))
      (node (ref "C30") (pin "P2") (pinfunction "P_P2") (pintype "input"))
    )
    (net (code "328") (name "DB_SEL_DEV5") (class "Default")
      (node (ref "A12") (pin "R2") (pinfunction "O$1_R2") (pintype "open_collector"))
      (node (ref "B04") (pin "R2") (pinfunction "O$1_R2") (pintype "open_collector"))
      (node (ref "C17") (pin "S2") (pinfunction "S_S2") (pintype "input"))
      (node (ref "C18") (pin "S2") (pinfunction "S_S2") (pintype "input"))
      (node (ref "C19") (pin "S2") (pinfunction "S_S2") (pintype "input"))
      (node (ref "C20") (pin "S2") (pinfunction "S_S2") (pintype "input"))
      (node (ref "C21") (pin "S2") (pinfunction "S_S2") (pintype "input"))
      (node (ref "C22") (pin "S2") (pinfunction "S_S2") (pintype "input"))
      (node (ref "C23") (pin "S2") (pinfunction "S_S2") (pintype "input"))
      (node (ref "C24") (pin "S2") (pinfunction "S_S2") (pintype "input"))
      (node (ref "C25") (pin "S2") (pinfunction "S_S2") (pintype "input"))
      (node (ref "C26") (pin "S2") (pinfunction "S_S2") (pintype "input"))
      (node (ref "C27") (pin "S2") (pinfunction "S_S2") (pintype "input"))
      (node (ref "C28") (pin "S2") (pinfunction "S_S2") (pintype "input"))
      (node (ref "C29") (pin "S2") (pinfunction "S_S2") (pintype "input"))
      (node (ref "C30") (pin "S2") (pinfunction "S_S2") (pintype "input"))
    )
    (net (code "329") (name "DB_SEL_DEV6") (class "Default")
      (node (ref "A12") (pin "T2") (pinfunction "O$1_T2") (pintype "open_collector"))
      (node (ref "B04") (pin "T2") (pinfunction "O$1_T2") (pintype "open_collector"))
      (node (ref "C17") (pin "U2") (pinfunction "U_U2") (pintype "input"))
      (node (ref "C18") (pin "U2") (pinfunction "U_U2") (pintype "input"))
      (node (ref "C19") (pin "U2") (pinfunction "U_U2") (pintype "input"))
      (node (ref "C20") (pin "U2") (pinfunction "U_U2") (pintype "input"))
      (node (ref "C21") (pin "U2") (pinfunction "U_U2") (pintype "input"))
      (node (ref "C22") (pin "U2") (pinfunction "U_U2") (pintype "input"))
      (node (ref "C23") (pin "U2") (pinfunction "U_U2") (pintype "input"))
      (node (ref "C24") (pin "U2") (pinfunction "U_U2") (pintype "input"))
      (node (ref "C25") (pin "U2") (pinfunction "U_U2") (pintype "input"))
      (node (ref "C26") (pin "U2") (pinfunction "U_U2") (pintype "input"))
      (node (ref "C27") (pin "U2") (pinfunction "U_U2") (pintype "input"))
      (node (ref "C28") (pin "U2") (pinfunction "U_U2") (pintype "input"))
      (node (ref "C29") (pin "U2") (pinfunction "U_U2") (pintype "input"))
      (node (ref "C30") (pin "U2") (pinfunction "U_U2") (pintype "input"))
    )
    (net (code "330") (name "DF0") (class "Default")
      (node (ref "A11") (pin "K2") (pinfunction "P$2_K2") (pintype "bidirectional"))
      (node (ref "A27") (pin "K2") (pinfunction "P$2_K2") (pintype "bidirectional"))
      (node (ref "A32") (pin "K2") (pinfunction "P$2_K2") (pintype "bidirectional"))
      (node (ref "D11") (pin "K2") (pinfunction "P$2_K2") (pintype "bidirectional"))
      (node (ref "D16") (pin "K2") (pinfunction "P$2_K2") (pintype "bidirectional"))
      (node (ref "D21") (pin "K2") (pinfunction "P$2_K2") (pintype "bidirectional"))
      (node (ref "D26") (pin "K2") (pinfunction "P$2_K2") (pintype "bidirectional"))
      (node (ref "D31") (pin "K2") (pinfunction "P$2_K2") (pintype "bidirectional"))
    )
    (net (code "331") (name "DF1") (class "Default")
      (node (ref "A11") (pin "M2") (pinfunction "P$2_M2") (pintype "bidirectional"))
      (node (ref "A27") (pin "M2") (pinfunction "P$2_M2") (pintype "bidirectional"))
      (node (ref "A32") (pin "M2") (pinfunction "P$2_M2") (pintype "bidirectional"))
      (node (ref "D11") (pin "M2") (pinfunction "P$2_M2") (pintype "bidirectional"))
      (node (ref "D16") (pin "M2") (pinfunction "P$2_M2") (pintype "bidirectional"))
      (node (ref "D21") (pin "M2") (pinfunction "P$2_M2") (pintype "bidirectional"))
      (node (ref "D26") (pin "M2") (pinfunction "P$2_M2") (pintype "bidirectional"))
      (node (ref "D31") (pin "M2") (pinfunction "P$2_M2") (pintype "bidirectional"))
    )
    (net (code "332") (name "DF2") (class "Default")
      (node (ref "A11") (pin "P2") (pinfunction "P$2_P2") (pintype "bidirectional"))
      (node (ref "A27") (pin "P2") (pinfunction "P$2_P2") (pintype "bidirectional"))
      (node (ref "A32") (pin "P2") (pinfunction "P$2_P2") (pintype "bidirectional"))
      (node (ref "D11") (pin "P2") (pinfunction "P$2_P2") (pintype "bidirectional"))
      (node (ref "D16") (pin "P2") (pinfunction "P$2_P2") (pintype "bidirectional"))
      (node (ref "D21") (pin "P2") (pinfunction "P$2_P2") (pintype "bidirectional"))
      (node (ref "D26") (pin "P2") (pinfunction "P$2_P2") (pintype "bidirectional"))
      (node (ref "D31") (pin "P2") (pinfunction "P$2_P2") (pintype "bidirectional"))
    )
    (net (code "333") (name "GND") (class "Default")
      (node (ref "A14") (pin "J2") (pinfunction "J_J2") (pintype "input"))
      (node (ref "A14") (pin "P2") (pinfunction "J_P2") (pintype "input"))
      (node (ref "A14") (pin "V2") (pinfunction "J_V2") (pintype "input"))
      (node (ref "A15") (pin "J2") (pinfunction "J_J2") (pintype "input"))
      (node (ref "A15") (pin "P2") (pinfunction "J_P2") (pintype "input"))
      (node (ref "A19") (pin "E2") (pinfunction "EN0_E2") (pintype "input"))
      (node (ref "B03") (pin "H2") (pinfunction "G_H2") (pintype "input"))
      (node (ref "B03") (pin "N2") (pinfunction "G_N2") (pintype "input"))
      (node (ref "B03") (pin "U2") (pinfunction "G_U2") (pintype "input"))
      (node (ref "B27") (pin "J2") (pinfunction "J_J2") (pintype "input"))
      (node (ref "B27") (pin "P2") (pinfunction "J_P2") (pintype "input"))
      (node (ref "B27") (pin "V2") (pinfunction "J_V2") (pintype "input"))
      (node (ref "B28") (pin "J2") (pinfunction "J_J2") (pintype "input"))
      (node (ref "B28") (pin "P2") (pinfunction "J_P2") (pintype "input"))
      (node (ref "B28") (pin "V2") (pinfunction "J_V2") (pintype "input"))
      (node (ref "B29") (pin "J2") (pinfunction "J_J2") (pintype "input"))
      (node (ref "B29") (pin "P2") (pinfunction "J_P2") (pintype "input"))
      (node (ref "B29") (pin "V2") (pinfunction "J_V2") (pintype "input"))
      (node (ref "C32") (pin "F2") (pinfunction "F_F2") (pintype "input"))
    )
    (net (code "334") (name "INC_MB") (class "Default")
      (node (ref "A08") (pin "T2") (pinfunction "P$2_T2") (pintype "bidirectional"))
      (node (ref "A24") (pin "T2") (pinfunction "P$2_T2") (pintype "bidirectional"))
      (node (ref "A29") (pin "T2") (pinfunction "P$2_T2") (pintype "bidirectional"))
      (node (ref "D08") (pin "T2") (pinfunction "P$2_T2") (pintype "bidirectional"))
      (node (ref "D13") (pin "T2") (pinfunction "P$2_T2") (pintype "bidirectional"))
      (node (ref "D18") (pin "T2") (pinfunction "P$2_T2") (pintype "bidirectional"))
      (node (ref "D23") (pin "T2") (pinfunction "P$2_T2") (pintype "bidirectional"))
      (node (ref "D28") (pin "T2") (pinfunction "P$2_T2") (pintype "bidirectional"))
    )
    (net (code "335") (name "IOP1") (class "Default")
      (node (ref "A02") (pin "K2") (pinfunction "P$2_K2") (pintype "bidirectional"))
      (node (ref "D02") (pin "K2") (pinfunction "P$2_K2") (pintype "bidirectional"))
    )
    (net (code "336") (name "IOP2") (class "Default")
      (node (ref "A02") (pin "M2") (pinfunction "P$2_M2") (pintype "bidirectional"))
      (node (ref "D02") (pin "M2") (pinfunction "P$2_M2") (pintype "bidirectional"))
    )
    (net (code "337") (name "IOP4") (class "Default")
      (node (ref "A02") (pin "P2") (pinfunction "P$2_P2") (pintype "bidirectional"))
      (node (ref "D02") (pin "P2") (pinfunction "P$2_P2") (pintype "bidirectional"))
    )
    (net (code "338") (name "MPX0") (class "Default")
      (node (ref "A13") (pin "E2") (pinfunction "I$1_E2") (pintype "input"))
      (node (ref "A21") (pin "S2") (pinfunction "P$2_S2") (pintype "bidirectional"))
      (node (ref "B05") (pin "E2") (pinfunction "I$1_E2") (pintype "input"))
      (node (ref "B12") (pin "M2") (pinfunction "M_M2") (pintype "input"))
      (node (ref "B14") (pin "J2") (pinfunction "1_J2") (pintype "open_collector"))
      (node (ref "B14") (pin "P2") (pinfunction "EN0_P2") (pintype "input"))
      (node (ref "B30") (pin "D2") (pinfunction "I$1_D2") (pintype "input"))
    )
    (net (code "339") (name "MPX1") (class "Default")
      (node (ref "A13") (pin "H2") (pinfunction "I$1_H2") (pintype "input"))
      (node (ref "A21") (pin "P2") (pinfunction "P$2_P2") (pintype "bidirectional"))
      (node (ref "B05") (pin "H2") (pinfunction "I$1_H2") (pintype "input"))
      (node (ref "B12") (pin "F2") (pinfunction "F_F2") (pintype "input"))
      (node (ref "B13") (pin "D2") (pinfunction "O$1_D2") (pintype "open_collector"))
      (node (ref "B16") (pin "J2") (pinfunction "1_J2") (pintype "open_collector"))
      (node (ref "B16") (pin "P2") (pinfunction "EN0_P2") (pintype "input"))
      (node (ref "B30") (pin "K2") (pinfunction "I$1_K2") (pintype "input"))
    )
    (net (code "340") (name "MPX2") (class "Default")
      (node (ref "A13") (pin "K2") (pinfunction "I$1_K2") (pintype "input"))
      (node (ref "A21") (pin "M2") (pinfunction "P$2_M2") (pintype "bidirectional"))
      (node (ref "B05") (pin "K2") (pinfunction "I$1_K2") (pintype "input"))
      (node (ref "B12") (pin "K2") (pinfunction "K_K2") (pintype "input"))
      (node (ref "B13") (pin "F2") (pinfunction "O$1_F2") (pintype "open_collector"))
      (node (ref "B17") (pin "J2") (pinfunction "1_J2") (pintype "open_collector"))
      (node (ref "B17") (pin "P2") (pinfunction "EN0_P2") (pintype "input"))
      (node (ref "B30") (pin "R2") (pinfunction "I$1_R2") (pintype "input"))
    )
    (net (code "341") (name "MPX3") (class "Default")
      (node (ref "A13") (pin "M2") (pinfunction "I$1_M2") (pintype "input"))
      (node (ref "A21") (pin "K2") (pinfunction "P$2_K2") (pintype "bidirectional"))
      (node (ref "B05") (pin "M2") (pinfunction "I$1_M2") (pintype "input"))
      (node (ref "B12") (pin "E2") (pinfunction "E_E2") (pintype "input"))
      (node (ref "B13") (pin "J2") (pinfunction "O$1_J2") (pintype "open_collector"))
      (node (ref "B18") (pin "J2") (pinfunction "1_J2") (pintype "open_collector"))
      (node (ref "B18") (pin "P2") (pinfunction "EN0_P2") (pintype "input"))
      (node (ref "B31") (pin "D2") (pinfunction "I$1_D2") (pintype "input"))
    )
    (net (code "342") (name "MPX4") (class "Default")
      (node (ref "A13") (pin "P2") (pinfunction "I$1_P2") (pintype "input"))
      (node (ref "A21") (pin "H2") (pinfunction "P$2_H2") (pintype "bidirectional"))
      (node (ref "B05") (pin "P2") (pinfunction "I$1_P2") (pintype "input"))
      (node (ref "B12") (pin "J2") (pinfunction "J_J2") (pintype "input"))
      (node (ref "B13") (pin "L2") (pinfunction "O$1_L2") (pintype "open_collector"))
      (node (ref "B19") (pin "J2") (pinfunction "1_J2") (pintype "open_collector"))
      (node (ref "B19") (pin "P2") (pinfunction "EN0_P2") (pintype "input"))
      (node (ref "B31") (pin "K2") (pinfunction "I$1_K2") (pintype "input"))
    )
    (net (code "343") (name "MPX5") (class "Default")
      (node (ref "A13") (pin "S2") (pinfunction "I$1_S2") (pintype "input"))
      (node (ref "A21") (pin "E2") (pinfunction "P$2_E2") (pintype "bidirectional"))
      (node (ref "B05") (pin "S2") (pinfunction "I$1_S2") (pintype "input"))
      (node (ref "B12") (pin "D2") (pinfunction "D_D2") (pintype "input"))
      (node (ref "B13") (pin "N2") (pinfunction "O$1_N2") (pintype "open_collector"))
      (node (ref "B20") (pin "J2") (pinfunction "1_J2") (pintype "open_collector"))
      (node (ref "B20") (pin "P2") (pinfunction "EN0_P2") (pintype "input"))
      (node (ref "B31") (pin "R2") (pinfunction "I$1_R2") (pintype "input"))
    )
    (net (code "344") (name "MPX6") (class "Default")
      (node (ref "A13") (pin "U2") (pinfunction "I$1_U2") (pintype "input"))
      (node (ref "A21") (pin "D2") (pinfunction "P$2_D2") (pintype "bidirectional"))
      (node (ref "B05") (pin "U2") (pinfunction "I$1_U2") (pintype "input"))
      (node (ref "B13") (pin "R2") (pinfunction "O$1_R2") (pintype "open_collector"))
      (node (ref "B21") (pin "J2") (pinfunction "1_J2") (pintype "open_collector"))
      (node (ref "B21") (pin "P2") (pinfunction "EN0_P2") (pintype "input"))
      (node (ref "B23") (pin "D2") (pinfunction "I$1_D2") (pintype "input"))
    )
    (net (code "345") (name "Net-(A14A-D)") (class "Default")
      (node (ref "A14") (pin "D2") (pinfunction "D_D2") (pintype "input"))
      (node (ref "A16") (pin "U2") (pinfunction "O$1_U2") (pintype "open_collector"))
      (node (ref "A16") (pin "V2") (pinfunction "P$1_V2") (pintype "passive"))
    )
    (net (code "346") (name "Net-(A14B-D)") (class "Default")
      (node (ref "A14") (pin "K2") (pinfunction "D_K2") (pintype "input"))
      (node (ref "A17") (pin "H2") (pinfunction "O$1_H2") (pintype "open_collector"))
      (node (ref "A17") (pin "J2") (pinfunction "P$1_J2") (pintype "passive"))
    )
    (net (code "347") (name "Net-(A14C-D)") (class "Default")
      (node (ref "A14") (pin "R2") (pinfunction "D_R2") (pintype "input"))
      (node (ref "A17") (pin "N2") (pinfunction "O$1_N2") (pintype "open_collector"))
      (node (ref "A17") (pin "P2") (pinfunction "P$1_P2") (pintype "passive"))
    )
    (net (code "348") (name "Net-(A15A-D)") (class "Default")
      (node (ref "A15") (pin "D2") (pinfunction "D_D2") (pintype "input"))
      (node (ref "A17") (pin "U2") (pinfunction "O$1_U2") (pintype "open_collector"))
      (node (ref "A17") (pin "V2") (pinfunction "P$1_V2") (pintype "passive"))
    )
    (net (code "349") (name "Net-(A15B-D)") (class "Default")
      (node (ref "A15") (pin "K2") (pinfunction "D_K2") (pintype "input"))
      (node (ref "A18") (pin "H2") (pinfunction "O$1_H2") (pintype "open_collector"))
      (node (ref "A18") (pin "J2") (pinfunction "P$1_J2") (pintype "passive"))
    )
    (net (code "350") (name "Net-(A16C-O$1)") (class "Default")
      (node (ref "A16") (pin "H2") (pinfunction "O$1_H2") (pintype "open_collector"))
      (node (ref "A16") (pin "J2") (pinfunction "P$1_J2") (pintype "passive"))
      (node (ref "B29") (pin "K2") (pinfunction "D_K2") (pintype "input"))
    )
    (net (code "351") (name "Net-(A16E-O$1)") (class "Default")
      (node (ref "A16") (pin "N2") (pinfunction "O$1_N2") (pintype "open_collector"))
      (node (ref "A16") (pin "P2") (pinfunction "P$1_P2") (pintype "passive"))
      (node (ref "B29") (pin "R2") (pinfunction "D_R2") (pintype "input"))
    )
    (net (code "352") (name "Net-(A19C-PU1)") (class "Default")
      (node (ref "A19") (pin "K2") (pinfunction "PU1_K2") (pintype "input"))
      (node (ref "B03") (pin "F2") (pinfunction "O_F2") (pintype "open_collector"))
      (node (ref "B14") (pin "N2") (pinfunction "PU0_N2") (pintype "input"))
      (node (ref "B14") (pin "U2") (pinfunction "PU1_U2") (pintype "input"))
      (node (ref "B16") (pin "N2") (pinfunction "PU0_N2") (pintype "input"))
      (node (ref "B16") (pin "U2") (pinfunction "PU1_U2") (pintype "input"))
      (node (ref "B17") (pin "N2") (pinfunction "PU0_N2") (pintype "input"))
      (node (ref "B17") (pin "U2") (pinfunction "PU1_U2") (pintype "input"))
      (node (ref "B18") (pin "N2") (pinfunction "PU0_N2") (pintype "input"))
      (node (ref "B18") (pin "U2") (pinfunction "PU1_U2") (pintype "input"))
      (node (ref "B19") (pin "N2") (pinfunction "PU0_N2") (pintype "input"))
      (node (ref "B19") (pin "U2") (pinfunction "PU1_U2") (pintype "input"))
      (node (ref "B20") (pin "N2") (pinfunction "PU0_N2") (pintype "input"))
      (node (ref "B20") (pin "U2") (pinfunction "PU1_U2") (pintype "input"))
      (node (ref "B21") (pin "N2") (pinfunction "PU0_N2") (pintype "input"))
      (node (ref "B21") (pin "U2") (pinfunction "PU1_U2") (pintype "input"))
    )
    (net (code "353") (name "Net-(A19C-RESET)") (class "Default")
      (node (ref "A19") (pin "F2") (pinfunction "RESET_F2") (pintype "input"))
      (node (ref "B14") (pin "F2") (pinfunction "RESET_F2") (pintype "input"))
      (node (ref "B14") (pin "R2") (pinfunction "RESET_R2") (pintype "input"))
      (node (ref "B16") (pin "F2") (pinfunction "RESET_F2") (pintype "input"))
      (node (ref "B16") (pin "R2") (pinfunction "RESET_R2") (pintype "input"))
      (node (ref "B17") (pin "F2") (pinfunction "RESET_F2") (pintype "input"))
      (node (ref "B17") (pin "R2") (pinfunction "RESET_R2") (pintype "input"))
      (node (ref "B18") (pin "F2") (pinfunction "RESET_F2") (pintype "input"))
      (node (ref "B18") (pin "R2") (pinfunction "RESET_R2") (pintype "input"))
      (node (ref "B19") (pin "F2") (pinfunction "RESET_F2") (pintype "input"))
      (node (ref "B19") (pin "R2") (pinfunction "RESET_R2") (pintype "input"))
      (node (ref "B20") (pin "F2") (pinfunction "RESET_F2") (pintype "input"))
      (node (ref "B20") (pin "R2") (pinfunction "RESET_R2") (pintype "input"))
      (node (ref "B21") (pin "F2") (pinfunction "RESET_F2") (pintype "input"))
      (node (ref "B21") (pin "R2") (pinfunction "RESET_R2") (pintype "input"))
      (node (ref "B32") (pin "J2") (pinfunction "O$1_J2") (pintype "open_collector"))
    )
    (net (code "354") (name "Net-(B02A-O$1)") (class "Default")
      (node (ref "B02") (pin "D2") (pinfunction "O$1_D2") (pintype "open_collector"))
      (node (ref "B14") (pin "E2") (pinfunction "EN0_E2") (pintype "input"))
    )
    (net (code "355") (name "Net-(B02B-O$1)") (class "Default")
      (node (ref "B02") (pin "F2") (pinfunction "O$1_F2") (pintype "open_collector"))
      (node (ref "B16") (pin "E2") (pinfunction "EN0_E2") (pintype "input"))
    )
    (net (code "356") (name "Net-(B02E-O$1)") (class "Default")
      (node (ref "B02") (pin "J2") (pinfunction "O$1_J2") (pintype "open_collector"))
      (node (ref "B17") (pin "E2") (pinfunction "EN0_E2") (pintype "input"))
    )
    (net (code "357") (name "Net-(B02F-O$1)") (class "Default")
      (node (ref "B02") (pin "L2") (pinfunction "O$1_L2") (pintype "open_collector"))
      (node (ref "B18") (pin "E2") (pinfunction "EN0_E2") (pintype "input"))
    )
    (net (code "358") (name "Net-(B02G-O$1)") (class "Default")
      (node (ref "B02") (pin "N2") (pinfunction "O$1_N2") (pintype "open_collector"))
      (node (ref "B19") (pin "E2") (pinfunction "EN0_E2") (pintype "input"))
    )
    (net (code "359") (name "Net-(B02H-O$1)") (class "Default")
      (node (ref "B02") (pin "R2") (pinfunction "O$1_R2") (pintype "open_collector"))
      (node (ref "B20") (pin "E2") (pinfunction "EN0_E2") (pintype "input"))
    )
    (net (code "360") (name "Net-(B02I-O$1)") (class "Default")
      (node (ref "B02") (pin "T2") (pinfunction "O$1_T2") (pintype "open_collector"))
      (node (ref "B21") (pin "E2") (pinfunction "EN0_E2") (pintype "input"))
    )
    (net (code "361") (name "Net-(B03A-I$1)") (class "Default")
      (node (ref "B03") (pin "J2") (pinfunction "I$1_J2") (pintype "passive"))
      (node (ref "B32") (pin "F2") (pinfunction "O$1_F2") (pintype "open_collector"))
    )
    (net (code "362") (name "Net-(B03D-O)") (class "Default")
      (node (ref "B03") (pin "M2") (pinfunction "O_M2") (pintype "open_collector"))
      (node (ref "B14") (pin "K2") (pinfunction "PU1_K2") (pintype "input"))
      (node (ref "B16") (pin "K2") (pinfunction "PU1_K2") (pintype "input"))
      (node (ref "B17") (pin "K2") (pinfunction "PU1_K2") (pintype "input"))
      (node (ref "B18") (pin "K2") (pinfunction "PU1_K2") (pintype "input"))
      (node (ref "B19") (pin "K2") (pinfunction "PU1_K2") (pintype "input"))
      (node (ref "B20") (pin "K2") (pinfunction "PU1_K2") (pintype "input"))
      (node (ref "B21") (pin "K2") (pinfunction "PU1_K2") (pintype "input"))
    )
    (net (code "363") (name "Net-(B03D-PU0)") (class "Default")
      (node (ref "B03") (pin "K2") (pinfunction "PU0_K2") (pintype "input"))
      (node (ref "B03") (pin "R2") (pinfunction "PU0_R2") (pintype "input"))
      (node (ref "C32") (pin "M2") (pinfunction "M_M2") (pintype "output"))
    )
    (net (code "364") (name "Net-(B03E-O)") (class "Default")
      (node (ref "B03") (pin "T2") (pinfunction "O_T2") (pintype "open_collector"))
      (node (ref "B14") (pin "D2") (pinfunction "PU0_D2") (pintype "input"))
      (node (ref "B16") (pin "D2") (pinfunction "PU0_D2") (pintype "input"))
      (node (ref "B17") (pin "D2") (pinfunction "PU0_D2") (pintype "input"))
      (node (ref "B18") (pin "D2") (pinfunction "PU0_D2") (pintype "input"))
      (node (ref "B19") (pin "D2") (pinfunction "PU0_D2") (pintype "input"))
      (node (ref "B20") (pin "D2") (pinfunction "PU0_D2") (pintype "input"))
      (node (ref "B21") (pin "D2") (pinfunction "PU0_D2") (pintype "input"))
    )
    (net (code "365") (name "Net-(B06C-O$1)") (class "Default")
      (node (ref "B06") (pin "H2") (pinfunction "O$1_H2") (pintype "open_collector"))
      (node (ref "B06") (pin "J2") (pinfunction "P$1_J2") (pintype "passive"))
      (node (ref "B10") (pin "E2") (pinfunction "I$1_E2") (pintype "input"))
    )
    (net (code "366") (name "Net-(B06E-O$1)") (class "Default")
      (node (ref "B06") (pin "N2") (pinfunction "O$1_N2") (pintype "open_collector"))
      (node (ref "B06") (pin "P2") (pinfunction "P$1_P2") (pintype "passive"))
      (node (ref "B10") (pin "H2") (pinfunction "I$1_H2") (pintype "input"))
    )
    (net (code "367") (name "Net-(B06G-O$1)") (class "Default")
      (node (ref "B06") (pin "U2") (pinfunction "O$1_U2") (pintype "open_collector"))
      (node (ref "B06") (pin "V2") (pinfunction "P$1_V2") (pintype "passive"))
      (node (ref "B10") (pin "K2") (pinfunction "I$1_K2") (pintype "input"))
    )
    (net (code "368") (name "Net-(B07A-I$1)") (class "Default")
      (node (ref "B07") (pin "E2") (pinfunction "I$1_E2") (pintype "input"))
      (node (ref "B11") (pin "D2") (pinfunction "P$1_D2") (pintype "passive"))
      (node (ref "C01") (pin "D2") (pinfunction "D_D2") (pintype "output"))
    )
    (net (code "369") (name "Net-(B07B-I$1)") (class "Default")
      (node (ref "B07") (pin "H2") (pinfunction "I$1_H2") (pintype "input"))
      (node (ref "B11") (pin "E2") (pinfunction "P$1_E2") (pintype "passive"))
      (node (ref "C02") (pin "D2") (pinfunction "D_D2") (pintype "output"))
    )
    (net (code "370") (name "Net-(B07E-I$1)") (class "Default")
      (node (ref "B07") (pin "K2") (pinfunction "I$1_K2") (pintype "input"))
      (node (ref "B11") (pin "F2") (pinfunction "P$1_F2") (pintype "passive"))
      (node (ref "C03") (pin "D2") (pinfunction "D_D2") (pintype "output"))
    )
    (net (code "371") (name "Net-(B07F-I$1)") (class "Default")
      (node (ref "B07") (pin "M2") (pinfunction "I$1_M2") (pintype "input"))
      (node (ref "B11") (pin "H2") (pinfunction "P$1_H2") (pintype "passive"))
      (node (ref "C04") (pin "D2") (pinfunction "D_D2") (pintype "output"))
    )
    (net (code "372") (name "Net-(B07G-I$1)") (class "Default")
      (node (ref "B07") (pin "P2") (pinfunction "I$1_P2") (pintype "input"))
      (node (ref "B11") (pin "J2") (pinfunction "P$1_J2") (pintype "passive"))
      (node (ref "C05") (pin "D2") (pinfunction "D_D2") (pintype "output"))
    )
    (net (code "373") (name "Net-(B07H-I$1)") (class "Default")
      (node (ref "B07") (pin "S2") (pinfunction "I$1_S2") (pintype "input"))
      (node (ref "B11") (pin "K2") (pinfunction "P$1_K2") (pintype "passive"))
      (node (ref "C06") (pin "D2") (pinfunction "D_D2") (pintype "output"))
    )
    (net (code "374") (name "Net-(B07I-I$1)") (class "Default")
      (node (ref "B07") (pin "U2") (pinfunction "I$1_U2") (pintype "input"))
      (node (ref "B11") (pin "L2") (pinfunction "P$1_L2") (pintype "passive"))
      (node (ref "C07") (pin "D2") (pinfunction "D_D2") (pintype "output"))
    )
    (net (code "375") (name "Net-(B08C-O$1)") (class "Default")
      (node (ref "B08") (pin "H2") (pinfunction "O$1_H2") (pintype "open_collector"))
      (node (ref "B08") (pin "J2") (pinfunction "P$1_J2") (pintype "passive"))
      (node (ref "B10") (pin "M2") (pinfunction "I$1_M2") (pintype "input"))
    )
    (net (code "376") (name "Net-(B08E-O$1)") (class "Default")
      (node (ref "B08") (pin "N2") (pinfunction "O$1_N2") (pintype "open_collector"))
      (node (ref "B08") (pin "P2") (pinfunction "P$1_P2") (pintype "passive"))
      (node (ref "B10") (pin "P2") (pinfunction "I$1_P2") (pintype "input"))
    )
    (net (code "377") (name "Net-(B08G-O$1)") (class "Default")
      (node (ref "B08") (pin "U2") (pinfunction "O$1_U2") (pintype "open_collector"))
      (node (ref "B08") (pin "V2") (pinfunction "P$1_V2") (pintype "passive"))
      (node (ref "B10") (pin "S2") (pinfunction "I$1_S2") (pintype "input"))
    )
    (net (code "378") (name "Net-(B10I-I$1)") (class "Default")
      (node (ref "B10") (pin "U2") (pinfunction "I$1_U2") (pintype "input"))
      (node (ref "B23") (pin "U2") (pinfunction "O$1_U2") (pintype "open_collector"))
      (node (ref "B23") (pin "V2") (pinfunction "P$1_V2") (pintype "passive"))
    )
    (net (code "379") (name "Net-(B11J-P$1)") (class "Default")
      (node (ref "B11") (pin "M2") (pinfunction "P$1_M2") (pintype "passive"))
      (node (ref "B15") (pin "E2") (pinfunction "I$1_E2") (pintype "input"))
      (node (ref "C08") (pin "D2") (pinfunction "D_D2") (pintype "output"))
    )
    (net (code "380") (name "Net-(B11K-P$1)") (class "Default")
      (node (ref "B11") (pin "N2") (pinfunction "P$1_N2") (pintype "passive"))
      (node (ref "B15") (pin "H2") (pinfunction "I$1_H2") (pintype "input"))
      (node (ref "C09") (pin "D2") (pinfunction "D_D2") (pintype "output"))
    )
    (net (code "381") (name "Net-(B11L-P$1)") (class "Default")
      (node (ref "B11") (pin "P2") (pinfunction "P$1_P2") (pintype "passive"))
      (node (ref "B15") (pin "K2") (pinfunction "I$1_K2") (pintype "input"))
      (node (ref "C10") (pin "D2") (pinfunction "D_D2") (pintype "output"))
    )
    (net (code "382") (name "Net-(B11M-P$1)") (class "Default")
      (node (ref "B11") (pin "R2") (pinfunction "P$1_R2") (pintype "passive"))
      (node (ref "B15") (pin "M2") (pinfunction "I$1_M2") (pintype "input"))
      (node (ref "C11") (pin "D2") (pinfunction "D_D2") (pintype "output"))
    )
    (net (code "383") (name "Net-(B11N-P$1)") (class "Default")
      (node (ref "B11") (pin "S2") (pinfunction "P$1_S2") (pintype "passive"))
      (node (ref "B15") (pin "P2") (pinfunction "I$1_P2") (pintype "input"))
      (node (ref "C12") (pin "D2") (pinfunction "D_D2") (pintype "output"))
    )
    (net (code "384") (name "Net-(B11O-P$1)") (class "Default")
      (node (ref "B11") (pin "T2") (pinfunction "P$1_T2") (pintype "passive"))
      (node (ref "B15") (pin "S2") (pinfunction "I$1_S2") (pintype "input"))
      (node (ref "C13") (pin "D2") (pinfunction "D_D2") (pintype "output"))
    )
    (net (code "385") (name "Net-(B11P-P$1)") (class "Default")
      (node (ref "B11") (pin "U2") (pinfunction "P$1_U2") (pintype "passive"))
      (node (ref "B15") (pin "U2") (pinfunction "I$1_U2") (pintype "input"))
      (node (ref "C14") (pin "D2") (pinfunction "D_D2") (pintype "output"))
    )
    (net (code "386") (name "Net-(B11Q-P$1)") (class "Default")
      (node (ref "B11") (pin "V2") (pinfunction "P$1_V2") (pintype "passive"))
      (node (ref "B25") (pin "E2") (pinfunction "I$1_E2") (pintype "input"))
      (node (ref "C15") (pin "D2") (pinfunction "D_D2") (pintype "output"))
    )
    (net (code "387") (name "Net-(B12A-N)") (class "Default")
      (node (ref "B12") (pin "N2") (pinfunction "N_N2") (pintype "output"))
      (node (ref "B13") (pin "K2") (pinfunction "I$1_K2") (pintype "input"))
    )
    (net (code "388") (name "Net-(B12A-P)") (class "Default")
      (node (ref "B12") (pin "P2") (pinfunction "P_P2") (pintype "output"))
      (node (ref "B13") (pin "M2") (pinfunction "I$1_M2") (pintype "input"))
    )
    (net (code "389") (name "Net-(B12A-R)") (class "Default")
      (node (ref "B12") (pin "R2") (pinfunction "R_R2") (pintype "output"))
      (node (ref "B13") (pin "H2") (pinfunction "I$1_H2") (pintype "input"))
    )
    (net (code "390") (name "Net-(B12A-S)") (class "Default")
      (node (ref "B12") (pin "S2") (pinfunction "S_S2") (pintype "output"))
      (node (ref "B13") (pin "E2") (pinfunction "I$1_E2") (pintype "input"))
    )
    (net (code "391") (name "Net-(B12A-T)") (class "Default")
      (node (ref "B12") (pin "T2") (pinfunction "T_T2") (pintype "output"))
      (node (ref "B13") (pin "P2") (pinfunction "I$1_P2") (pintype "input"))
    )
    (net (code "392") (name "Net-(B12A-U)") (class "Default")
      (node (ref "B12") (pin "U2") (pinfunction "U_U2") (pintype "output"))
      (node (ref "B13") (pin "S2") (pinfunction "I$1_S2") (pintype "input"))
    )
    (net (code "393") (name "Net-(B14C-0)") (class "Default")
      (node (ref "B14") (pin "H2") (pinfunction "0_H2") (pintype "open_collector"))
      (node (ref "B14") (pin "V2") (pinfunction "EN1_V2") (pintype "input"))
    )
    (net (code "394") (name "Net-(B16C-0)") (class "Default")
      (node (ref "B16") (pin "H2") (pinfunction "0_H2") (pintype "open_collector"))
      (node (ref "B16") (pin "V2") (pinfunction "EN1_V2") (pintype "input"))
    )
    (net (code "395") (name "Net-(B17C-0)") (class "Default")
      (node (ref "B17") (pin "H2") (pinfunction "0_H2") (pintype "open_collector"))
      (node (ref "B17") (pin "V2") (pinfunction "EN1_V2") (pintype "input"))
    )
    (net (code "396") (name "Net-(B18C-0)") (class "Default")
      (node (ref "B18") (pin "H2") (pinfunction "0_H2") (pintype "open_collector"))
      (node (ref "B18") (pin "V2") (pinfunction "EN1_V2") (pintype "input"))
    )
    (net (code "397") (name "Net-(B19C-0)") (class "Default")
      (node (ref "B19") (pin "H2") (pinfunction "0_H2") (pintype "open_collector"))
      (node (ref "B19") (pin "V2") (pinfunction "EN1_V2") (pintype "input"))
    )
    (net (code "398") (name "Net-(B20C-0)") (class "Default")
      (node (ref "B20") (pin "H2") (pinfunction "0_H2") (pintype "open_collector"))
      (node (ref "B20") (pin "V2") (pinfunction "EN1_V2") (pintype "input"))
    )
    (net (code "399") (name "Net-(B21C-0)") (class "Default")
      (node (ref "B21") (pin "H2") (pinfunction "0_H2") (pintype "open_collector"))
      (node (ref "B21") (pin "V2") (pinfunction "EN1_V2") (pintype "input"))
    )
    (net (code "400") (name "Net-(B22A-F)") (class "Default")
      (node (ref "B22") (pin "F2") (pinfunction "F_F2") (pintype "open_collector"))
      (node (ref "B22") (pin "K2") (pinfunction "F_K2") (pintype "open_collector"))
      (node (ref "B22") (pin "N2") (pinfunction "F_N2") (pintype "open_collector"))
      (node (ref "B23") (pin "M2") (pinfunction "I$3_M2") (pintype "passive"))
    )
    (net (code "401") (name "Net-(B23C-O$1)") (class "Default")
      (node (ref "B23") (pin "H2") (pinfunction "O$1_H2") (pintype "open_collector"))
      (node (ref "B23") (pin "J2") (pinfunction "P$1_J2") (pintype "passive"))
      (node (ref "B29") (pin "D2") (pinfunction "D_D2") (pintype "input"))
    )
    (net (code "402") (name "Net-(B23E-O$1)") (class "Default")
      (node (ref "B23") (pin "N2") (pinfunction "O$1_N2") (pintype "open_collector"))
      (node (ref "B23") (pin "P2") (pinfunction "P$1_P2") (pintype "passive"))
      (node (ref "B32") (pin "E2") (pinfunction "I$1_E2") (pintype "input"))
    )
    (net (code "403") (name "Net-(B24A-P$1)") (class "Default")
      (node (ref "B24") (pin "D2") (pinfunction "P$1_D2") (pintype "passive"))
      (node (ref "B25") (pin "H2") (pinfunction "I$1_H2") (pintype "input"))
      (node (ref "C16") (pin "D2") (pinfunction "D_D2") (pintype "output"))
    )
    (net (code "404") (name "Net-(B24B-P$1)") (class "Default")
      (node (ref "B24") (pin "E2") (pinfunction "P$1_E2") (pintype "passive"))
      (node (ref "B25") (pin "K2") (pinfunction "I$1_K2") (pintype "input"))
      (node (ref "C17") (pin "D2") (pinfunction "D_D2") (pintype "output"))
    )
    (net (code "405") (name "Net-(B24C-P$1)") (class "Default")
      (node (ref "B24") (pin "F2") (pinfunction "P$1_F2") (pintype "passive"))
      (node (ref "B25") (pin "M2") (pinfunction "I$1_M2") (pintype "input"))
      (node (ref "C18") (pin "D2") (pinfunction "D_D2") (pintype "output"))
    )
    (net (code "406") (name "Net-(B24F-P$1)") (class "Default")
      (node (ref "B24") (pin "H2") (pinfunction "P$1_H2") (pintype "passive"))
      (node (ref "B25") (pin "P2") (pinfunction "I$1_P2") (pintype "input"))
      (node (ref "C19") (pin "D2") (pinfunction "D_D2") (pintype "output"))
    )
    (net (code "407") (name "Net-(B24G-P$1)") (class "Default")
      (node (ref "B24") (pin "J2") (pinfunction "P$1_J2") (pintype "passive"))
      (node (ref "B25") (pin "S2") (pinfunction "I$1_S2") (pintype "input"))
      (node (ref "C20") (pin "D2") (pinfunction "D_D2") (pintype "output"))
    )
    (net (code "408") (name "Net-(B24H-P$1)") (class "Default")
      (node (ref "B24") (pin "K2") (pinfunction "P$1_K2") (pintype "passive"))
      (node (ref "B25") (pin "U2") (pinfunction "I$1_U2") (pintype "input"))
      (node (ref "C21") (pin "D2") (pinfunction "D_D2") (pintype "output"))
    )
    (net (code "409") (name "Net-(B24I-P$1)") (class "Default")
      (node (ref "B24") (pin "L2") (pinfunction "P$1_L2") (pintype "passive"))
      (node (ref "B26") (pin "E2") (pinfunction "I$1_E2") (pintype "input"))
      (node (ref "C22") (pin "D2") (pinfunction "D_D2") (pintype "output"))
    )
    (net (code "410") (name "Net-(B24J-P$1)") (class "Default")
      (node (ref "B24") (pin "M2") (pinfunction "P$1_M2") (pintype "passive"))
      (node (ref "B26") (pin "H2") (pinfunction "I$1_H2") (pintype "input"))
      (node (ref "C23") (pin "D2") (pinfunction "D_D2") (pintype "output"))
    )
    (net (code "411") (name "Net-(B24K-P$1)") (class "Default")
      (node (ref "B24") (pin "N2") (pinfunction "P$1_N2") (pintype "passive"))
      (node (ref "B26") (pin "K2") (pinfunction "I$1_K2") (pintype "input"))
      (node (ref "C24") (pin "D2") (pinfunction "D_D2") (pintype "output"))
    )
    (net (code "412") (name "Net-(B24L-P$1)") (class "Default")
      (node (ref "B24") (pin "P2") (pinfunction "P$1_P2") (pintype "passive"))
      (node (ref "B26") (pin "M2") (pinfunction "I$1_M2") (pintype "input"))
      (node (ref "C25") (pin "D2") (pinfunction "D_D2") (pintype "output"))
    )
    (net (code "413") (name "Net-(B24M-P$1)") (class "Default")
      (node (ref "B24") (pin "R2") (pinfunction "P$1_R2") (pintype "passive"))
      (node (ref "B26") (pin "P2") (pinfunction "I$1_P2") (pintype "input"))
      (node (ref "C26") (pin "D2") (pinfunction "D_D2") (pintype "output"))
    )
    (net (code "414") (name "Net-(B24N-P$1)") (class "Default")
      (node (ref "B24") (pin "S2") (pinfunction "P$1_S2") (pintype "passive"))
      (node (ref "B26") (pin "S2") (pinfunction "I$1_S2") (pintype "input"))
      (node (ref "C27") (pin "D2") (pinfunction "D_D2") (pintype "output"))
    )
    (net (code "415") (name "Net-(B24O-P$1)") (class "Default")
      (node (ref "B24") (pin "T2") (pinfunction "P$1_T2") (pintype "passive"))
      (node (ref "B26") (pin "U2") (pinfunction "I$1_U2") (pintype "input"))
      (node (ref "C28") (pin "D2") (pinfunction "D_D2") (pintype "output"))
    )
    (net (code "416") (name "Net-(B24P-P$1)") (class "Default")
      (node (ref "B24") (pin "U2") (pinfunction "P$1_U2") (pintype "passive"))
      (node (ref "B32") (pin "P2") (pinfunction "I$1_P2") (pintype "input"))
      (node (ref "C29") (pin "D2") (pinfunction "D_D2") (pintype "output"))
    )
    (net (code "417") (name "Net-(B24Q-P$1)") (class "Default")
      (node (ref "B24") (pin "V2") (pinfunction "P$1_V2") (pintype "passive"))
      (node (ref "B32") (pin "S2") (pinfunction "I$1_S2") (pintype "input"))
      (node (ref "C30") (pin "D2") (pinfunction "D_D2") (pintype "output"))
    )
    (net (code "418") (name "Net-(B27A-D)") (class "Default")
      (node (ref "B27") (pin "D2") (pinfunction "D_D2") (pintype "input"))
      (node (ref "B30") (pin "H2") (pinfunction "O$1_H2") (pintype "open_collector"))
      (node (ref "B30") (pin "J2") (pinfunction "P$1_J2") (pintype "passive"))
    )
    (net (code "419") (name "Net-(B27B-D)") (class "Default")
      (node (ref "B27") (pin "K2") (pinfunction "D_K2") (pintype "input"))
      (node (ref "B30") (pin "N2") (pinfunction "O$1_N2") (pintype "open_collector"))
      (node (ref "B30") (pin "P2") (pinfunction "P$1_P2") (pintype "passive"))
    )
    (net (code "420") (name "Net-(B27C-D)") (class "Default")
      (node (ref "B27") (pin "R2") (pinfunction "D_R2") (pintype "input"))
      (node (ref "B30") (pin "U2") (pinfunction "O$1_U2") (pintype "open_collector"))
      (node (ref "B30") (pin "V2") (pinfunction "P$1_V2") (pintype "passive"))
    )
    (net (code "421") (name "Net-(B28A-D)") (class "Default")
      (node (ref "B28") (pin "D2") (pinfunction "D_D2") (pintype "input"))
      (node (ref "B31") (pin "H2") (pinfunction "O$1_H2") (pintype "open_collector"))
      (node (ref "B31") (pin "J2") (pinfunction "P$1_J2") (pintype "passive"))
    )
    (net (code "422") (name "Net-(B28B-D)") (class "Default")
      (node (ref "B28") (pin "K2") (pinfunction "D_K2") (pintype "input"))
      (node (ref "B31") (pin "N2") (pinfunction "O$1_N2") (pintype "open_collector"))
      (node (ref "B31") (pin "P2") (pinfunction "P$1_P2") (pintype "passive"))
    )
    (net (code "423") (name "Net-(B28C-D)") (class "Default")
      (node (ref "B28") (pin "R2") (pinfunction "D_R2") (pintype "input"))
      (node (ref "B31") (pin "U2") (pinfunction "O$1_U2") (pintype "open_collector"))
      (node (ref "B31") (pin "V2") (pinfunction "P$1_V2") (pintype "passive"))
    )
    (net (code "424") (name "Net-(B32F-O$1)") (class "Default")
      (node (ref "B32") (pin "L2") (pinfunction "O$1_L2") (pintype "open_collector"))
      (node (ref "C32") (pin "E2") (pinfunction "E_E2") (pintype "input"))
    )
    (net (code "425") (name "Net-(B32I-O$1)") (class "Default")
      (node (ref "B32") (pin "T2") (pinfunction "O$1_T2") (pintype "open_collector"))
      (node (ref "PDP-12/8I/8") (pin "3") (pinfunction "3_3") (pintype "passive"))
    )
    (net (code "426") (name "Net-(C32C-J)") (class "Default")
      (node (ref "C32") (pin "J2") (pinfunction "J_J2") (pintype "passive"))
      (node (ref "C32") (pin "K2") (pinfunction "K_K2") (pintype "passive"))
    )
    (net (code "427") (name "POWER_CLEAR") (class "Default")
      (node (ref "A02") (pin "V2") (pinfunction "P$2_V2") (pintype "bidirectional"))
      (node (ref "B32") (pin "K2") (pinfunction "I$1_K2") (pintype "input"))
      (node (ref "D02") (pin "V2") (pinfunction "P$2_V2") (pintype "bidirectional"))
    )
    (net (code "428") (name "RUN") (class "Default")
      (node (ref "A06") (pin "S2") (pinfunction "P$2_S2") (pintype "bidirectional"))
      (node (ref "D06") (pin "S2") (pinfunction "P$2_S2") (pintype "bidirectional"))
    )
    (net (code "429") (name "T2") (class "Default")
      (node (ref "A02") (pin "T2") (pinfunction "P$2_T2") (pintype "bidirectional"))
      (node (ref "B32") (pin "U2") (pinfunction "I$1_U2") (pintype "input"))
      (node (ref "D02") (pin "T2") (pinfunction "P$2_T2") (pintype "bidirectional"))
    )
    (net (code "431") (name "WCOV") (class "Default")
      (node (ref "A10") (pin "P2") (pinfunction "P$2_P2") (pintype "bidirectional"))
      (node (ref "A16") (pin "E2") (pinfunction "I$2_E2") (pintype "input"))
      (node (ref "A16") (pin "L2") (pinfunction "I$2_L2") (pintype "input"))
      (node (ref "A16") (pin "S2") (pinfunction "I$2_S2") (pintype "input"))
      (node (ref "A17") (pin "E2") (pinfunction "I$2_E2") (pintype "input"))
      (node (ref "A17") (pin "L2") (pinfunction "I$2_L2") (pintype "input"))
      (node (ref "A17") (pin "S2") (pinfunction "I$2_S2") (pintype "input"))
      (node (ref "A18") (pin "E2") (pinfunction "I$2_E2") (pintype "input"))
    )
    (net (code "432") (name "WCOV0") (class "Default")
      (node (ref "B29") (pin "N2") (pinfunction "H_N2") (pintype "output"))
      (node (ref "D10") (pin "P2") (pinfunction "P$2_P2") (pintype "bidirectional"))
    )
    (net (code "433") (name "WCOV1") (class "Default")
      (node (ref "B29") (pin "U2") (pinfunction "H_U2") (pintype "output"))
      (node (ref "D15") (pin "P2") (pinfunction "P$2_P2") (pintype "bidirectional"))
    )
    (net (code "434") (name "WCOV2") (class "Default")
      (node (ref "A14") (pin "H2") (pinfunction "H_H2") (pintype "output"))
      (node (ref "D20") (pin "P2") (pinfunction "P$2_P2") (pintype "bidirectional"))
    )
    (net (code "435") (name "WCOV3") (class "Default")
      (node (ref "A14") (pin "N2") (pinfunction "H_N2") (pintype "output"))
      (node (ref "D25") (pin "P2") (pinfunction "P$2_P2") (pintype "bidirectional"))
    )
    (net (code "436") (name "WCOV4") (class "Default")
      (node (ref "A14") (pin "U2") (pinfunction "H_U2") (pintype "output"))
      (node (ref "D30") (pin "P2") (pinfunction "P$2_P2") (pintype "bidirectional"))
    )
    (net (code "437") (name "WCOV5") (class "Default")
      (node (ref "A15") (pin "H2") (pinfunction "H_H2") (pintype "output"))
      (node (ref "A26") (pin "P2") (pinfunction "P$2_P2") (pintype "bidirectional"))
    )
    (net (code "438") (name "WCOV6") (class "Default")
      (node (ref "A15") (pin "N2") (pinfunction "H_N2") (pintype "output"))
      (node (ref "A31") (pin "P2") (pinfunction "P$2_P2") (pintype "bidirectional"))
    )
    (net (code "439") (name "unconnected-(A12I-I$2-PadV2)") (class "Default")
      (node (ref "A12") (pin "V2") (pinfunction "I$2_V2") (pintype "passive"))
    )
    (net (code "440") (name "unconnected-(A13I-I$2-PadV2)") (class "Default")
      (node (ref "A13") (pin "V2") (pinfunction "I$2_V2") (pintype "passive"))
    )
    (net (code "441") (name "unconnected-(A14A-E-PadE2)") (class "Default")
      (node (ref "A14") (pin "E2") (pinfunction "E_E2") (pintype "passive"))
    )
    (net (code "442") (name "unconnected-(A14A-F-PadF2)") (class "Default")
      (node (ref "A14") (pin "F2") (pinfunction "F_F2") (pintype "passive"))
    )
    (net (code "443") (name "unconnected-(A14B-E-PadL2)") (class "Default")
      (node (ref "A14") (pin "L2") (pinfunction "E_L2") (pintype "passive"))
    )
    (net (code "444") (name "unconnected-(A14B-F-PadM2)") (class "Default")
      (node (ref "A14") (pin "M2") (pinfunction "F_M2") (pintype "passive"))
    )
    (net (code "445") (name "unconnected-(A14C-E-PadS2)") (class "Default")
      (node (ref "A14") (pin "S2") (pinfunction "E_S2") (pintype "passive"))
    )
    (net (code "446") (name "unconnected-(A14C-F-PadT2)") (class "Default")
      (node (ref "A14") (pin "T2") (pinfunction "F_T2") (pintype "passive"))
    )
    (net (code "447") (name "unconnected-(A15A-E-PadE2)") (class "Default")
      (node (ref "A15") (pin "E2") (pinfunction "E_E2") (pintype "passive"))
    )
    (net (code "448") (name "unconnected-(A15A-F-PadF2)") (class "Default")
      (node (ref "A15") (pin "F2") (pinfunction "F_F2") (pintype "passive"))
    )
    (net (code "449") (name "unconnected-(A15B-E-PadL2)") (class "Default")
      (node (ref "A15") (pin "L2") (pinfunction "E_L2") (pintype "passive"))
    )
    (net (code "450") (name "unconnected-(A15B-F-PadM2)") (class "Default")
      (node (ref "A15") (pin "M2") (pinfunction "F_M2") (pintype "passive"))
    )
    (net (code "451") (name "unconnected-(A16C-I$3-PadF2)") (class "Default")
      (node (ref "A16") (pin "F2") (pinfunction "I$3_F2") (pintype "passive"))
    )
    (net (code "452") (name "unconnected-(A16E-I$3-PadM2)") (class "Default")
      (node (ref "A16") (pin "M2") (pinfunction "I$3_M2") (pintype "passive"))
    )
    (net (code "453") (name "unconnected-(A16G-I$3-PadT2)") (class "Default")
      (node (ref "A16") (pin "T2") (pinfunction "I$3_T2") (pintype "passive"))
    )
    (net (code "454") (name "unconnected-(A17C-I$3-PadF2)") (class "Default")
      (node (ref "A17") (pin "F2") (pinfunction "I$3_F2") (pintype "passive"))
    )
    (net (code "455") (name "unconnected-(A17E-I$3-PadM2)") (class "Default")
      (node (ref "A17") (pin "M2") (pinfunction "I$3_M2") (pintype "passive"))
    )
    (net (code "456") (name "unconnected-(A17G-I$3-PadT2)") (class "Default")
      (node (ref "A17") (pin "T2") (pinfunction "I$3_T2") (pintype "passive"))
    )
    (net (code "457") (name "unconnected-(A18C-I$3-PadF2)") (class "Default")
      (node (ref "A18") (pin "F2") (pinfunction "I$3_F2") (pintype "passive"))
    )
    (net (code "458") (name "unconnected-(A18E-I$2-PadL2)") (class "Default")
      (node (ref "A18") (pin "L2") (pinfunction "I$2_L2") (pintype "input"))
    )
    (net (code "459") (name "unconnected-(A18E-I$3-PadM2)") (class "Default")
      (node (ref "A18") (pin "M2") (pinfunction "I$3_M2") (pintype "passive"))
    )
    (net (code "460") (name "unconnected-(A19C-1-PadJ2)") (class "Default")
      (node (ref "A19") (pin "J2") (pinfunction "1_J2") (pintype "open_collector"))
    )
    (net (code "461") (name "unconnected-(A19C-SET-PadM2)") (class "Default")
      (node (ref "A19") (pin "M2") (pinfunction "SET_M2") (pintype "passive"))
    )
    (net (code "462") (name "unconnected-(B02I-I$2-PadV2)") (class "Default")
      (node (ref "B02") (pin "V2") (pinfunction "I$2_V2") (pintype "passive"))
    )
    (net (code "463") (name "unconnected-(B03A-EN0-PadE2)") (class "Default")
      (node (ref "B03") (pin "E2") (pinfunction "EN0_E2") (pintype "passive"))
    )
    (net (code "464") (name "unconnected-(B03A-PU0-PadD2)") (class "Default")
      (node (ref "B03") (pin "D2") (pinfunction "PU0_D2") (pintype "input"))
    )
    (net (code "465") (name "unconnected-(B03D-I$1-PadP2)") (class "Default")
      (node (ref "B03") (pin "P2") (pinfunction "I$1_P2") (pintype "passive"))
    )
    (net (code "466") (name "unconnected-(B03E-I$1-PadV2)") (class "Default")
      (node (ref "B03") (pin "V2") (pinfunction "I$1_V2") (pintype "passive"))
    )
    (net (code "467") (name "unconnected-(B04I-I$2-PadV2)") (class "Default")
      (node (ref "B04") (pin "V2") (pinfunction "I$2_V2") (pintype "passive"))
    )
    (net (code "468") (name "unconnected-(B05I-I$2-PadV2)") (class "Default")
      (node (ref "B05") (pin "V2") (pinfunction "I$2_V2") (pintype "passive"))
    )
    (net (code "469") (name "unconnected-(B06C-I$3-PadF2)") (class "Default")
      (node (ref "B06") (pin "F2") (pinfunction "I$3_F2") (pintype "passive"))
    )
    (net (code "470") (name "unconnected-(B06E-I$3-PadM2)") (class "Default")
      (node (ref "B06") (pin "M2") (pinfunction "I$3_M2") (pintype "passive"))
    )
    (net (code "471") (name "unconnected-(B06G-I$3-PadT2)") (class "Default")
      (node (ref "B06") (pin "T2") (pinfunction "I$3_T2") (pintype "passive"))
    )
    (net (code "472") (name "unconnected-(B07I-I$2-PadV2)") (class "Default")
      (node (ref "B07") (pin "V2") (pinfunction "I$2_V2") (pintype "passive"))
    )
    (net (code "473") (name "unconnected-(B08C-I$3-PadF2)") (class "Default")
      (node (ref "B08") (pin "F2") (pinfunction "I$3_F2") (pintype "passive"))
    )
    (net (code "474") (name "unconnected-(B08E-I$3-PadM2)") (class "Default")
      (node (ref "B08") (pin "M2") (pinfunction "I$3_M2") (pintype "passive"))
    )
    (net (code "475") (name "unconnected-(B08G-I$3-PadT2)") (class "Default")
      (node (ref "B08") (pin "T2") (pinfunction "I$3_T2") (pintype "passive"))
    )
    (net (code "476") (name "unconnected-(B10I-I$2-PadV2)") (class "Default")
      (node (ref "B10") (pin "V2") (pinfunction "I$2_V2") (pintype "passive"))
    )
    (net (code "477") (name "unconnected-(B12A-H-PadH2)") (class "Default")
      (node (ref "B12") (pin "H2") (pinfunction "H_H2") (pintype "input"))
    )
    (net (code "478") (name "unconnected-(B13I-I$2-PadV2)") (class "Default")
      (node (ref "B13") (pin "V2") (pinfunction "I$2_V2") (pintype "passive"))
    )
    (net (code "479") (name "unconnected-(B14C-SET-PadM2)") (class "Default")
      (node (ref "B14") (pin "M2") (pinfunction "SET_M2") (pintype "passive"))
    )
    (net (code "480") (name "unconnected-(B14D-0-PadS2)") (class "Default")
      (node (ref "B14") (pin "S2") (pinfunction "0_S2") (pintype "open_collector"))
    )
    (net (code "481") (name "unconnected-(B15I-I$2-PadV2)") (class "Default")
      (node (ref "B15") (pin "V2") (pinfunction "I$2_V2") (pintype "passive"))
    )
    (net (code "482") (name "unconnected-(B16C-SET-PadM2)") (class "Default")
      (node (ref "B16") (pin "M2") (pinfunction "SET_M2") (pintype "passive"))
    )
    (net (code "483") (name "unconnected-(B16D-0-PadS2)") (class "Default")
      (node (ref "B16") (pin "S2") (pinfunction "0_S2") (pintype "open_collector"))
    )
    (net (code "484") (name "unconnected-(B17C-SET-PadM2)") (class "Default")
      (node (ref "B17") (pin "M2") (pinfunction "SET_M2") (pintype "passive"))
    )
    (net (code "485") (name "unconnected-(B17D-0-PadS2)") (class "Default")
      (node (ref "B17") (pin "S2") (pinfunction "0_S2") (pintype "open_collector"))
    )
    (net (code "486") (name "unconnected-(B18C-SET-PadM2)") (class "Default")
      (node (ref "B18") (pin "M2") (pinfunction "SET_M2") (pintype "passive"))
    )
    (net (code "487") (name "unconnected-(B18D-0-PadS2)") (class "Default")
      (node (ref "B18") (pin "S2") (pinfunction "0_S2") (pintype "open_collector"))
    )
    (net (code "488") (name "unconnected-(B19C-SET-PadM2)") (class "Default")
      (node (ref "B19") (pin "M2") (pinfunction "SET_M2") (pintype "passive"))
    )
    (net (code "489") (name "unconnected-(B19D-0-PadS2)") (class "Default")
      (node (ref "B19") (pin "S2") (pinfunction "0_S2") (pintype "open_collector"))
    )
    (net (code "490") (name "unconnected-(B20C-SET-PadM2)") (class "Default")
      (node (ref "B20") (pin "M2") (pinfunction "SET_M2") (pintype "passive"))
    )
    (net (code "491") (name "unconnected-(B20D-0-PadS2)") (class "Default")
      (node (ref "B20") (pin "S2") (pinfunction "0_S2") (pintype "open_collector"))
    )
    (net (code "492") (name "unconnected-(B21C-SET-PadM2)") (class "Default")
      (node (ref "B21") (pin "M2") (pinfunction "SET_M2") (pintype "passive"))
    )
    (net (code "493") (name "unconnected-(B21D-0-PadS2)") (class "Default")
      (node (ref "B21") (pin "S2") (pinfunction "0_S2") (pintype "open_collector"))
    )
    (net (code "494") (name "unconnected-(B22E-E-PadM2)") (class "Default")
      (node (ref "B22") (pin "M2") (pinfunction "E_M2") (pintype "input"))
    )
    (net (code "495") (name "unconnected-(B23C-I$3-PadF2)") (class "Default")
      (node (ref "B23") (pin "F2") (pinfunction "I$3_F2") (pintype "passive"))
    )
    (net (code "496") (name "unconnected-(B23G-I$3-PadT2)") (class "Default")
      (node (ref "B23") (pin "T2") (pinfunction "I$3_T2") (pintype "passive"))
    )
    (net (code "497") (name "unconnected-(B25I-I$2-PadV2)") (class "Default")
      (node (ref "B25") (pin "V2") (pinfunction "I$2_V2") (pintype "passive"))
    )
    (net (code "498") (name "unconnected-(B26I-I$2-PadV2)") (class "Default")
      (node (ref "B26") (pin "V2") (pinfunction "I$2_V2") (pintype "passive"))
    )
    (net (code "499") (name "unconnected-(B27A-E-PadE2)") (class "Default")
      (node (ref "B27") (pin "E2") (pinfunction "E_E2") (pintype "passive"))
    )
    (net (code "500") (name "unconnected-(B27A-F-PadF2)") (class "Default")
      (node (ref "B27") (pin "F2") (pinfunction "F_F2") (pintype "passive"))
    )
    (net (code "501") (name "unconnected-(B27B-E-PadL2)") (class "Default")
      (node (ref "B27") (pin "L2") (pinfunction "E_L2") (pintype "passive"))
    )
    (net (code "502") (name "unconnected-(B27B-F-PadM2)") (class "Default")
      (node (ref "B27") (pin "M2") (pinfunction "F_M2") (pintype "passive"))
    )
    (net (code "503") (name "unconnected-(B27C-E-PadS2)") (class "Default")
      (node (ref "B27") (pin "S2") (pinfunction "E_S2") (pintype "passive"))
    )
    (net (code "504") (name "unconnected-(B27C-F-PadT2)") (class "Default")
      (node (ref "B27") (pin "T2") (pinfunction "F_T2") (pintype "passive"))
    )
    (net (code "505") (name "unconnected-(B28A-E-PadE2)") (class "Default")
      (node (ref "B28") (pin "E2") (pinfunction "E_E2") (pintype "passive"))
    )
    (net (code "506") (name "unconnected-(B28A-F-PadF2)") (class "Default")
      (node (ref "B28") (pin "F2") (pinfunction "F_F2") (pintype "passive"))
    )
    (net (code "507") (name "unconnected-(B28B-E-PadL2)") (class "Default")
      (node (ref "B28") (pin "L2") (pinfunction "E_L2") (pintype "passive"))
    )
    (net (code "508") (name "unconnected-(B28B-F-PadM2)") (class "Default")
      (node (ref "B28") (pin "M2") (pinfunction "F_M2") (pintype "passive"))
    )
    (net (code "509") (name "unconnected-(B28C-E-PadS2)") (class "Default")
      (node (ref "B28") (pin "S2") (pinfunction "E_S2") (pintype "passive"))
    )
    (net (code "510") (name "unconnected-(B28C-F-PadT2)") (class "Default")
      (node (ref "B28") (pin "T2") (pinfunction "F_T2") (pintype "passive"))
    )
    (net (code "511") (name "unconnected-(B29A-E-PadE2)") (class "Default")
      (node (ref "B29") (pin "E2") (pinfunction "E_E2") (pintype "passive"))
    )
    (net (code "512") (name "unconnected-(B29A-F-PadF2)") (class "Default")
      (node (ref "B29") (pin "F2") (pinfunction "F_F2") (pintype "passive"))
    )
    (net (code "513") (name "unconnected-(B29B-E-PadL2)") (class "Default")
      (node (ref "B29") (pin "L2") (pinfunction "E_L2") (pintype "passive"))
    )
    (net (code "514") (name "unconnected-(B29B-F-PadM2)") (class "Default")
      (node (ref "B29") (pin "M2") (pinfunction "F_M2") (pintype "passive"))
    )
    (net (code "515") (name "unconnected-(B29C-E-PadS2)") (class "Default")
      (node (ref "B29") (pin "S2") (pinfunction "E_S2") (pintype "passive"))
    )
    (net (code "516") (name "unconnected-(B29C-F-PadT2)") (class "Default")
      (node (ref "B29") (pin "T2") (pinfunction "F_T2") (pintype "passive"))
    )
    (net (code "517") (name "unconnected-(B30C-I$3-PadF2)") (class "Default")
      (node (ref "B30") (pin "F2") (pinfunction "I$3_F2") (pintype "passive"))
    )
    (net (code "518") (name "unconnected-(B30E-I$3-PadM2)") (class "Default")
      (node (ref "B30") (pin "M2") (pinfunction "I$3_M2") (pintype "passive"))
    )
    (net (code "519") (name "unconnected-(B30G-I$3-PadT2)") (class "Default")
      (node (ref "B30") (pin "T2") (pinfunction "I$3_T2") (pintype "passive"))
    )
    (net (code "520") (name "unconnected-(B31C-I$3-PadF2)") (class "Default")
      (node (ref "B31") (pin "F2") (pinfunction "I$3_F2") (pintype "passive"))
    )
    (net (code "521") (name "unconnected-(B31E-I$3-PadM2)") (class "Default")
      (node (ref "B31") (pin "M2") (pinfunction "I$3_M2") (pintype "passive"))
    )
    (net (code "522") (name "unconnected-(B31G-I$3-PadT2)") (class "Default")
      (node (ref "B31") (pin "T2") (pinfunction "I$3_T2") (pintype "passive"))
    )
    (net (code "523") (name "unconnected-(B32I-I$2-PadV2)") (class "Default")
      (node (ref "B32") (pin "V2") (pinfunction "I$2_V2") (pintype "passive"))
    )
    (net (code "524") (name "unconnected-(C32C-H-PadH2)") (class "Default")
      (node (ref "C32") (pin "H2") (pinfunction "H_H2") (pintype "passive"))
    )
    (net (code "525") (name "unconnected-(C32C-L-PadL2)") (class "Default")
      (node (ref "C32") (pin "L2") (pinfunction "L_L2") (pintype "passive"))
    )
    (net (code "526") (name "~{-BMB3}") (class "Default")
      (node (ref "A03") (pin "K2") (pinfunction "P$2_K2") (pintype "bidirectional"))
      (node (ref "D03") (pin "K2") (pinfunction "P$2_K2") (pintype "bidirectional"))
    )
    (net (code "527") (name "~{-BMB4}") (class "Default")
      (node (ref "A03") (pin "P2") (pinfunction "P$2_P2") (pintype "bidirectional"))
      (node (ref "D03") (pin "P2") (pinfunction "P$2_P2") (pintype "bidirectional"))
    )
    (net (code "528") (name "~{-BMB5}") (class "Default")
      (node (ref "A03") (pin "T2") (pinfunction "P$2_T2") (pintype "bidirectional"))
      (node (ref "D03") (pin "T2") (pinfunction "P$2_T2") (pintype "bidirectional"))
    )
    (net (code "529") (name "~{-BMB6}") (class "Default")
      (node (ref "A04") (pin "D2") (pinfunction "P$2_D2") (pintype "bidirectional"))
      (node (ref "D04") (pin "D2") (pinfunction "P$2_D2") (pintype "bidirectional"))
    )
    (net (code "530") (name "~{-BMB7}") (class "Default")
      (node (ref "A04") (pin "H2") (pinfunction "P$2_H2") (pintype "bidirectional"))
      (node (ref "D04") (pin "H2") (pinfunction "P$2_H2") (pintype "bidirectional"))
    )
    (net (code "531") (name "~{-BMB8}") (class "Default")
      (node (ref "A04") (pin "M2") (pinfunction "P$2_M2") (pintype "bidirectional"))
      (node (ref "D04") (pin "M2") (pinfunction "P$2_M2") (pintype "bidirectional"))
    )
    (net (code "532") (name "~{BREAK}") (class "Default")
      (node (ref "A18") (pin "N2") (pinfunction "O$1_N2") (pintype "open_collector"))
      (node (ref "A18") (pin "P2") (pinfunction "P$1_P2") (pintype "passive"))
      (node (ref "B03") (pin "S2") (pinfunction "EN0_S2") (pintype "passive"))
    )
    (net (code "533") (name "~{BRK_SYNC_CLK}") (class "Default")
      (node (ref "B13") (pin "T2") (pinfunction "O$1_T2") (pintype "open_collector"))
      (node (ref "PDP-12/8I/8") (pin "1") (pinfunction "1_1") (pintype "passive"))
    )
  )
)
